# SCH.net
KiCad netlist of a schematic drawn in EasyEDA
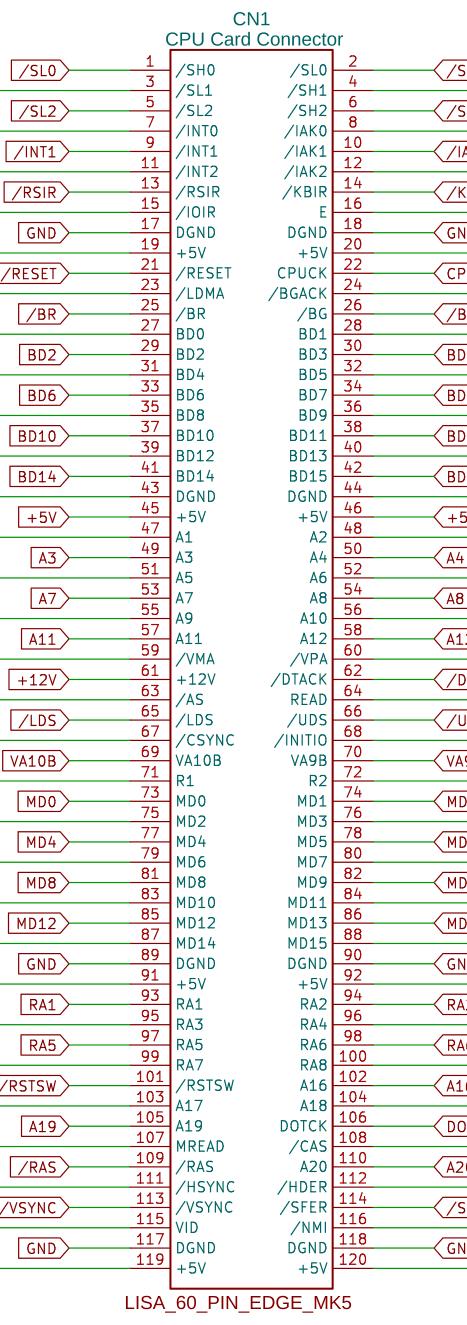
[diagram p0: CONNECTOR]
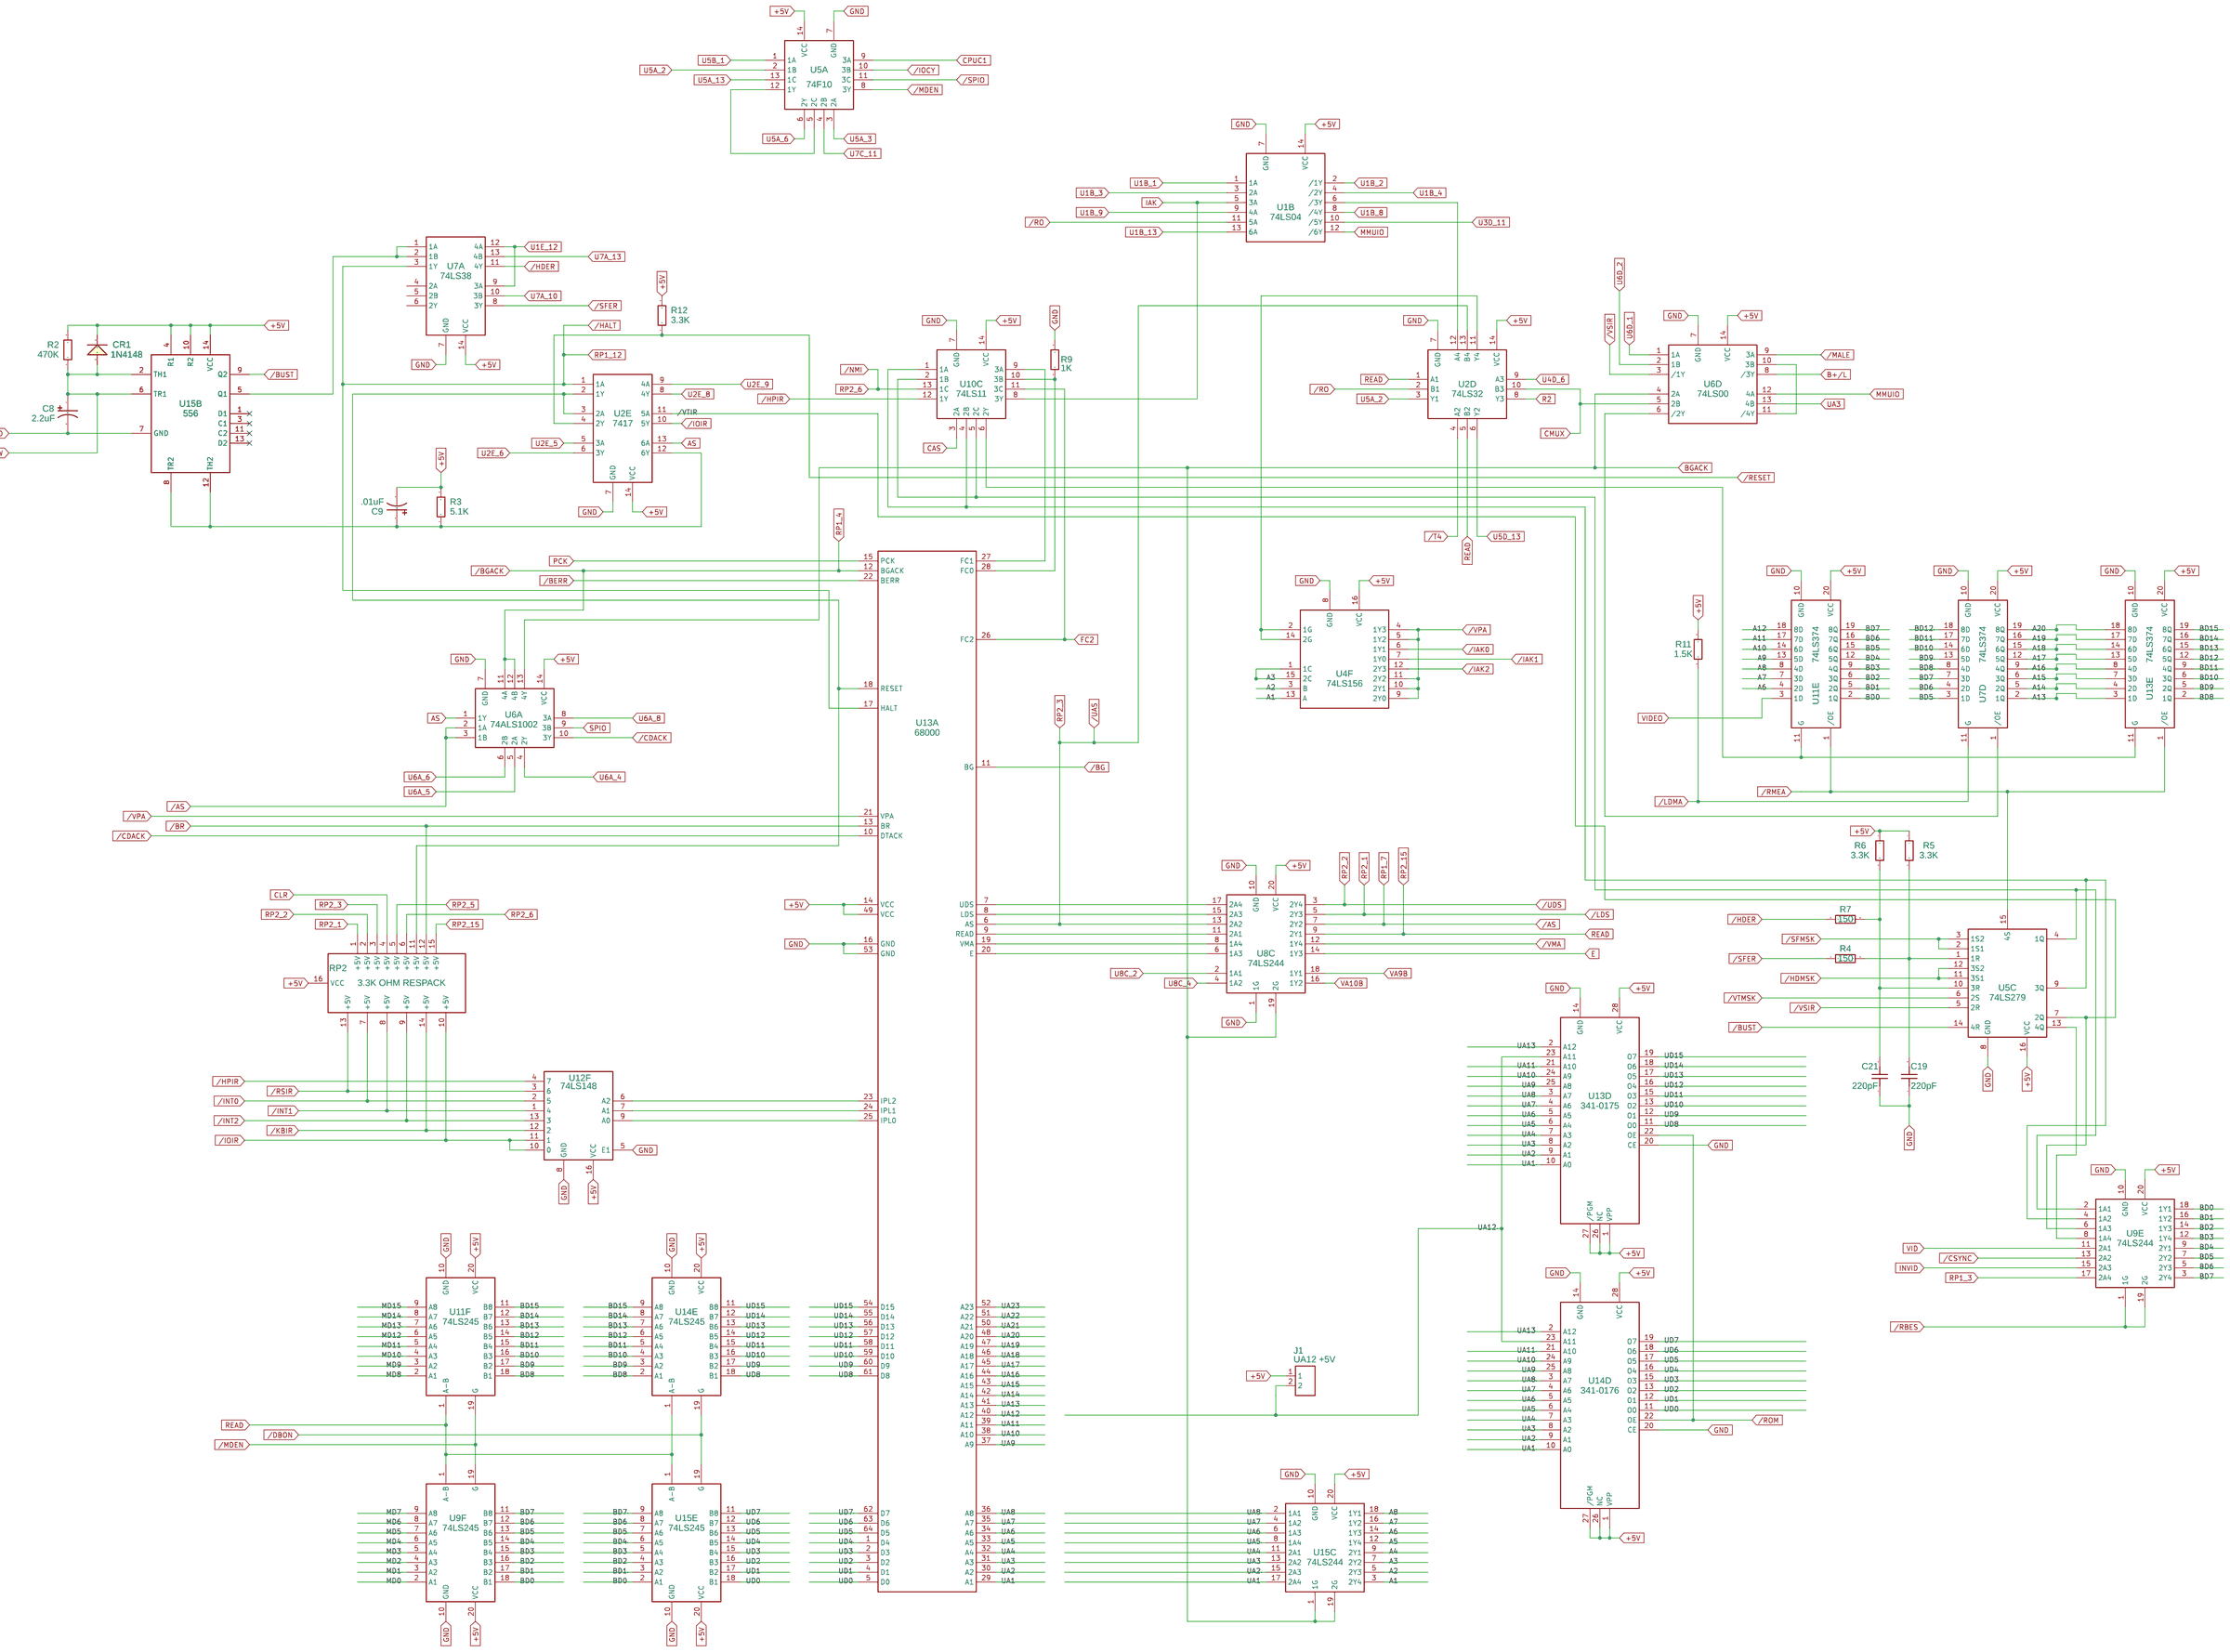
[diagram p1: CPU]
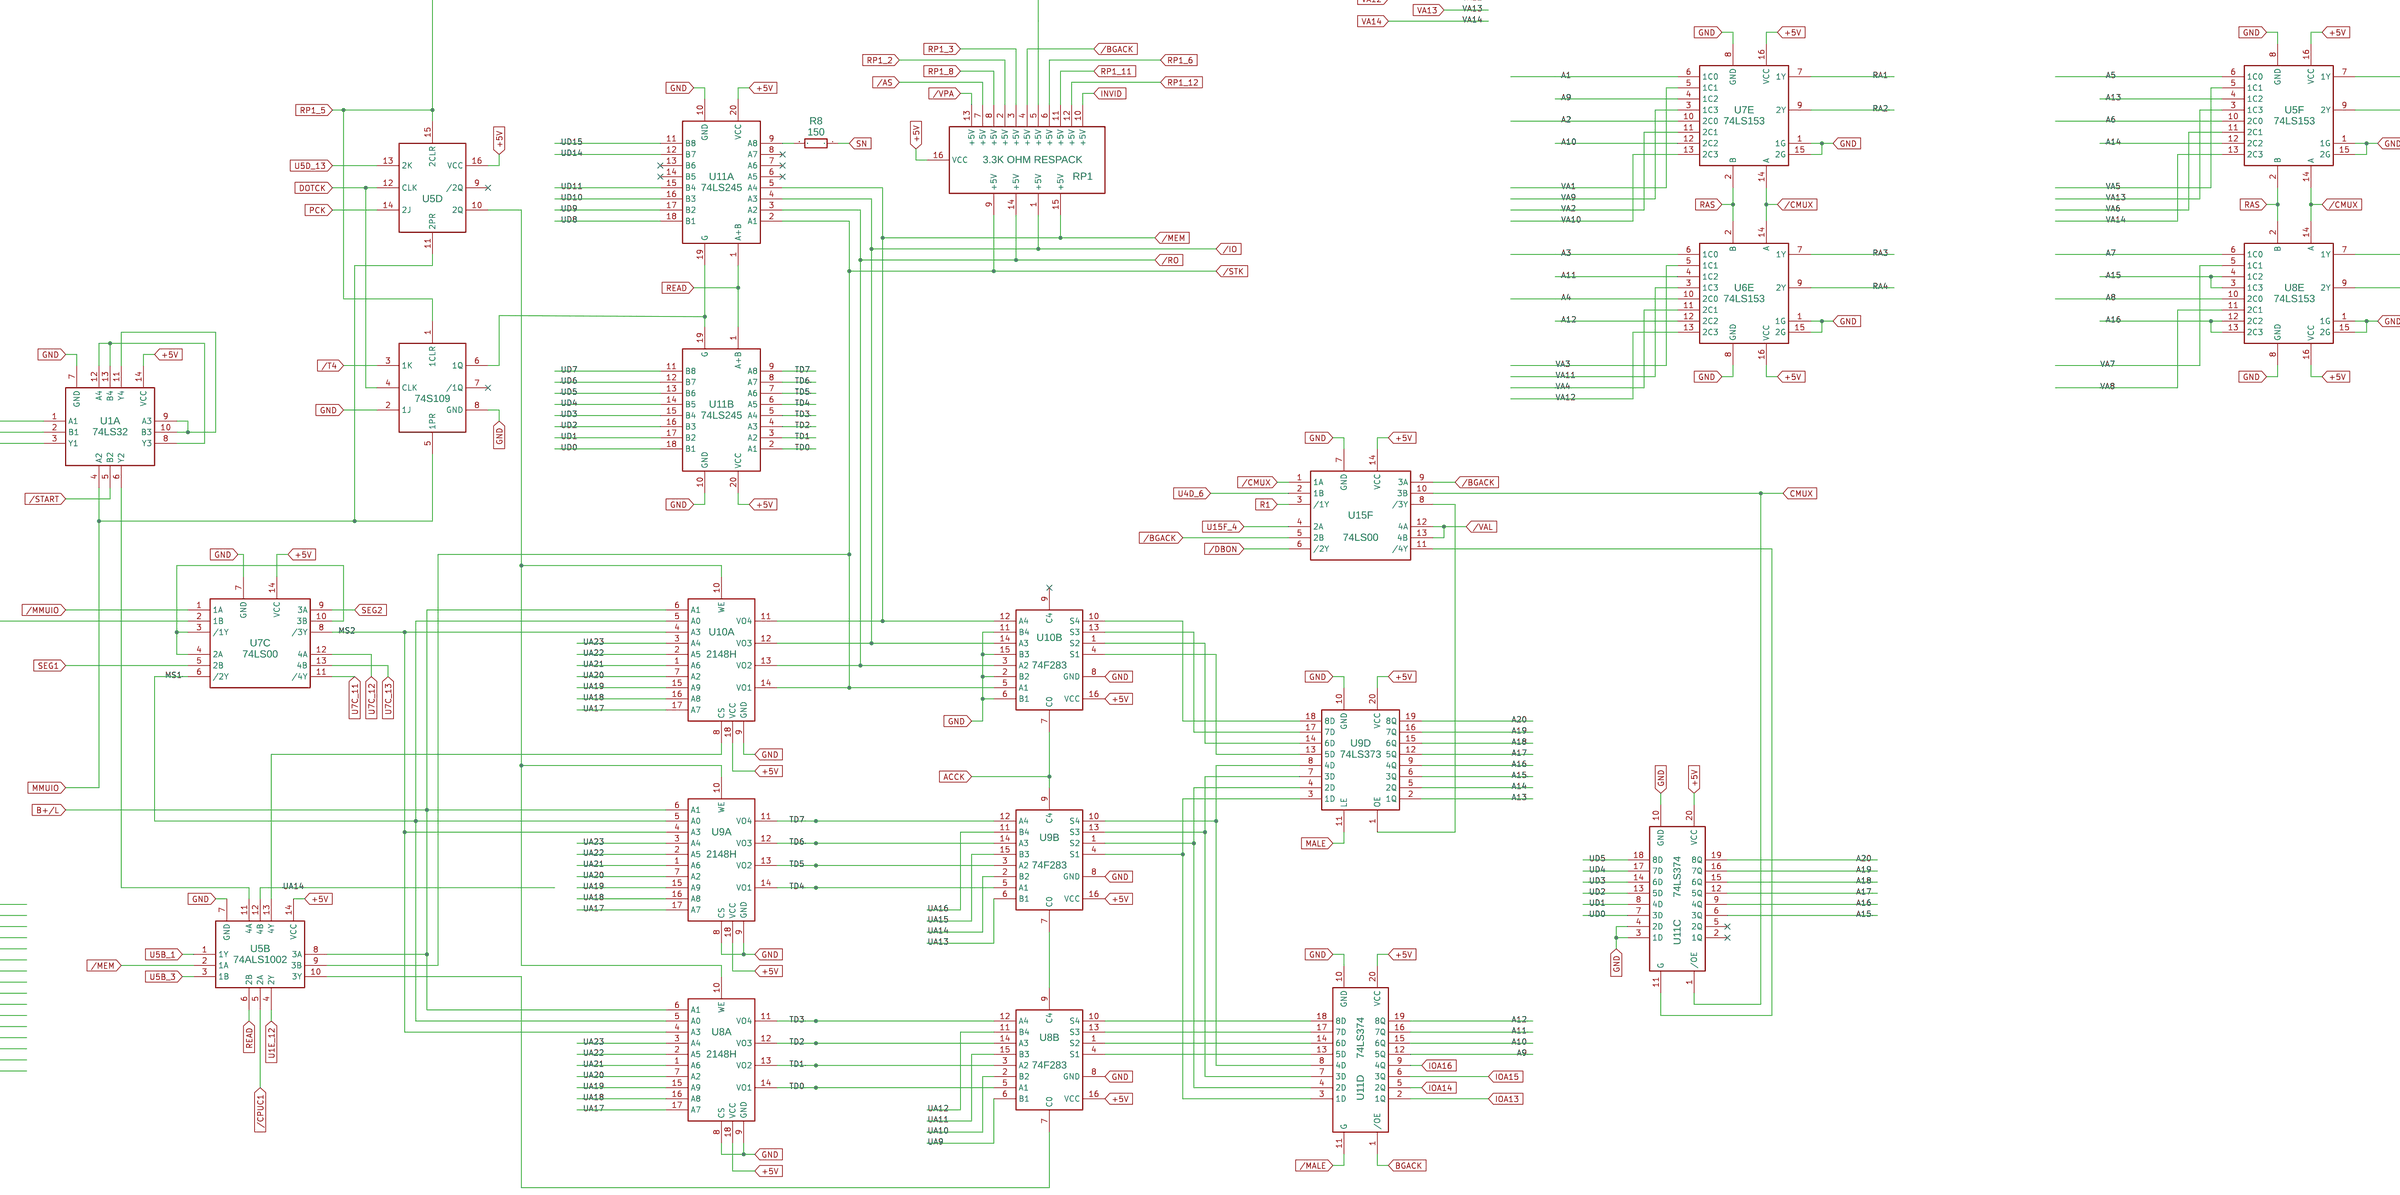
[diagram p2: MMU]
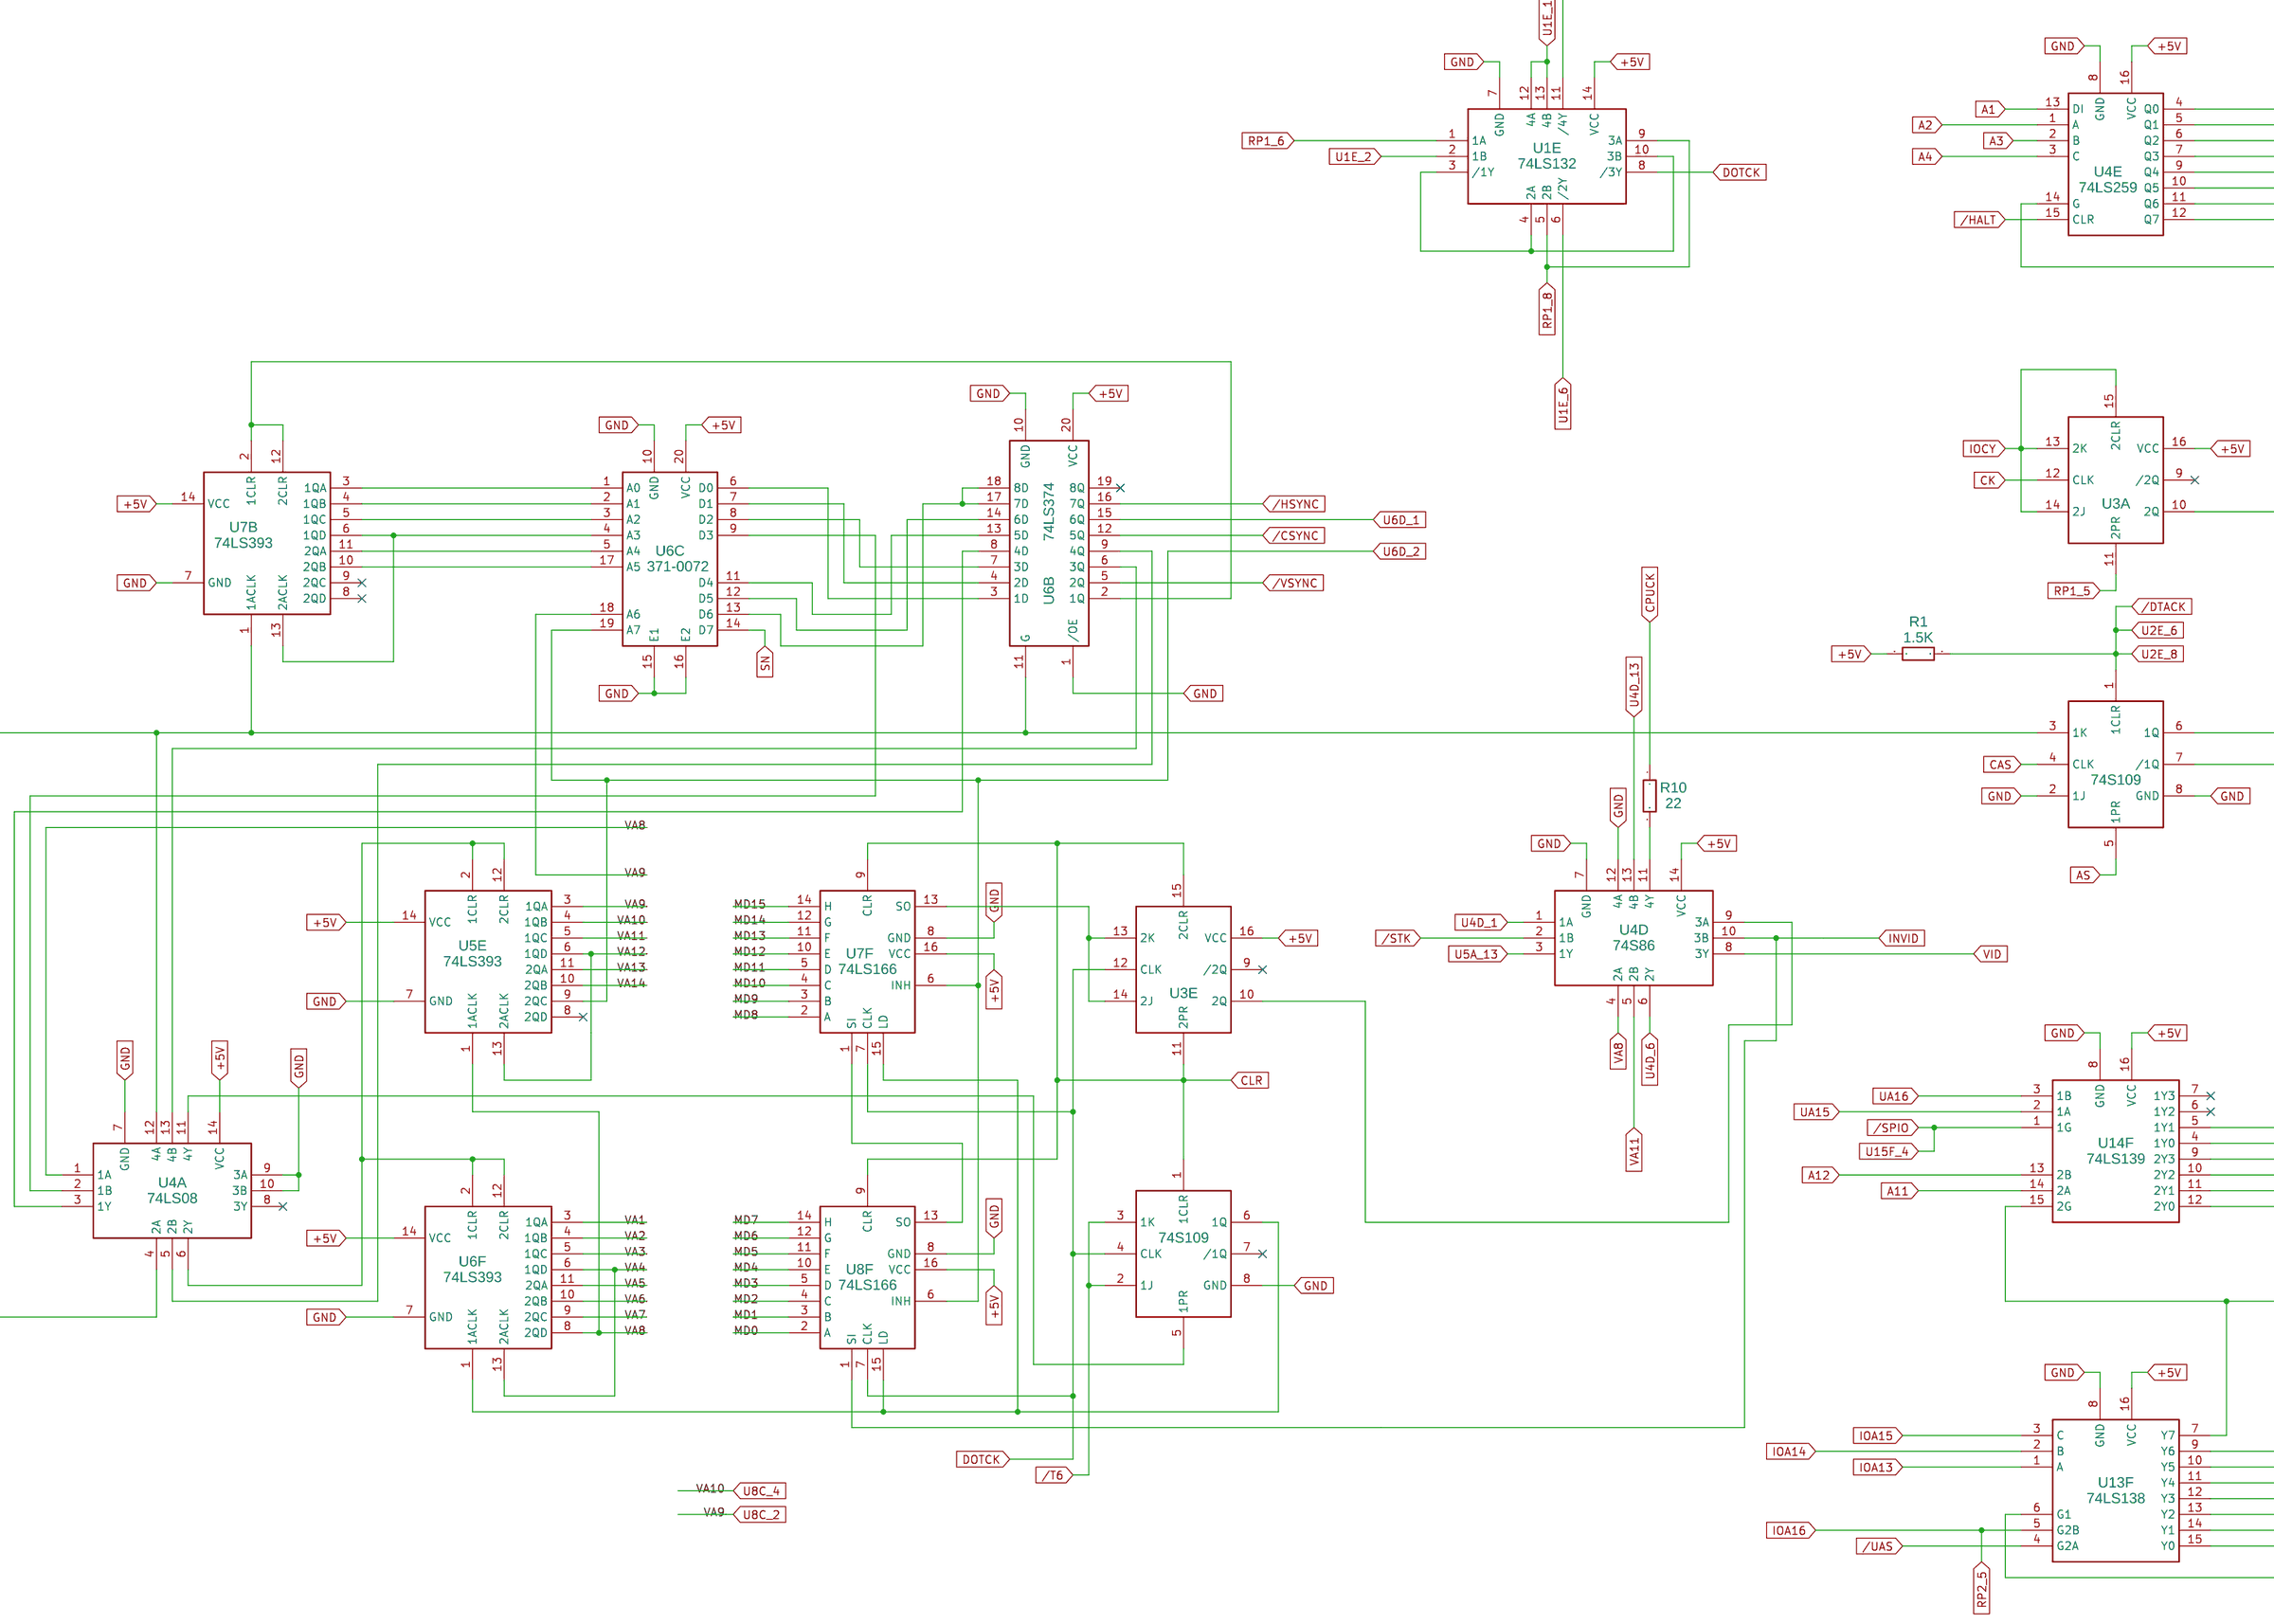
[diagram p3: VIDEO]
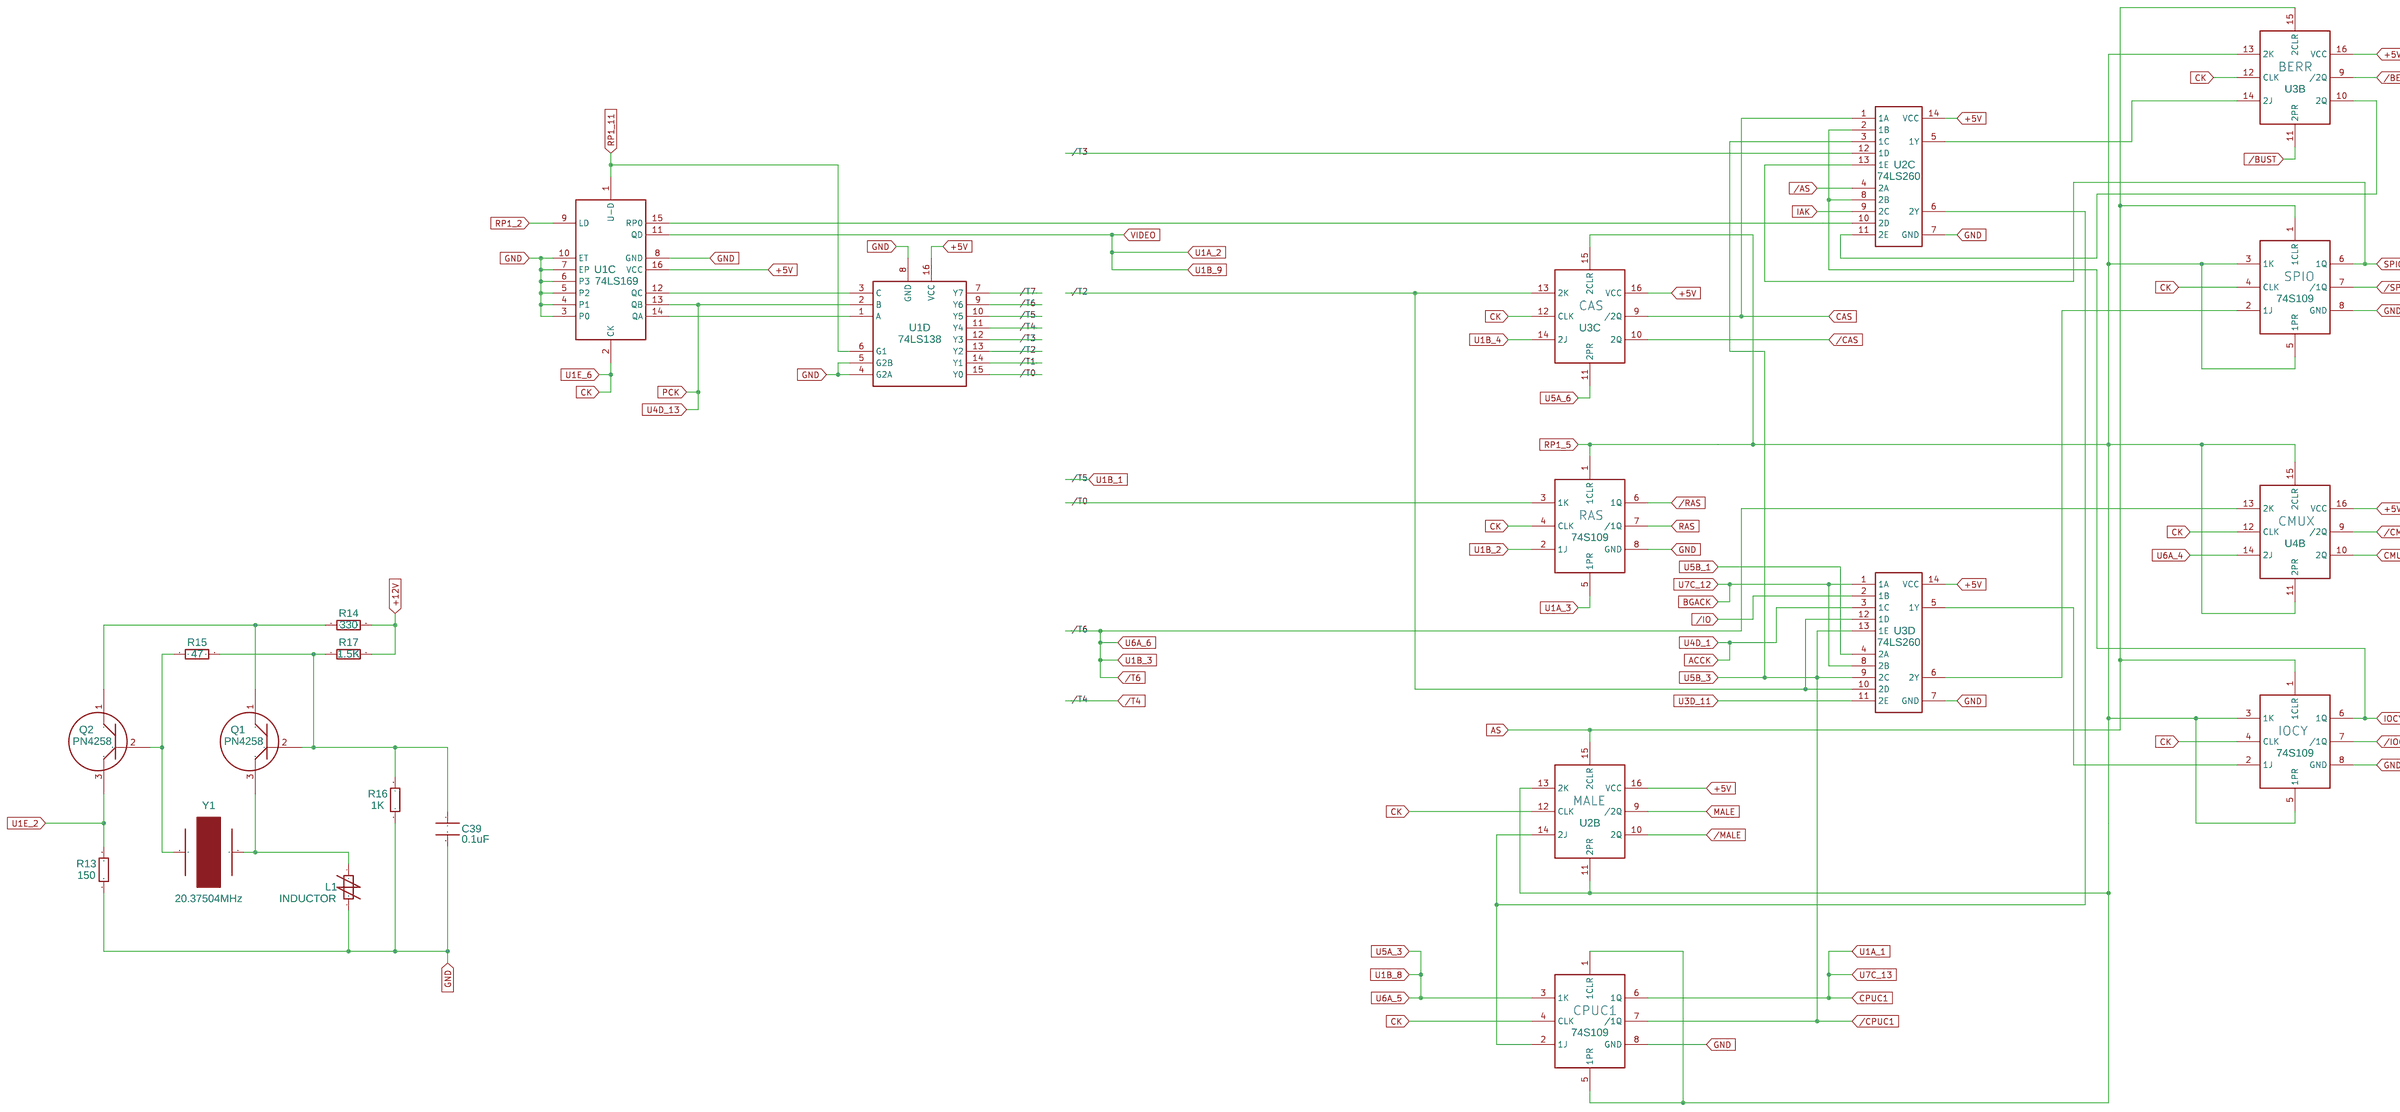
[diagram p4: CLOCK+IO]
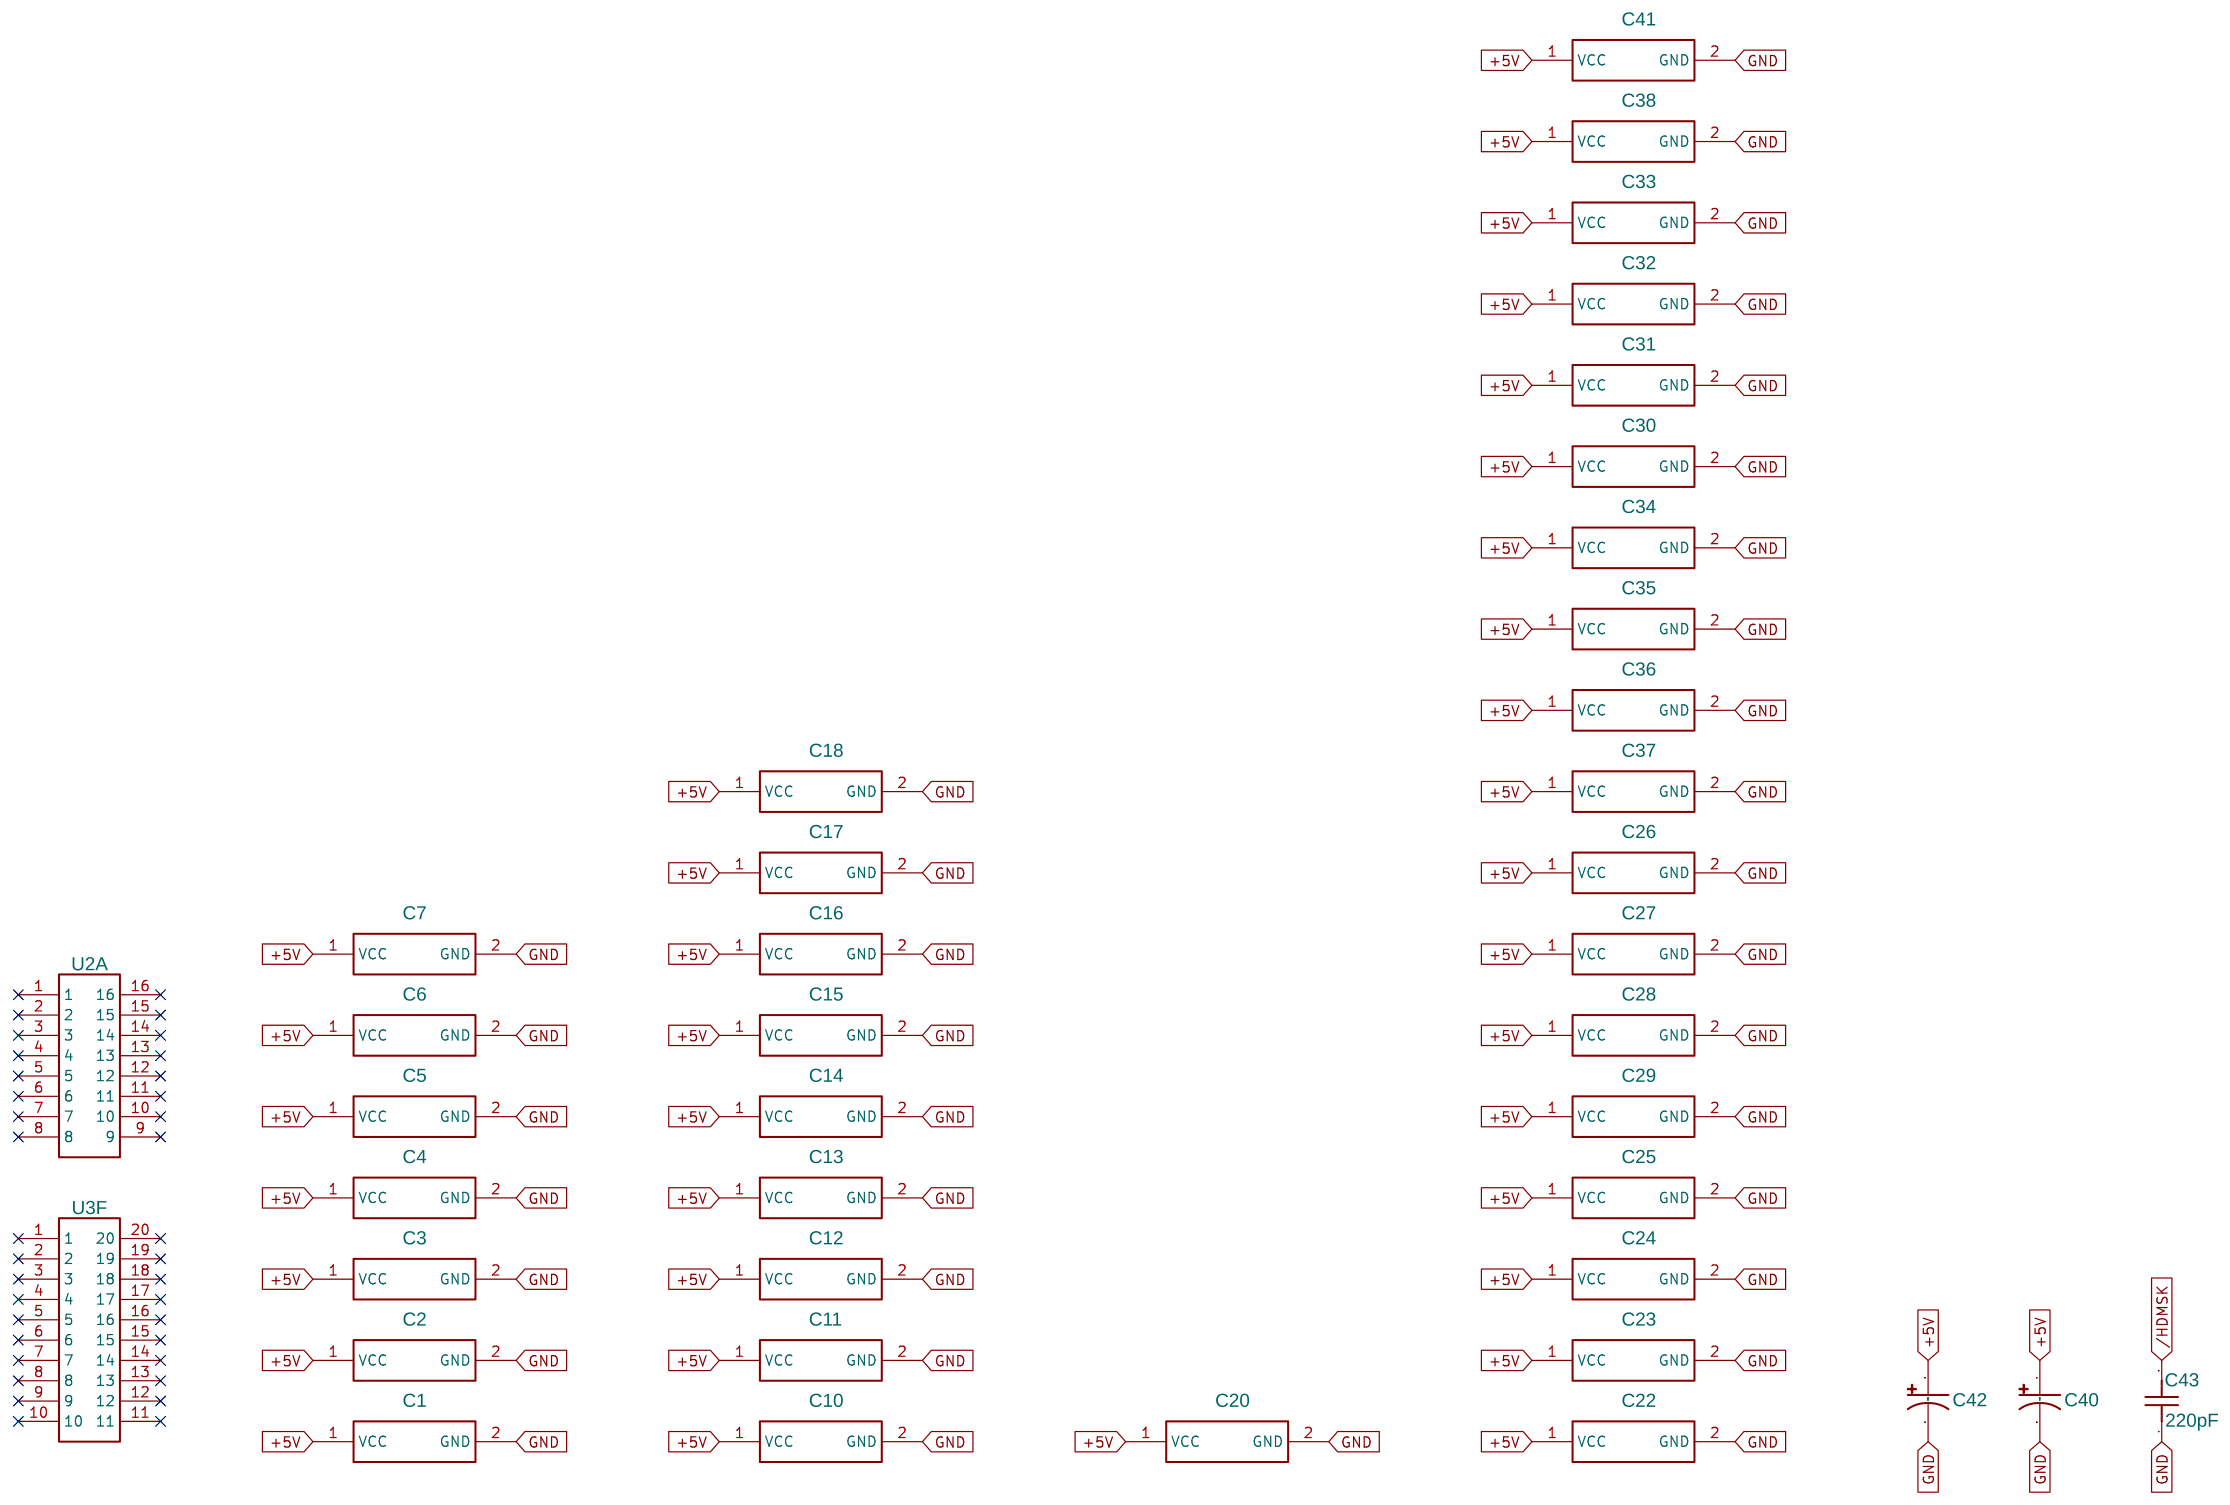
[diagram p5: MISC]

(export (version "E")
  (design (tool "Eeschema 10.0.6"))
  (components
    (comp (ref "CN1") (value "CPU Card Connector") (libsource (lib "") (part "Lisa CPU Connector")))
    (comp (ref "C8") (value "2.2uF") (libsource (lib "") (part "LISA_CPU_AXIAL_CAP")))
    (comp (ref "C9") (value ".01uF") (libsource (lib "") (part "LISA_CPU_AXIAL_CAP_1")))
    (comp (ref "C19") (value "220pF") (libsource (lib "") (part "LISA_CPU_CERAMIC_CAP")))
    (comp (ref "C21") (value "220pF") (libsource (lib "") (part "LISA_CPU_CERAMIC_CAP")))
    (comp (ref "CR1") (value "1N4148") (libsource (lib "") (part "LISA_CPU_DIODE")))
    (comp (ref "J1")
      (value "UA12 +5V")
      (fields (field (name "BOM_Manufacturer Part") "Jumper2") (field (name "BOM_Supplier Part") "C2940092"))
      (libsource (lib "") (part "JUMPER2"))
    )
    (comp (ref "R2") (value "470K") (libsource (lib "") (part "LISA_CPU_RESISTOR")))
    (comp (ref "R3") (value "5.1K") (libsource (lib "") (part "LISA_CPU_RESISTOR")))
    (comp (ref "R4") (value "150") (libsource (lib "") (part "LISA_CPU_RESISTOR_2")))
    (comp (ref "R5") (value "3.3K") (libsource (lib "") (part "LISA_CPU_RESISTOR_1")))
    (comp (ref "R6") (value "3.3K") (libsource (lib "") (part "LISA_CPU_RESISTOR_1")))
    (comp (ref "R7") (value "150") (libsource (lib "") (part "LISA_CPU_RESISTOR_2")))
    (comp (ref "R9") (value "1K") (libsource (lib "") (part "LISA_CPU_RESISTOR_1")))
    (comp (ref "R11") (value "1.5K") (libsource (lib "") (part "LISA_CPU_RESISTOR_1")))
    (comp (ref "R12") (value "3.3K") (libsource (lib "") (part "LISA_CPU_RESISTOR")))
    (comp (ref "RP2") (value "3.3K OHM RESPACK") (libsource (lib "") (part "LISA_CPU_RP2")))
    (comp (ref "U1B") (value "74LS04") (libsource (lib "") (part "LISA_CPU_74LS04")))
    (comp (ref "U2D") (value "74LS32") (libsource (lib "") (part "LISA_CPU_74LS32")))
    (comp (ref "U2E") (value "7417") (libsource (lib "") (part "LISA_CPU_7417")))
    (comp (ref "U4F") (value "74LS156") (libsource (lib "") (part "LISA_CPU_74LS156")))
    (comp (ref "U5A") (value "74F10") (libsource (lib "") (part "LISA_CPU_74F10")))
    (comp (ref "U5C") (value "74LS279") (libsource (lib "") (part "LISA_CPU_74LS279")))
    (comp (ref "U6A") (value "74ALS1002") (libsource (lib "") (part "LISA_CPU_74ALS1002")))
    (comp (ref "U6D") (value "74LS00") (libsource (lib "") (part "LISA_CPU_74LS00")))
    (comp (ref "U7A") (value "74LS38") (libsource (lib "") (part "LISA_CPU_74LS38")))
    (comp (ref "U7D") (value "74LS374") (libsource (lib "") (part "LISA_CPU_74LS374_1")))
    (comp (ref "U8C") (value "74LS244") (libsource (lib "") (part "LISA_CPU_74LS244_CTL")))
    (comp (ref "U9E") (value "74LS244") (libsource (lib "") (part "LISA_CPU_74LS244_1")))
    (comp (ref "U9F") (value "74LS245") (libsource (lib "") (part "LISA_CPU_74LS245_LOWER_1")))
    (comp (ref "U10C") (value "74LS11") (libsource (lib "") (part "LISA_CPU_74LS11")))
    (comp (ref "U11E") (value "74LS374") (libsource (lib "") (part "LISA_CPU_74LS374")))
    (comp (ref "U11F") (value "74LS245") (libsource (lib "") (part "LISA_CPU_74LS245_UPPER")))
    (comp (ref "U12F") (value "74LS148") (libsource (lib "") (part "LISA_CPU_74LS148")))
    (comp (ref "U13A") (value "68000") (libsource (lib "") (part "68000 (LISA)")))
    (comp (ref "U13D") (value "341-0175") (libsource (lib "") (part "LISA_CPU_EPROM")))
    (comp (ref "U13E") (value "74LS374") (libsource (lib "") (part "LISA_CPU_74LS374_2")))
    (comp (ref "U14D") (value "341-0176") (libsource (lib "") (part "LISA_CPU_EPROM_1")))
    (comp (ref "U14E") (value "74LS245") (libsource (lib "") (part "LISA_CPU_74LS245_UPPER_1")))
    (comp (ref "U15B") (value "556") (libsource (lib "") (part "LISA_CPU_556")))
    (comp (ref "U15C") (value "74LS244") (libsource (lib "") (part "LISA_CPU_74LS244")))
    (comp (ref "U15E") (value "74LS245") (libsource (lib "") (part "LISA_CPU_74LS245_LOWER")))
    (comp (ref "R8") (value "150") (libsource (lib "") (part "LISA_CPU_RESISTOR")))
    (comp (ref "RP1") (value "3.3K OHM RESPACK") (libsource (lib "") (part "LISA_CPU_RP1")))
    (comp (ref "U1A") (value "74LS32") (libsource (lib "") (part "LISA_CPU_74LS32")))
    (comp (ref "U5B") (value "74ALS1002") (libsource (lib "") (part "LISA_CPU_74ALS1002")))
    (comp (ref "U5D") (value "74S109") (libsource (lib "") (part "LISA_CPU_74S109")))
    (comp (ref "U5F") (value "74LS153") (libsource (lib "") (part "LISA_CPU_74LS153_UPPER_1")))
    (comp (ref "U6E") (value "74LS153") (libsource (lib "") (part "LISA_CPU_74LS153_LOWER_1")))
    (comp (ref "U7C") (value "74LS00") (libsource (lib "") (part "LISA_CPU_74LS00")))
    (comp (ref "U7E") (value "74LS153") (libsource (lib "") (part "LISA_CPU_74LS153_UPPER")))
    (comp (ref "U8A") (value "2148H") (libsource (lib "") (part "LISA_CPU_2148H")))
    (comp (ref "U8B") (value "74F283") (libsource (lib "") (part "LISA_CPU_74F283_1")))
    (comp (ref "U8E") (value "74LS153") (libsource (lib "") (part "LISA_CPU_74LS153_LOWER")))
    (comp (ref "U9A") (value "2148H") (libsource (lib "") (part "LISA_CPU_2148H_2")))
    (comp (ref "U9B") (value "74F283") (libsource (lib "") (part "LISA_CPU_74F283")))
    (comp (ref "U9D") (value "74LS373") (libsource (lib "") (part "LISA_CPU_74LS373")))
    (comp (ref "U10A") (value "2148H") (libsource (lib "") (part "LISA_CPU_2148H_1")))
    (comp (ref "U10B") (value "74F283") (libsource (lib "") (part "LISA_CPU_74F283_2")))
    (comp (ref "U11A") (value "74LS245") (libsource (lib "") (part "LISA_CPU_74LS245_U11A")))
    (comp (ref "U11B") (value "74LS245") (libsource (lib "") (part "LISA_CPU_74LS245_U11B")))
    (comp (ref "U11C") (value "74LS374") (libsource (lib "") (part "LISA_CPU_74LS374_1")))
    (comp (ref "U11D") (value "74LS374") (libsource (lib "") (part "LISA_CPU_74LS374")))
    (comp (ref "U15F") (value "74LS00") (libsource (lib "") (part "LISA_CPU_74LS00_1")))
    (comp (ref "R1") (value "1.5K") (libsource (lib "") (part "LISA_CPU_RESISTOR_1")))
    (comp (ref "R10") (value "22") (libsource (lib "") (part "LISA_CPU_RESISTOR")))
    (comp (ref "U1E") (value "74LS132") (libsource (lib "") (part "LISA_CPU_74LS132")))
    (comp (ref "U3A") (value "74S109") (libsource (lib "") (part "LISA_CPU_74S109")))
    (comp (ref "U3E") (value "74S109") (libsource (lib "") (part "LISA_CPU_74S109_1")))
    (comp (ref "U4A") (value "74LS08") (libsource (lib "") (part "LISA_CPU_74LS08")))
    (comp (ref "U4D") (value "74S86") (libsource (lib "") (part "LISA_CPU_74S86")))
    (comp (ref "U4E") (value "74LS259") (libsource (lib "") (part "LISA_CPU_74LS259")))
    (comp (ref "U5E") (value "74LS393") (libsource (lib "") (part "LISA_CPU_74LS393_2")))
    (comp (ref "U6B") (value "74LS374") (libsource (lib "") (part "LISA_CPU_74LS374")))
    (comp (ref "U6C") (value "371-0072") (libsource (lib "") (part "LISA_CPU_371-0072_VIDEO_ROM")))
    (comp (ref "U6F") (value "74LS393") (libsource (lib "") (part "LISA_CPU_74LS393")))
    (comp (ref "U7B") (value "74LS393") (libsource (lib "") (part "LISA_CPU_74LS393_1")))
    (comp (ref "U7F") (value "74LS166") (libsource (lib "") (part "LISA_CPU_74LS166")))
    (comp (ref "U8F") (value "74LS166") (libsource (lib "") (part "LISA_CPU_74LS166_1")))
    (comp (ref "U13F") (value "74LS138") (libsource (lib "") (part "LISA_CPU_74LS138")))
    (comp (ref "U14F") (value "74LS139") (libsource (lib "") (part "LISA_CPU_74LS139")))
    (comp (ref "C39") (value "0.1uF") (libsource (lib "") (part "LISA_CPU_GLASS_CAP")))
    (comp (ref "L1") (value "INDUCTOR") (libsource (lib "") (part "LISA_CPU_INDUCTOR")))
    (comp (ref "Q1") (value "PN4258") (libsource (lib "") (part "LISA_CPU_TRANSISTOR")))
    (comp (ref "Q2") (value "PN4258") (libsource (lib "") (part "LISA_CPU_TRANSISTOR")))
    (comp (ref "R13") (value "150") (libsource (lib "") (part "LISA_CPU_RESISTOR")))
    (comp (ref "R14") (value "330") (libsource (lib "") (part "LISA_CPU_RESISTOR_1")))
    (comp (ref "R15") (value "47") (libsource (lib "") (part "LISA_CPU_RESISTOR_1")))
    (comp (ref "R16") (value "1K") (libsource (lib "") (part "LISA_CPU_RESISTOR")))
    (comp (ref "R17") (value "1.5K") (libsource (lib "") (part "LISA_CPU_RESISTOR_1")))
    (comp (ref "U1C") (value "74LS169") (libsource (lib "") (part "LISA_CPU_74LS169")))
    (comp (ref "U1D") (value "74LS138") (libsource (lib "") (part "LISA_CPU_74LS138")))
    (comp (ref "U2B") (value "74S109") (libsource (lib "") (part "LISA_CPU_74S109")))
    (comp (ref "U2C") (value "74LS260") (libsource (lib "") (part "LISA_CPU_74LS260")))
    (comp (ref "U3B") (value "74S109") (libsource (lib "") (part "LISA_CPU_74S109_1")))
    (comp (ref "U3C") (value "74S109") (libsource (lib "") (part "LISA_CPU_74S109_2")))
    (comp (ref "U3D") (value "74LS260") (libsource (lib "") (part "LISA_CPU_74LS260_1")))
    (comp (ref "U4B") (value "74S109") (libsource (lib "") (part "LISA_CPU_74S109_3")))
    (comp (ref "Y1") (value "20.37504MHz") (libsource (lib "") (part "LISA_CPU_XTAL")))
    (comp (ref "C1")
      (value "LISA_CPU_DECOUPLER_CERAMIC_CAP")
      (libsource (lib "") (part "LISA_CPU_DECOUPLER_CERAMIC_CAP"))
    )
    (comp (ref "C2")
      (value "LISA_CPU_DECOUPLER_CERAMIC_CAP")
      (libsource (lib "") (part "LISA_CPU_DECOUPLER_CERAMIC_CAP"))
    )
    (comp (ref "C3")
      (value "LISA_CPU_DECOUPLER_CERAMIC_CAP")
      (libsource (lib "") (part "LISA_CPU_DECOUPLER_CERAMIC_CAP"))
    )
    (comp (ref "C4")
      (value "LISA_CPU_DECOUPLER_CERAMIC_CAP")
      (libsource (lib "") (part "LISA_CPU_DECOUPLER_CERAMIC_CAP"))
    )
    (comp (ref "C5")
      (value "LISA_CPU_DECOUPLER_CERAMIC_CAP")
      (libsource (lib "") (part "LISA_CPU_DECOUPLER_CERAMIC_CAP"))
    )
    (comp (ref "C6")
      (value "LISA_CPU_DECOUPLER_CERAMIC_CAP")
      (libsource (lib "") (part "LISA_CPU_DECOUPLER_CERAMIC_CAP"))
    )
    (comp (ref "C7")
      (value "LISA_CPU_DECOUPLER_CERAMIC_CAP")
      (libsource (lib "") (part "LISA_CPU_DECOUPLER_CERAMIC_CAP"))
    )
    (comp (ref "C10")
      (value "LISA_CPU_DECOUPLER_CERAMIC_CAP")
      (libsource (lib "") (part "LISA_CPU_DECOUPLER_CERAMIC_CAP"))
    )
    (comp (ref "C11")
      (value "LISA_CPU_DECOUPLER_CERAMIC_CAP")
      (libsource (lib "") (part "LISA_CPU_DECOUPLER_CERAMIC_CAP"))
    )
    (comp (ref "C12")
      (value "LISA_CPU_DECOUPLER_CERAMIC_CAP")
      (libsource (lib "") (part "LISA_CPU_DECOUPLER_CERAMIC_CAP"))
    )
    (comp (ref "C13")
      (value "LISA_CPU_DECOUPLER_CERAMIC_CAP")
      (libsource (lib "") (part "LISA_CPU_DECOUPLER_CERAMIC_CAP"))
    )
    (comp (ref "C14")
      (value "LISA_CPU_DECOUPLER_CERAMIC_CAP")
      (libsource (lib "") (part "LISA_CPU_DECOUPLER_CERAMIC_CAP"))
    )
    (comp (ref "C15")
      (value "LISA_CPU_DECOUPLER_CERAMIC_CAP")
      (libsource (lib "") (part "LISA_CPU_DECOUPLER_CERAMIC_CAP"))
    )
    (comp (ref "C16")
      (value "LISA_CPU_DECOUPLER_CERAMIC_CAP")
      (libsource (lib "") (part "LISA_CPU_DECOUPLER_CERAMIC_CAP"))
    )
    (comp (ref "C17")
      (value "LISA_CPU_DECOUPLER_CERAMIC_CAP")
      (libsource (lib "") (part "LISA_CPU_DECOUPLER_CERAMIC_CAP"))
    )
    (comp (ref "C18")
      (value "LISA_CPU_DECOUPLER_CERAMIC_CAP")
      (libsource (lib "") (part "LISA_CPU_DECOUPLER_CERAMIC_CAP"))
    )
    (comp (ref "C20")
      (value "LISA_CPU_DECOUPLER_CERAMIC_CAP")
      (libsource (lib "") (part "LISA_CPU_DECOUPLER_CERAMIC_CAP"))
    )
    (comp (ref "C22")
      (value "LISA_CPU_DECOUPLER_CERAMIC_CAP")
      (libsource (lib "") (part "LISA_CPU_DECOUPLER_CERAMIC_CAP"))
    )
    (comp (ref "C23")
      (value "LISA_CPU_DECOUPLER_CERAMIC_CAP")
      (libsource (lib "") (part "LISA_CPU_DECOUPLER_CERAMIC_CAP"))
    )
    (comp (ref "C24")
      (value "LISA_CPU_DECOUPLER_CERAMIC_CAP")
      (libsource (lib "") (part "LISA_CPU_DECOUPLER_CERAMIC_CAP"))
    )
    (comp (ref "C25")
      (value "LISA_CPU_DECOUPLER_CERAMIC_CAP")
      (libsource (lib "") (part "LISA_CPU_DECOUPLER_CERAMIC_CAP"))
    )
    (comp (ref "C26")
      (value "LISA_CPU_DECOUPLER_CERAMIC_CAP")
      (libsource (lib "") (part "LISA_CPU_DECOUPLER_CERAMIC_CAP"))
    )
    (comp (ref "C27")
      (value "LISA_CPU_DECOUPLER_CERAMIC_CAP")
      (libsource (lib "") (part "LISA_CPU_DECOUPLER_CERAMIC_CAP"))
    )
    (comp (ref "C28")
      (value "LISA_CPU_DECOUPLER_CERAMIC_CAP")
      (libsource (lib "") (part "LISA_CPU_DECOUPLER_CERAMIC_CAP"))
    )
    (comp (ref "C29")
      (value "LISA_CPU_DECOUPLER_CERAMIC_CAP")
      (libsource (lib "") (part "LISA_CPU_DECOUPLER_CERAMIC_CAP"))
    )
    (comp (ref "C30")
      (value "LISA_CPU_DECOUPLER_CERAMIC_CAP")
      (libsource (lib "") (part "LISA_CPU_DECOUPLER_CERAMIC_CAP"))
    )
    (comp (ref "C31")
      (value "LISA_CPU_DECOUPLER_CERAMIC_CAP")
      (libsource (lib "") (part "LISA_CPU_DECOUPLER_CERAMIC_CAP"))
    )
    (comp (ref "C32")
      (value "LISA_CPU_DECOUPLER_CERAMIC_CAP")
      (libsource (lib "") (part "LISA_CPU_DECOUPLER_CERAMIC_CAP"))
    )
    (comp (ref "C33")
      (value "LISA_CPU_DECOUPLER_CERAMIC_CAP")
      (libsource (lib "") (part "LISA_CPU_DECOUPLER_CERAMIC_CAP"))
    )
    (comp (ref "C34")
      (value "LISA_CPU_DECOUPLER_CERAMIC_CAP")
      (libsource (lib "") (part "LISA_CPU_DECOUPLER_CERAMIC_CAP"))
    )
    (comp (ref "C35")
      (value "LISA_CPU_DECOUPLER_CERAMIC_CAP")
      (libsource (lib "") (part "LISA_CPU_DECOUPLER_CERAMIC_CAP"))
    )
    (comp (ref "C36")
      (value "LISA_CPU_DECOUPLER_CERAMIC_CAP")
      (libsource (lib "") (part "LISA_CPU_DECOUPLER_CERAMIC_CAP"))
    )
    (comp (ref "C37")
      (value "LISA_CPU_DECOUPLER_CERAMIC_CAP")
      (libsource (lib "") (part "LISA_CPU_DECOUPLER_CERAMIC_CAP"))
    )
    (comp (ref "C38")
      (value "LISA_CPU_DECOUPLER_CERAMIC_CAP")
      (libsource (lib "") (part "LISA_CPU_DECOUPLER_CERAMIC_CAP"))
    )
    (comp (ref "C40") (value "LISA_CPU_AXIAL_CAP") (libsource (lib "") (part "LISA_CPU_AXIAL_CAP")))
    (comp (ref "C41")
      (value "LISA_CPU_DECOUPLER_CERAMIC_CAP")
      (libsource (lib "") (part "LISA_CPU_DECOUPLER_CERAMIC_CAP"))
    )
    (comp (ref "C42") (value "LISA_CPU_AXIAL_CAP") (libsource (lib "") (part "LISA_CPU_AXIAL_CAP")))
    (comp (ref "C43") (value "220pF") (libsource (lib "") (part "LISA_CPU_CERAMIC_CAP")))
    (comp (ref "U2A") (value "LISA_EMPTY_DIP_16") (libsource (lib "") (part "LISA_EMPTY_DIP_16")))
    (comp (ref "U3F") (value "LISA_EMPTY_DIP_20") (libsource (lib "") (part "LISA_EMPTY_DIP_20")))
  )
  (nets
    (net (code "1") (name "+5V") (class "Default")
      (node (ref "C1") (pin "1") (pinfunction "VCC_1") (pintype "unspecified"))
      (node (ref "C10") (pin "1") (pinfunction "VCC_1") (pintype "unspecified"))
      (node (ref "C11") (pin "1") (pinfunction "VCC_1") (pintype "unspecified"))
      (node (ref "C12") (pin "1") (pinfunction "VCC_1") (pintype "unspecified"))
      (node (ref "C13") (pin "1") (pinfunction "VCC_1") (pintype "unspecified"))
      (node (ref "C14") (pin "1") (pinfunction "VCC_1") (pintype "unspecified"))
      (node (ref "C15") (pin "1") (pinfunction "VCC_1") (pintype "unspecified"))
      (node (ref "C16") (pin "1") (pinfunction "VCC_1") (pintype "unspecified"))
      (node (ref "C17") (pin "1") (pinfunction "VCC_1") (pintype "unspecified"))
      (node (ref "C18") (pin "1") (pinfunction "VCC_1") (pintype "unspecified"))
      (node (ref "C2") (pin "1") (pinfunction "VCC_1") (pintype "unspecified"))
      (node (ref "C20") (pin "1") (pinfunction "VCC_1") (pintype "unspecified"))
      (node (ref "C22") (pin "1") (pinfunction "VCC_1") (pintype "unspecified"))
      (node (ref "C23") (pin "1") (pinfunction "VCC_1") (pintype "unspecified"))
      (node (ref "C24") (pin "1") (pinfunction "VCC_1") (pintype "unspecified"))
      (node (ref "C25") (pin "1") (pinfunction "VCC_1") (pintype "unspecified"))
      (node (ref "C26") (pin "1") (pinfunction "VCC_1") (pintype "unspecified"))
      (node (ref "C27") (pin "1") (pinfunction "VCC_1") (pintype "unspecified"))
      (node (ref "C28") (pin "1") (pinfunction "VCC_1") (pintype "unspecified"))
      (node (ref "C29") (pin "1") (pinfunction "VCC_1") (pintype "unspecified"))
      (node (ref "C3") (pin "1") (pinfunction "VCC_1") (pintype "unspecified"))
      (node (ref "C30") (pin "1") (pinfunction "VCC_1") (pintype "unspecified"))
      (node (ref "C31") (pin "1") (pinfunction "VCC_1") (pintype "unspecified"))
      (node (ref "C32") (pin "1") (pinfunction "VCC_1") (pintype "unspecified"))
      (node (ref "C33") (pin "1") (pinfunction "VCC_1") (pintype "unspecified"))
      (node (ref "C34") (pin "1") (pinfunction "VCC_1") (pintype "unspecified"))
      (node (ref "C35") (pin "1") (pinfunction "VCC_1") (pintype "unspecified"))
      (node (ref "C36") (pin "1") (pinfunction "VCC_1") (pintype "unspecified"))
      (node (ref "C37") (pin "1") (pinfunction "VCC_1") (pintype "unspecified"))
      (node (ref "C38") (pin "1") (pinfunction "VCC_1") (pintype "unspecified"))
      (node (ref "C4") (pin "1") (pinfunction "VCC_1") (pintype "unspecified"))
      (node (ref "C40") (pin "1") (pinfunction "1_1") (pintype "unspecified"))
      (node (ref "C41") (pin "1") (pinfunction "VCC_1") (pintype "unspecified"))
      (node (ref "C42") (pin "1") (pinfunction "1_1") (pintype "unspecified"))
      (node (ref "C5") (pin "1") (pinfunction "VCC_1") (pintype "unspecified"))
      (node (ref "C6") (pin "1") (pinfunction "VCC_1") (pintype "unspecified"))
      (node (ref "C7") (pin "1") (pinfunction "VCC_1") (pintype "unspecified"))
      (node (ref "C9") (pin "2") (pinfunction "2_2") (pintype "unspecified"))
      (node (ref "CN1") (pin "119") (pinfunction "+5V_119") (pintype "unspecified"))
      (node (ref "CN1") (pin "120") (pinfunction "+5V_120") (pintype "unspecified"))
      (node (ref "CN1") (pin "19") (pinfunction "+5V_19") (pintype "unspecified"))
      (node (ref "CN1") (pin "20") (pinfunction "+5V_20") (pintype "unspecified"))
      (node (ref "CN1") (pin "45") (pinfunction "+5V_45") (pintype "unspecified"))
      (node (ref "CN1") (pin "46") (pinfunction "+5V_46") (pintype "unspecified"))
      (node (ref "CN1") (pin "91") (pinfunction "+5V_91") (pintype "unspecified"))
      (node (ref "CN1") (pin "92") (pinfunction "+5V_92") (pintype "unspecified"))
      (node (ref "CR1") (pin "2") (pinfunction "2_2") (pintype "unspecified"))
      (node (ref "J1") (pin "1") (pinfunction "1_1") (pintype "unspecified"))
      (node (ref "R1") (pin "2") (pinfunction "2_2") (pintype "unspecified"))
      (node (ref "R11") (pin "1") (pinfunction "1_1") (pintype "unspecified"))
      (node (ref "R12") (pin "2") (pinfunction "2_2") (pintype "unspecified"))
      (node (ref "R2") (pin "2") (pinfunction "2_2") (pintype "unspecified"))
      (node (ref "R3") (pin "2") (pinfunction "2_2") (pintype "unspecified"))
      (node (ref "R5") (pin "1") (pinfunction "1_1") (pintype "unspecified"))
      (node (ref "R6") (pin "1") (pinfunction "1_1") (pintype "unspecified"))
      (node (ref "RP1") (pin "16") (pinfunction "VCC_16") (pintype "unspecified"))
      (node (ref "RP2") (pin "16") (pinfunction "VCC_16") (pintype "unspecified"))
      (node (ref "U10A") (pin "18") (pinfunction "VCC_18") (pintype "unspecified"))
      (node (ref "U10B") (pin "16") (pinfunction "VCC_16") (pintype "unspecified"))
      (node (ref "U10C") (pin "14") (pinfunction "VCC_14") (pintype "unspecified"))
      (node (ref "U11A") (pin "20") (pinfunction "VCC_20") (pintype "unspecified"))
      (node (ref "U11B") (pin "20") (pinfunction "VCC_20") (pintype "unspecified"))
      (node (ref "U11C") (pin "20") (pinfunction "VCC_20") (pintype "unspecified"))
      (node (ref "U11D") (pin "20") (pinfunction "VCC_20") (pintype "unspecified"))
      (node (ref "U11E") (pin "20") (pinfunction "VCC_20") (pintype "unspecified"))
      (node (ref "U11F") (pin "20") (pinfunction "VCC_20") (pintype "unspecified"))
      (node (ref "U12F") (pin "16") (pinfunction "VCC_16") (pintype "unspecified"))
      (node (ref "U13A") (pin "14") (pinfunction "VCC_14") (pintype "unspecified"))
      (node (ref "U13A") (pin "49") (pinfunction "VCC_49") (pintype "unspecified"))
      (node (ref "U13D") (pin "1") (pinfunction "VPP_1") (pintype "unspecified"))
      (node (ref "U13D") (pin "26") (pinfunction "NC_26") (pintype "unspecified"))
      (node (ref "U13D") (pin "27") (pinfunction "/PGM_27") (pintype "unspecified"))
      (node (ref "U13D") (pin "28") (pinfunction "VCC_28") (pintype "unspecified"))
      (node (ref "U13E") (pin "20") (pinfunction "VCC_20") (pintype "unspecified"))
      (node (ref "U13F") (pin "16") (pinfunction "VCC_16") (pintype "unspecified"))
      (node (ref "U14D") (pin "1") (pinfunction "VPP_1") (pintype "unspecified"))
      (node (ref "U14D") (pin "26") (pinfunction "NC_26") (pintype "unspecified"))
      (node (ref "U14D") (pin "27") (pinfunction "/PGM_27") (pintype "unspecified"))
      (node (ref "U14D") (pin "28") (pinfunction "VCC_28") (pintype "unspecified"))
      (node (ref "U14E") (pin "20") (pinfunction "VCC_20") (pintype "unspecified"))
      (node (ref "U14F") (pin "16") (pinfunction "VCC_16") (pintype "unspecified"))
      (node (ref "U15B") (pin "10") (pinfunction "R2_10") (pintype "unspecified"))
      (node (ref "U15B") (pin "14") (pinfunction "VCC_14") (pintype "unspecified"))
      (node (ref "U15B") (pin "4") (pinfunction "R1_4") (pintype "unspecified"))
      (node (ref "U15C") (pin "20") (pinfunction "VCC_20") (pintype "unspecified"))
      (node (ref "U15E") (pin "20") (pinfunction "VCC_20") (pintype "unspecified"))
      (node (ref "U15F") (pin "14") (pinfunction "VCC_14") (pintype "unspecified"))
      (node (ref "U1A") (pin "14") (pinfunction "VCC_14") (pintype "unspecified"))
      (node (ref "U1B") (pin "14") (pinfunction "VCC_14") (pintype "unspecified"))
      (node (ref "U1C") (pin "16") (pinfunction "VCC_16") (pintype "unspecified"))
      (node (ref "U1D") (pin "16") (pinfunction "VCC_16") (pintype "unspecified"))
      (node (ref "U1E") (pin "14") (pinfunction "VCC_14") (pintype "unspecified"))
      (node (ref "U2B") (pin "16") (pinfunction "VCC_16") (pintype "unspecified"))
      (node (ref "U2C") (pin "14") (pinfunction "VCC_14") (pintype "unspecified"))
      (node (ref "U2D") (pin "14") (pinfunction "VCC_14") (pintype "unspecified"))
      (node (ref "U2E") (pin "14") (pinfunction "VCC_14") (pintype "unspecified"))
      (node (ref "U3A") (pin "16") (pinfunction "VCC_16") (pintype "unspecified"))
      (node (ref "U3B") (pin "16") (pinfunction "VCC_16") (pintype "unspecified"))
      (node (ref "U3C") (pin "16") (pinfunction "VCC_16") (pintype "unspecified"))
      (node (ref "U3D") (pin "14") (pinfunction "VCC_14") (pintype "unspecified"))
      (node (ref "U3E") (pin "16") (pinfunction "VCC_16") (pintype "unspecified"))
      (node (ref "U4A") (pin "14") (pinfunction "VCC_14") (pintype "unspecified"))
      (node (ref "U4B") (pin "16") (pinfunction "VCC_16") (pintype "unspecified"))
      (node (ref "U4D") (pin "14") (pinfunction "VCC_14") (pintype "unspecified"))
      (node (ref "U4E") (pin "16") (pinfunction "VCC_16") (pintype "unspecified"))
      (node (ref "U4F") (pin "16") (pinfunction "VCC_16") (pintype "unspecified"))
      (node (ref "U5A") (pin "14") (pinfunction "VCC_14") (pintype "unspecified"))
      (node (ref "U5B") (pin "14") (pinfunction "VCC_14") (pintype "unspecified"))
      (node (ref "U5C") (pin "16") (pinfunction "VCC_16") (pintype "unspecified"))
      (node (ref "U5D") (pin "16") (pinfunction "VCC_16") (pintype "unspecified"))
      (node (ref "U5E") (pin "14") (pinfunction "VCC_14") (pintype "unspecified"))
      (node (ref "U5F") (pin "16") (pinfunction "VCC_16") (pintype "unspecified"))
      (node (ref "U6A") (pin "14") (pinfunction "VCC_14") (pintype "unspecified"))
      (node (ref "U6B") (pin "20") (pinfunction "VCC_20") (pintype "unspecified"))
      (node (ref "U6C") (pin "20") (pinfunction "VCC_20") (pintype "unspecified"))
      (node (ref "U6D") (pin "14") (pinfunction "VCC_14") (pintype "unspecified"))
      (node (ref "U6E") (pin "16") (pinfunction "VCC_16") (pintype "unspecified"))
      (node (ref "U6F") (pin "14") (pinfunction "VCC_14") (pintype "unspecified"))
      (node (ref "U7A") (pin "14") (pinfunction "VCC_14") (pintype "unspecified"))
      (node (ref "U7B") (pin "14") (pinfunction "VCC_14") (pintype "unspecified"))
      (node (ref "U7C") (pin "14") (pinfunction "VCC_14") (pintype "unspecified"))
      (node (ref "U7D") (pin "20") (pinfunction "VCC_20") (pintype "unspecified"))
      (node (ref "U7E") (pin "16") (pinfunction "VCC_16") (pintype "unspecified"))
      (node (ref "U7F") (pin "16") (pinfunction "VCC_16") (pintype "unspecified"))
      (node (ref "U8A") (pin "18") (pinfunction "VCC_18") (pintype "unspecified"))
      (node (ref "U8B") (pin "16") (pinfunction "VCC_16") (pintype "unspecified"))
      (node (ref "U8C") (pin "20") (pinfunction "VCC_20") (pintype "unspecified"))
      (node (ref "U8E") (pin "16") (pinfunction "VCC_16") (pintype "unspecified"))
      (node (ref "U8F") (pin "16") (pinfunction "VCC_16") (pintype "unspecified"))
      (node (ref "U9A") (pin "18") (pinfunction "VCC_18") (pintype "unspecified"))
      (node (ref "U9B") (pin "16") (pinfunction "VCC_16") (pintype "unspecified"))
      (node (ref "U9D") (pin "20") (pinfunction "VCC_20") (pintype "unspecified"))
      (node (ref "U9E") (pin "20") (pinfunction "VCC_20") (pintype "unspecified"))
      (node (ref "U9F") (pin "20") (pinfunction "VCC_20") (pintype "unspecified"))
    )
    (net (code "2") (name "+12V") (class "Default")
      (node (ref "CN1") (pin "61") (pinfunction "+12V_61") (pintype "unspecified"))
      (node (ref "R14") (pin "2") (pinfunction "2_2") (pintype "unspecified"))
      (node (ref "R17") (pin "2") (pinfunction "2_2") (pintype "unspecified"))
    )
    (net (code "3") (name "A1") (class "Default")
      (node (ref "CN1") (pin "47") (pinfunction "A1_47") (pintype "unspecified"))
      (node (ref "U15C") (pin "3") (pinfunction "2Y4_3") (pintype "unspecified"))
      (node (ref "U4E") (pin "13") (pinfunction "DI_13") (pintype "unspecified"))
      (node (ref "U4F") (pin "13") (pinfunction "A_13") (pintype "unspecified"))
      (node (ref "U7E") (pin "6") (pinfunction "1C0_6") (pintype "unspecified"))
    )
    (net (code "4") (name "A2") (class "Default")
      (node (ref "CN1") (pin "48") (pinfunction "A2_48") (pintype "unspecified"))
      (node (ref "U15C") (pin "5") (pinfunction "2Y3_5") (pintype "unspecified"))
      (node (ref "U4E") (pin "1") (pinfunction "A_1") (pintype "unspecified"))
      (node (ref "U4F") (pin "3") (pinfunction "B_3") (pintype "unspecified"))
      (node (ref "U7E") (pin "10") (pinfunction "2C0_10") (pintype "unspecified"))
    )
    (net (code "5") (name "A3") (class "Default")
      (node (ref "CN1") (pin "49") (pinfunction "A3_49") (pintype "unspecified"))
      (node (ref "U15C") (pin "7") (pinfunction "2Y2_7") (pintype "unspecified"))
      (node (ref "U4E") (pin "2") (pinfunction "B_2") (pintype "unspecified"))
      (node (ref "U4F") (pin "1") (pinfunction "1C_1") (pintype "unspecified"))
      (node (ref "U4F") (pin "15") (pinfunction "2C_15") (pintype "unspecified"))
      (node (ref "U6E") (pin "6") (pinfunction "1C0_6") (pintype "unspecified"))
    )
    (net (code "6") (name "A4") (class "Default")
      (node (ref "CN1") (pin "50") (pinfunction "A4_50") (pintype "unspecified"))
      (node (ref "U15C") (pin "9") (pinfunction "2Y1_9") (pintype "unspecified"))
      (node (ref "U4E") (pin "3") (pinfunction "C_3") (pintype "unspecified"))
      (node (ref "U6E") (pin "10") (pinfunction "2C0_10") (pintype "unspecified"))
    )
    (net (code "7") (name "A5") (class "Default")
      (node (ref "CN1") (pin "51") (pinfunction "A5_51") (pintype "unspecified"))
      (node (ref "U15C") (pin "12") (pinfunction "1Y4_12") (pintype "unspecified"))
      (node (ref "U5F") (pin "6") (pinfunction "1C0_6") (pintype "unspecified"))
    )
    (net (code "8") (name "A6") (class "Default")
      (node (ref "CN1") (pin "52") (pinfunction "A6_52") (pintype "unspecified"))
      (node (ref "U11E") (pin "4") (pinfunction "2D_4") (pintype "unspecified"))
      (node (ref "U15C") (pin "14") (pinfunction "1Y3_14") (pintype "unspecified"))
      (node (ref "U5F") (pin "10") (pinfunction "2C0_10") (pintype "unspecified"))
    )
    (net (code "9") (name "A7") (class "Default")
      (node (ref "CN1") (pin "53") (pinfunction "A7_53") (pintype "unspecified"))
      (node (ref "U11E") (pin "7") (pinfunction "3D_7") (pintype "unspecified"))
      (node (ref "U15C") (pin "16") (pinfunction "1Y2_16") (pintype "unspecified"))
      (node (ref "U8E") (pin "6") (pinfunction "1C0_6") (pintype "unspecified"))
    )
    (net (code "10") (name "A8") (class "Default")
      (node (ref "CN1") (pin "54") (pinfunction "A8_54") (pintype "unspecified"))
      (node (ref "U11E") (pin "8") (pinfunction "4D_8") (pintype "unspecified"))
      (node (ref "U15C") (pin "18") (pinfunction "1Y1_18") (pintype "unspecified"))
      (node (ref "U8E") (pin "10") (pinfunction "2C0_10") (pintype "unspecified"))
    )
    (net (code "11") (name "A9") (class "Default")
      (node (ref "CN1") (pin "55") (pinfunction "A9_55") (pintype "unspecified"))
      (node (ref "U11D") (pin "12") (pinfunction "5Q_12") (pintype "unspecified"))
      (node (ref "U11E") (pin "13") (pinfunction "5D_13") (pintype "unspecified"))
      (node (ref "U7E") (pin "4") (pinfunction "1C2_4") (pintype "unspecified"))
    )
    (net (code "12") (name "A10") (class "Default")
      (node (ref "CN1") (pin "56") (pinfunction "A10_56") (pintype "unspecified"))
      (node (ref "U11D") (pin "15") (pinfunction "6Q_15") (pintype "unspecified"))
      (node (ref "U11E") (pin "14") (pinfunction "6D_14") (pintype "unspecified"))
      (node (ref "U7E") (pin "12") (pinfunction "2C2_12") (pintype "unspecified"))
    )
    (net (code "13") (name "A11") (class "Default")
      (node (ref "CN1") (pin "57") (pinfunction "A11_57") (pintype "unspecified"))
      (node (ref "U11D") (pin "16") (pinfunction "7Q_16") (pintype "unspecified"))
      (node (ref "U11E") (pin "17") (pinfunction "7D_17") (pintype "unspecified"))
      (node (ref "U14F") (pin "14") (pinfunction "2A_14") (pintype "unspecified"))
      (node (ref "U6E") (pin "4") (pinfunction "1C2_4") (pintype "unspecified"))
    )
    (net (code "14") (name "A12") (class "Default")
      (node (ref "CN1") (pin "58") (pinfunction "A12_58") (pintype "unspecified"))
      (node (ref "U11D") (pin "19") (pinfunction "8Q_19") (pintype "unspecified"))
      (node (ref "U11E") (pin "18") (pinfunction "8D_18") (pintype "unspecified"))
      (node (ref "U14F") (pin "13") (pinfunction "2B_13") (pintype "unspecified"))
      (node (ref "U6E") (pin "12") (pinfunction "2C2_12") (pintype "unspecified"))
    )
    (net (code "15") (name "A13") (class "Default")
      (node (ref "U13E") (pin "3") (pinfunction "1D_3") (pintype "unspecified"))
      (node (ref "U5F") (pin "4") (pinfunction "1C2_4") (pintype "unspecified"))
      (node (ref "U7D") (pin "2") (pinfunction "1Q_2") (pintype "unspecified"))
      (node (ref "U9D") (pin "2") (pinfunction "1Q_2") (pintype "unspecified"))
    )
    (net (code "16") (name "A14") (class "Default")
      (node (ref "U13E") (pin "4") (pinfunction "2D_4") (pintype "unspecified"))
      (node (ref "U5F") (pin "12") (pinfunction "2C2_12") (pintype "unspecified"))
      (node (ref "U7D") (pin "5") (pinfunction "2Q_5") (pintype "unspecified"))
      (node (ref "U9D") (pin "5") (pinfunction "2Q_5") (pintype "unspecified"))
    )
    (net (code "17") (name "A15") (class "Default")
      (node (ref "U11C") (pin "6") (pinfunction "3Q_6") (pintype "unspecified"))
      (node (ref "U13E") (pin "7") (pinfunction "3D_7") (pintype "unspecified"))
      (node (ref "U7D") (pin "6") (pinfunction "3Q_6") (pintype "unspecified"))
      (node (ref "U8E") (pin "3") (pinfunction "1C3_3") (pintype "unspecified"))
      (node (ref "U8E") (pin "4") (pinfunction "1C2_4") (pintype "unspecified"))
      (node (ref "U9D") (pin "6") (pinfunction "3Q_6") (pintype "unspecified"))
    )
    (net (code "18") (name "A16") (class "Default")
      (node (ref "CN1") (pin "102") (pinfunction "A16_102") (pintype "unspecified"))
      (node (ref "U11C") (pin "9") (pinfunction "4Q_9") (pintype "unspecified"))
      (node (ref "U13E") (pin "8") (pinfunction "4D_8") (pintype "unspecified"))
      (node (ref "U7D") (pin "9") (pinfunction "4Q_9") (pintype "unspecified"))
      (node (ref "U8E") (pin "12") (pinfunction "2C2_12") (pintype "unspecified"))
      (node (ref "U8E") (pin "13") (pinfunction "2C3_13") (pintype "unspecified"))
      (node (ref "U9D") (pin "9") (pinfunction "4Q_9") (pintype "unspecified"))
    )
    (net (code "19") (name "A17") (class "Default")
      (node (ref "CN1") (pin "103") (pinfunction "A17_103") (pintype "unspecified"))
      (node (ref "U11C") (pin "12") (pinfunction "5Q_12") (pintype "unspecified"))
      (node (ref "U13E") (pin "13") (pinfunction "5D_13") (pintype "unspecified"))
      (node (ref "U7D") (pin "12") (pinfunction "5Q_12") (pintype "unspecified"))
      (node (ref "U9D") (pin "12") (pinfunction "5Q_12") (pintype "unspecified"))
    )
    (net (code "20") (name "A18") (class "Default")
      (node (ref "CN1") (pin "104") (pinfunction "A18_104") (pintype "unspecified"))
      (node (ref "U11C") (pin "15") (pinfunction "6Q_15") (pintype "unspecified"))
      (node (ref "U13E") (pin "14") (pinfunction "6D_14") (pintype "unspecified"))
      (node (ref "U7D") (pin "15") (pinfunction "6Q_15") (pintype "unspecified"))
      (node (ref "U9D") (pin "15") (pinfunction "6Q_15") (pintype "unspecified"))
    )
    (net (code "21") (name "A19") (class "Default")
      (node (ref "CN1") (pin "105") (pinfunction "A19_105") (pintype "unspecified"))
      (node (ref "U11C") (pin "16") (pinfunction "7Q_16") (pintype "unspecified"))
      (node (ref "U13E") (pin "17") (pinfunction "7D_17") (pintype "unspecified"))
      (node (ref "U7D") (pin "16") (pinfunction "7Q_16") (pintype "unspecified"))
      (node (ref "U9D") (pin "16") (pinfunction "7Q_16") (pintype "unspecified"))
    )
    (net (code "22") (name "A20") (class "Default")
      (node (ref "CN1") (pin "110") (pinfunction "A20_110") (pintype "unspecified"))
      (node (ref "U11C") (pin "19") (pinfunction "8Q_19") (pintype "unspecified"))
      (node (ref "U13E") (pin "18") (pinfunction "8D_18") (pintype "unspecified"))
      (node (ref "U7D") (pin "19") (pinfunction "8Q_19") (pintype "unspecified"))
      (node (ref "U9D") (pin "19") (pinfunction "8Q_19") (pintype "unspecified"))
    )
    (net (code "23") (name "ACCK") (class "Default")
      (node (ref "U10B") (pin "7") (pinfunction "C0_7") (pintype "unspecified"))
      (node (ref "U3D") (pin "3") (pinfunction "1C_3") (pintype "unspecified"))
      (node (ref "U4D") (pin "1") (pinfunction "1A_1") (pintype "unspecified"))
      (node (ref "U9B") (pin "9") (pinfunction "C4_9") (pintype "unspecified"))
    )
    (net (code "24") (name "AS") (class "Default")
      (node (ref "U2B") (pin "15") (pinfunction "2CLR_15") (pintype "unspecified"))
      (node (ref "U2E") (pin "13") (pinfunction "6A_13") (pintype "unspecified"))
      (node (ref "U3A") (pin "5") (pinfunction "1PR_5") (pintype "unspecified"))
      (node (ref "U3B") (pin "1") (pinfunction "1CLR_1") (pintype "unspecified"))
      (node (ref "U3B") (pin "15") (pinfunction "2CLR_15") (pintype "unspecified"))
      (node (ref "U4B") (pin "1") (pinfunction "1CLR_1") (pintype "unspecified"))
      (node (ref "U6A") (pin "1") (pinfunction "1Y_1") (pintype "unspecified"))
    )
    (net (code "25") (name "B+{slash}L") (class "Default")
      (node (ref "U10A") (pin "6") (pinfunction "A1_6") (pintype "unspecified"))
      (node (ref "U5B") (pin "8") (pinfunction "3A_8") (pintype "unspecified"))
      (node (ref "U6D") (pin "8") (pinfunction "/3Y_8") (pintype "unspecified"))
      (node (ref "U8A") (pin "6") (pinfunction "A1_6") (pintype "unspecified"))
      (node (ref "U9A") (pin "6") (pinfunction "A1_6") (pintype "unspecified"))
    )
    (net (code "26") (name "BD0") (class "Default")
      (node (ref "CN1") (pin "27") (pinfunction "BD0_27") (pintype "unspecified"))
      (node (ref "U11E") (pin "2") (pinfunction "1Q_2") (pintype "unspecified"))
      (node (ref "U15E") (pin "2") (pinfunction "A1_2") (pintype "unspecified"))
      (node (ref "U9E") (pin "18") (pinfunction "1Y1_18") (pintype "unspecified"))
      (node (ref "U9F") (pin "18") (pinfunction "B1_18") (pintype "unspecified"))
    )
    (net (code "27") (name "BD1") (class "Default")
      (node (ref "CN1") (pin "28") (pinfunction "BD1_28") (pintype "unspecified"))
      (node (ref "U11E") (pin "5") (pinfunction "2Q_5") (pintype "unspecified"))
      (node (ref "U15E") (pin "3") (pinfunction "A2_3") (pintype "unspecified"))
      (node (ref "U9E") (pin "16") (pinfunction "1Y2_16") (pintype "unspecified"))
      (node (ref "U9F") (pin "17") (pinfunction "B2_17") (pintype "unspecified"))
    )
    (net (code "28") (name "BD2") (class "Default")
      (node (ref "CN1") (pin "29") (pinfunction "BD2_29") (pintype "unspecified"))
      (node (ref "U11E") (pin "6") (pinfunction "3Q_6") (pintype "unspecified"))
      (node (ref "U15E") (pin "4") (pinfunction "A3_4") (pintype "unspecified"))
      (node (ref "U9E") (pin "14") (pinfunction "1Y3_14") (pintype "unspecified"))
      (node (ref "U9F") (pin "16") (pinfunction "B3_16") (pintype "unspecified"))
    )
    (net (code "29") (name "BD3") (class "Default")
      (node (ref "CN1") (pin "30") (pinfunction "BD3_30") (pintype "unspecified"))
      (node (ref "U11E") (pin "9") (pinfunction "4Q_9") (pintype "unspecified"))
      (node (ref "U15E") (pin "5") (pinfunction "A4_5") (pintype "unspecified"))
      (node (ref "U9E") (pin "12") (pinfunction "1Y4_12") (pintype "unspecified"))
      (node (ref "U9F") (pin "15") (pinfunction "B4_15") (pintype "unspecified"))
    )
    (net (code "30") (name "BD4") (class "Default")
      (node (ref "CN1") (pin "31") (pinfunction "BD4_31") (pintype "unspecified"))
      (node (ref "U11E") (pin "12") (pinfunction "5Q_12") (pintype "unspecified"))
      (node (ref "U15E") (pin "6") (pinfunction "A5_6") (pintype "unspecified"))
      (node (ref "U9E") (pin "9") (pinfunction "2Y1_9") (pintype "unspecified"))
      (node (ref "U9F") (pin "14") (pinfunction "B5_14") (pintype "unspecified"))
    )
    (net (code "31") (name "BD5") (class "Default")
      (node (ref "CN1") (pin "32") (pinfunction "BD5_32") (pintype "unspecified"))
      (node (ref "U11E") (pin "15") (pinfunction "6Q_15") (pintype "unspecified"))
      (node (ref "U15E") (pin "7") (pinfunction "A6_7") (pintype "unspecified"))
      (node (ref "U7D") (pin "3") (pinfunction "1D_3") (pintype "unspecified"))
      (node (ref "U9E") (pin "7") (pinfunction "2Y2_7") (pintype "unspecified"))
      (node (ref "U9F") (pin "13") (pinfunction "B6_13") (pintype "unspecified"))
    )
    (net (code "32") (name "BD6") (class "Default")
      (node (ref "CN1") (pin "33") (pinfunction "BD6_33") (pintype "unspecified"))
      (node (ref "U11E") (pin "16") (pinfunction "7Q_16") (pintype "unspecified"))
      (node (ref "U15E") (pin "8") (pinfunction "A7_8") (pintype "unspecified"))
      (node (ref "U7D") (pin "4") (pinfunction "2D_4") (pintype "unspecified"))
      (node (ref "U9E") (pin "5") (pinfunction "2Y3_5") (pintype "unspecified"))
      (node (ref "U9F") (pin "12") (pinfunction "B7_12") (pintype "unspecified"))
    )
    (net (code "33") (name "BD7") (class "Default")
      (node (ref "CN1") (pin "34") (pinfunction "BD7_34") (pintype "unspecified"))
      (node (ref "U11E") (pin "19") (pinfunction "8Q_19") (pintype "unspecified"))
      (node (ref "U15E") (pin "9") (pinfunction "A8_9") (pintype "unspecified"))
      (node (ref "U7D") (pin "7") (pinfunction "3D_7") (pintype "unspecified"))
      (node (ref "U9E") (pin "3") (pinfunction "2Y4_3") (pintype "unspecified"))
      (node (ref "U9F") (pin "11") (pinfunction "B8_11") (pintype "unspecified"))
    )
    (net (code "34") (name "BD8") (class "Default")
      (node (ref "CN1") (pin "35") (pinfunction "BD8_35") (pintype "unspecified"))
      (node (ref "U11F") (pin "18") (pinfunction "B1_18") (pintype "unspecified"))
      (node (ref "U13E") (pin "2") (pinfunction "1Q_2") (pintype "unspecified"))
      (node (ref "U14E") (pin "2") (pinfunction "A1_2") (pintype "unspecified"))
      (node (ref "U7D") (pin "8") (pinfunction "4D_8") (pintype "unspecified"))
    )
    (net (code "35") (name "BD9") (class "Default")
      (node (ref "CN1") (pin "36") (pinfunction "BD9_36") (pintype "unspecified"))
      (node (ref "U11F") (pin "17") (pinfunction "B2_17") (pintype "unspecified"))
      (node (ref "U13E") (pin "5") (pinfunction "2Q_5") (pintype "unspecified"))
      (node (ref "U14E") (pin "3") (pinfunction "A2_3") (pintype "unspecified"))
      (node (ref "U7D") (pin "13") (pinfunction "5D_13") (pintype "unspecified"))
    )
    (net (code "36") (name "BD10") (class "Default")
      (node (ref "CN1") (pin "37") (pinfunction "BD10_37") (pintype "unspecified"))
      (node (ref "U11F") (pin "16") (pinfunction "B3_16") (pintype "unspecified"))
      (node (ref "U13E") (pin "6") (pinfunction "3Q_6") (pintype "unspecified"))
      (node (ref "U14E") (pin "4") (pinfunction "A3_4") (pintype "unspecified"))
      (node (ref "U7D") (pin "14") (pinfunction "6D_14") (pintype "unspecified"))
    )
    (net (code "37") (name "BD11") (class "Default")
      (node (ref "CN1") (pin "38") (pinfunction "BD11_38") (pintype "unspecified"))
      (node (ref "U11F") (pin "15") (pinfunction "B4_15") (pintype "unspecified"))
      (node (ref "U13E") (pin "9") (pinfunction "4Q_9") (pintype "unspecified"))
      (node (ref "U14E") (pin "5") (pinfunction "A4_5") (pintype "unspecified"))
      (node (ref "U7D") (pin "17") (pinfunction "7D_17") (pintype "unspecified"))
    )
    (net (code "38") (name "BD12") (class "Default")
      (node (ref "CN1") (pin "39") (pinfunction "BD12_39") (pintype "unspecified"))
      (node (ref "U11F") (pin "14") (pinfunction "B5_14") (pintype "unspecified"))
      (node (ref "U13E") (pin "12") (pinfunction "5Q_12") (pintype "unspecified"))
      (node (ref "U14E") (pin "6") (pinfunction "A5_6") (pintype "unspecified"))
      (node (ref "U7D") (pin "18") (pinfunction "8D_18") (pintype "unspecified"))
    )
    (net (code "39") (name "BD13") (class "Default")
      (node (ref "CN1") (pin "40") (pinfunction "BD13_40") (pintype "unspecified"))
      (node (ref "U11F") (pin "13") (pinfunction "B6_13") (pintype "unspecified"))
      (node (ref "U13E") (pin "15") (pinfunction "6Q_15") (pintype "unspecified"))
      (node (ref "U14E") (pin "7") (pinfunction "A6_7") (pintype "unspecified"))
    )
    (net (code "40") (name "BD14") (class "Default")
      (node (ref "CN1") (pin "41") (pinfunction "BD14_41") (pintype "unspecified"))
      (node (ref "U11F") (pin "12") (pinfunction "B7_12") (pintype "unspecified"))
      (node (ref "U13E") (pin "16") (pinfunction "7Q_16") (pintype "unspecified"))
      (node (ref "U14E") (pin "8") (pinfunction "A7_8") (pintype "unspecified"))
    )
    (net (code "41") (name "BD15") (class "Default")
      (node (ref "CN1") (pin "42") (pinfunction "BD15_42") (pintype "unspecified"))
      (node (ref "U11F") (pin "11") (pinfunction "B8_11") (pintype "unspecified"))
      (node (ref "U13E") (pin "19") (pinfunction "8Q_19") (pintype "unspecified"))
      (node (ref "U14E") (pin "9") (pinfunction "A8_9") (pintype "unspecified"))
    )
    (net (code "42") (name "BGACK") (class "Default")
      (node (ref "U11D") (pin "1") (pinfunction "/OE_1") (pintype "unspecified"))
      (node (ref "U15C") (pin "1") (pinfunction "1G_1") (pintype "unspecified"))
      (node (ref "U15C") (pin "19") (pinfunction "2G_19") (pintype "unspecified"))
      (node (ref "U3D") (pin "1") (pinfunction "1A_1") (pintype "unspecified"))
      (node (ref "U3D") (pin "8") (pinfunction "2B_8") (pintype "unspecified"))
      (node (ref "U6A") (pin "13") (pinfunction "4Y_13") (pintype "unspecified"))
      (node (ref "U6D") (pin "4") (pinfunction "2A_4") (pintype "unspecified"))
      (node (ref "U7C") (pin "12") (pinfunction "4A_12") (pintype "unspecified"))
      (node (ref "U8C") (pin "19") (pinfunction "2G_19") (pintype "unspecified"))
    )
    (net (code "43") (name "CAS") (class "Default")
      (node (ref "U10C") (pin "3") (pinfunction "2A_3") (pintype "unspecified"))
      (node (ref "U2C") (pin "1") (pinfunction "1A_1") (pintype "unspecified"))
      (node (ref "U3A") (pin "4") (pinfunction "CLK_4") (pintype "unspecified"))
      (node (ref "U3C") (pin "9") (pinfunction "/2Q_9") (pintype "unspecified"))
    )
    (net (code "44") (name "CK") (class "Default")
      (node (ref "U1C") (pin "2") (pinfunction "CK_2") (pintype "unspecified"))
      (node (ref "U1E") (pin "6") (pinfunction "/2Y_6") (pintype "unspecified"))
      (node (ref "U2B") (pin "12") (pinfunction "CLK_12") (pintype "unspecified"))
      (node (ref "U2B") (pin "4") (pinfunction "CLK_4") (pintype "unspecified"))
      (node (ref "U3A") (pin "12") (pinfunction "CLK_12") (pintype "unspecified"))
      (node (ref "U3B") (pin "12") (pinfunction "CLK_12") (pintype "unspecified"))
      (node (ref "U3B") (pin "4") (pinfunction "CLK_4") (pintype "unspecified"))
      (node (ref "U3C") (pin "12") (pinfunction "CLK_12") (pintype "unspecified"))
      (node (ref "U3C") (pin "4") (pinfunction "CLK_4") (pintype "unspecified"))
      (node (ref "U4B") (pin "12") (pinfunction "CLK_12") (pintype "unspecified"))
      (node (ref "U4B") (pin "4") (pinfunction "CLK_4") (pintype "unspecified"))
    )
    (net (code "45") (name "CLR") (class "Default")
      (node (ref "RP2") (pin "4") (pinfunction "+5V_4") (pintype "unspecified"))
      (node (ref "U3E") (pin "1") (pinfunction "1CLR_1") (pintype "unspecified"))
      (node (ref "U3E") (pin "11") (pinfunction "2PR_11") (pintype "unspecified"))
      (node (ref "U3E") (pin "15") (pinfunction "2CLR_15") (pintype "unspecified"))
      (node (ref "U7F") (pin "9") (pinfunction "CLR_9") (pintype "unspecified"))
      (node (ref "U8F") (pin "9") (pinfunction "CLR_9") (pintype "unspecified"))
    )
    (net (code "46") (name "CMUX") (class "Default")
      (node (ref "U11C") (pin "1") (pinfunction "/OE_1") (pintype "unspecified"))
      (node (ref "U15F") (pin "10") (pinfunction "3B_10") (pintype "unspecified"))
      (node (ref "U2D") (pin "10") (pinfunction "B3_10") (pintype "unspecified"))
      (node (ref "U4A") (pin "4") (pinfunction "2A_4") (pintype "unspecified"))
      (node (ref "U4B") (pin "10") (pinfunction "2Q_10") (pintype "unspecified"))
      (node (ref "U6D") (pin "5") (pinfunction "2B_5") (pintype "unspecified"))
    )
    (net (code "47") (name "CPUC1") (class "Default")
      (node (ref "U1A") (pin "1") (pinfunction "A1_1") (pintype "unspecified"))
      (node (ref "U2B") (pin "6") (pinfunction "1Q_6") (pintype "unspecified"))
      (node (ref "U5A") (pin "9") (pinfunction "3A_9") (pintype "unspecified"))
      (node (ref "U7C") (pin "13") (pinfunction "4B_13") (pintype "unspecified"))
    )
    (net (code "48") (name "CPUCK") (class "Default")
      (node (ref "CN1") (pin "22") (pinfunction "CPUCK_22") (pintype "unspecified"))
      (node (ref "R10") (pin "1") (pinfunction "1_1") (pintype "unspecified"))
    )
    (net (code "49") (name "DOTCK") (class "Default")
      (node (ref "CN1") (pin "106") (pinfunction "DOTCK_106") (pintype "unspecified"))
      (node (ref "U1E") (pin "8") (pinfunction "/3Y_8") (pintype "unspecified"))
      (node (ref "U3E") (pin "12") (pinfunction "CLK_12") (pintype "unspecified"))
      (node (ref "U3E") (pin "4") (pinfunction "CLK_4") (pintype "unspecified"))
      (node (ref "U5D") (pin "12") (pinfunction "CLK_12") (pintype "unspecified"))
      (node (ref "U5D") (pin "4") (pinfunction "CLK_4") (pintype "unspecified"))
      (node (ref "U7F") (pin "7") (pinfunction "CLK_7") (pintype "unspecified"))
      (node (ref "U8F") (pin "7") (pinfunction "CLK_7") (pintype "unspecified"))
    )
    (net (code "50") (name "E") (class "Default")
      (node (ref "CN1") (pin "16") (pinfunction "E_16") (pintype "unspecified"))
      (node (ref "U8C") (pin "14") (pinfunction "1Y3_14") (pintype "unspecified"))
    )
    (net (code "51") (name "FC2") (class "Default")
      (node (ref "U10C") (pin "11") (pinfunction "3C_11") (pintype "unspecified"))
      (node (ref "U13A") (pin "26") (pinfunction "FC2_26") (pintype "unspecified"))
      (node (ref "U7C") (pin "2") (pinfunction "1B_2") (pintype "unspecified"))
    )
    (net (code "52") (name "GND") (class "Default")
      (node (ref "C1") (pin "2") (pinfunction "GND_2") (pintype "unspecified"))
      (node (ref "C10") (pin "2") (pinfunction "GND_2") (pintype "unspecified"))
      (node (ref "C11") (pin "2") (pinfunction "GND_2") (pintype "unspecified"))
      (node (ref "C12") (pin "2") (pinfunction "GND_2") (pintype "unspecified"))
      (node (ref "C13") (pin "2") (pinfunction "GND_2") (pintype "unspecified"))
      (node (ref "C14") (pin "2") (pinfunction "GND_2") (pintype "unspecified"))
      (node (ref "C15") (pin "2") (pinfunction "GND_2") (pintype "unspecified"))
      (node (ref "C16") (pin "2") (pinfunction "GND_2") (pintype "unspecified"))
      (node (ref "C17") (pin "2") (pinfunction "GND_2") (pintype "unspecified"))
      (node (ref "C18") (pin "2") (pinfunction "GND_2") (pintype "unspecified"))
      (node (ref "C19") (pin "1") (pinfunction "1_1") (pintype "unspecified"))
      (node (ref "C2") (pin "2") (pinfunction "GND_2") (pintype "unspecified"))
      (node (ref "C20") (pin "2") (pinfunction "GND_2") (pintype "unspecified"))
      (node (ref "C21") (pin "1") (pinfunction "1_1") (pintype "unspecified"))
      (node (ref "C22") (pin "2") (pinfunction "GND_2") (pintype "unspecified"))
      (node (ref "C23") (pin "2") (pinfunction "GND_2") (pintype "unspecified"))
      (node (ref "C24") (pin "2") (pinfunction "GND_2") (pintype "unspecified"))
      (node (ref "C25") (pin "2") (pinfunction "GND_2") (pintype "unspecified"))
      (node (ref "C26") (pin "2") (pinfunction "GND_2") (pintype "unspecified"))
      (node (ref "C27") (pin "2") (pinfunction "GND_2") (pintype "unspecified"))
      (node (ref "C28") (pin "2") (pinfunction "GND_2") (pintype "unspecified"))
      (node (ref "C29") (pin "2") (pinfunction "GND_2") (pintype "unspecified"))
      (node (ref "C3") (pin "2") (pinfunction "GND_2") (pintype "unspecified"))
      (node (ref "C30") (pin "2") (pinfunction "GND_2") (pintype "unspecified"))
      (node (ref "C31") (pin "2") (pinfunction "GND_2") (pintype "unspecified"))
      (node (ref "C32") (pin "2") (pinfunction "GND_2") (pintype "unspecified"))
      (node (ref "C33") (pin "2") (pinfunction "GND_2") (pintype "unspecified"))
      (node (ref "C34") (pin "2") (pinfunction "GND_2") (pintype "unspecified"))
      (node (ref "C35") (pin "2") (pinfunction "GND_2") (pintype "unspecified"))
      (node (ref "C36") (pin "2") (pinfunction "GND_2") (pintype "unspecified"))
      (node (ref "C37") (pin "2") (pinfunction "GND_2") (pintype "unspecified"))
      (node (ref "C38") (pin "2") (pinfunction "GND_2") (pintype "unspecified"))
      (node (ref "C39") (pin "2") (pinfunction "2_2") (pintype "unspecified"))
      (node (ref "C4") (pin "2") (pinfunction "GND_2") (pintype "unspecified"))
      (node (ref "C40") (pin "2") (pinfunction "2_2") (pintype "unspecified"))
      (node (ref "C41") (pin "2") (pinfunction "GND_2") (pintype "unspecified"))
      (node (ref "C42") (pin "2") (pinfunction "2_2") (pintype "unspecified"))
      (node (ref "C43") (pin "1") (pinfunction "1_1") (pintype "unspecified"))
      (node (ref "C5") (pin "2") (pinfunction "GND_2") (pintype "unspecified"))
      (node (ref "C6") (pin "2") (pinfunction "GND_2") (pintype "unspecified"))
      (node (ref "C7") (pin "2") (pinfunction "GND_2") (pintype "unspecified"))
      (node (ref "C8") (pin "2") (pinfunction "2_2") (pintype "unspecified"))
      (node (ref "CN1") (pin "117") (pinfunction "DGND_117") (pintype "unspecified"))
      (node (ref "CN1") (pin "118") (pinfunction "DGND_118") (pintype "unspecified"))
      (node (ref "CN1") (pin "17") (pinfunction "DGND_17") (pintype "unspecified"))
      (node (ref "CN1") (pin "18") (pinfunction "DGND_18") (pintype "unspecified"))
      (node (ref "CN1") (pin "43") (pinfunction "DGND_43") (pintype "unspecified"))
      (node (ref "CN1") (pin "44") (pinfunction "DGND_44") (pintype "unspecified"))
      (node (ref "CN1") (pin "89") (pinfunction "DGND_89") (pintype "unspecified"))
      (node (ref "CN1") (pin "90") (pinfunction "DGND_90") (pintype "unspecified"))
      (node (ref "L1") (pin "2") (pinfunction "2_2") (pintype "unspecified"))
      (node (ref "R13") (pin "1") (pinfunction "1_1") (pintype "unspecified"))
      (node (ref "R16") (pin "1") (pinfunction "1_1") (pintype "unspecified"))
      (node (ref "R9") (pin "1") (pinfunction "1_1") (pintype "unspecified"))
      (node (ref "U10A") (pin "9") (pinfunction "GND_9") (pintype "unspecified"))
      (node (ref "U10B") (pin "11") (pinfunction "B4_11") (pintype "unspecified"))
      (node (ref "U10B") (pin "15") (pinfunction "B3_15") (pintype "unspecified"))
      (node (ref "U10B") (pin "2") (pinfunction "B2_2") (pintype "unspecified"))
      (node (ref "U10B") (pin "6") (pinfunction "B1_6") (pintype "unspecified"))
      (node (ref "U10B") (pin "8") (pinfunction "GND_8") (pintype "unspecified"))
      (node (ref "U10C") (pin "7") (pinfunction "GND_7") (pintype "unspecified"))
      (node (ref "U11A") (pin "10") (pinfunction "GND_10") (pintype "unspecified"))
      (node (ref "U11B") (pin "10") (pinfunction "GND_10") (pintype "unspecified"))
      (node (ref "U11C") (pin "10") (pinfunction "GND_10") (pintype "unspecified"))
      (node (ref "U11C") (pin "3") (pinfunction "1D_3") (pintype "unspecified"))
      (node (ref "U11C") (pin "4") (pinfunction "2D_4") (pintype "unspecified"))
      (node (ref "U11D") (pin "10") (pinfunction "GND_10") (pintype "unspecified"))
      (node (ref "U11E") (pin "10") (pinfunction "GND_10") (pintype "unspecified"))
      (node (ref "U11F") (pin "10") (pinfunction "GND_10") (pintype "unspecified"))
      (node (ref "U12F") (pin "5") (pinfunction "E1_5") (pintype "unspecified"))
      (node (ref "U12F") (pin "8") (pinfunction "GND_8") (pintype "unspecified"))
      (node (ref "U13A") (pin "16") (pinfunction "GND_16") (pintype "unspecified"))
      (node (ref "U13A") (pin "53") (pinfunction "GND_53") (pintype "unspecified"))
      (node (ref "U13D") (pin "14") (pinfunction "GND_14") (pintype "unspecified"))
      (node (ref "U13D") (pin "20") (pinfunction "CE_20") (pintype "unspecified"))
      (node (ref "U13E") (pin "10") (pinfunction "GND_10") (pintype "unspecified"))
      (node (ref "U13F") (pin "8") (pinfunction "GND_8") (pintype "unspecified"))
      (node (ref "U14D") (pin "14") (pinfunction "GND_14") (pintype "unspecified"))
      (node (ref "U14D") (pin "20") (pinfunction "CE_20") (pintype "unspecified"))
      (node (ref "U14E") (pin "10") (pinfunction "GND_10") (pintype "unspecified"))
      (node (ref "U14F") (pin "8") (pinfunction "GND_8") (pintype "unspecified"))
      (node (ref "U15B") (pin "7") (pinfunction "GND_7") (pintype "unspecified"))
      (node (ref "U15C") (pin "10") (pinfunction "GND_10") (pintype "unspecified"))
      (node (ref "U15E") (pin "10") (pinfunction "GND_10") (pintype "unspecified"))
      (node (ref "U15F") (pin "7") (pinfunction "GND_7") (pintype "unspecified"))
      (node (ref "U1A") (pin "7") (pinfunction "GND_7") (pintype "unspecified"))
      (node (ref "U1B") (pin "7") (pinfunction "GND_7") (pintype "unspecified"))
      (node (ref "U1C") (pin "10") (pinfunction "ET_10") (pintype "unspecified"))
      (node (ref "U1C") (pin "3") (pinfunction "P0_3") (pintype "unspecified"))
      (node (ref "U1C") (pin "4") (pinfunction "P1_4") (pintype "unspecified"))
      (node (ref "U1C") (pin "5") (pinfunction "P2_5") (pintype "unspecified"))
      (node (ref "U1C") (pin "6") (pinfunction "P3_6") (pintype "unspecified"))
      (node (ref "U1C") (pin "7") (pinfunction "EP_7") (pintype "unspecified"))
      (node (ref "U1C") (pin "8") (pinfunction "GND_8") (pintype "unspecified"))
      (node (ref "U1D") (pin "4") (pinfunction "G2A_4") (pintype "unspecified"))
      (node (ref "U1D") (pin "5") (pinfunction "G2B_5") (pintype "unspecified"))
      (node (ref "U1D") (pin "8") (pinfunction "GND_8") (pintype "unspecified"))
      (node (ref "U1E") (pin "7") (pinfunction "GND_7") (pintype "unspecified"))
      (node (ref "U2B") (pin "8") (pinfunction "GND_8") (pintype "unspecified"))
      (node (ref "U2C") (pin "7") (pinfunction "GND_7") (pintype "unspecified"))
      (node (ref "U2D") (pin "7") (pinfunction "GND_7") (pintype "unspecified"))
      (node (ref "U2E") (pin "7") (pinfunction "GND_7") (pintype "unspecified"))
      (node (ref "U3A") (pin "2") (pinfunction "1J_2") (pintype "unspecified"))
      (node (ref "U3A") (pin "8") (pinfunction "GND_8") (pintype "unspecified"))
      (node (ref "U3B") (pin "8") (pinfunction "GND_8") (pintype "unspecified"))
      (node (ref "U3C") (pin "8") (pinfunction "GND_8") (pintype "unspecified"))
      (node (ref "U3D") (pin "7") (pinfunction "GND_7") (pintype "unspecified"))
      (node (ref "U3E") (pin "8") (pinfunction "GND_8") (pintype "unspecified"))
      (node (ref "U4A") (pin "10") (pinfunction "3B_10") (pintype "unspecified"))
      (node (ref "U4A") (pin "7") (pinfunction "GND_7") (pintype "unspecified"))
      (node (ref "U4A") (pin "9") (pinfunction "3A_9") (pintype "unspecified"))
      (node (ref "U4B") (pin "8") (pinfunction "GND_8") (pintype "unspecified"))
      (node (ref "U4D") (pin "12") (pinfunction "4A_12") (pintype "unspecified"))
      (node (ref "U4D") (pin "7") (pinfunction "GND_7") (pintype "unspecified"))
      (node (ref "U4E") (pin "8") (pinfunction "GND_8") (pintype "unspecified"))
      (node (ref "U4F") (pin "8") (pinfunction "GND_8") (pintype "unspecified"))
      (node (ref "U5A") (pin "7") (pinfunction "GND_7") (pintype "unspecified"))
      (node (ref "U5B") (pin "7") (pinfunction "GND_7") (pintype "unspecified"))
      (node (ref "U5C") (pin "8") (pinfunction "GND_8") (pintype "unspecified"))
      (node (ref "U5D") (pin "2") (pinfunction "1J_2") (pintype "unspecified"))
      (node (ref "U5D") (pin "8") (pinfunction "GND_8") (pintype "unspecified"))
      (node (ref "U5E") (pin "7") (pinfunction "GND_7") (pintype "unspecified"))
      (node (ref "U5F") (pin "1") (pinfunction "1G_1") (pintype "unspecified"))
      (node (ref "U5F") (pin "15") (pinfunction "2G_15") (pintype "unspecified"))
      (node (ref "U5F") (pin "8") (pinfunction "GND_8") (pintype "unspecified"))
      (node (ref "U6A") (pin "7") (pinfunction "GND_7") (pintype "unspecified"))
      (node (ref "U6B") (pin "1") (pinfunction "/OE_1") (pintype "unspecified"))
      (node (ref "U6B") (pin "10") (pinfunction "GND_10") (pintype "unspecified"))
      (node (ref "U6C") (pin "10") (pinfunction "GND_10") (pintype "unspecified"))
      (node (ref "U6C") (pin "15") (pinfunction "E1_15") (pintype "unspecified"))
      (node (ref "U6C") (pin "16") (pinfunction "E2_16") (pintype "unspecified"))
      (node (ref "U6D") (pin "7") (pinfunction "GND_7") (pintype "unspecified"))
      (node (ref "U6E") (pin "1") (pinfunction "1G_1") (pintype "unspecified"))
      (node (ref "U6E") (pin "15") (pinfunction "2G_15") (pintype "unspecified"))
      (node (ref "U6E") (pin "8") (pinfunction "GND_8") (pintype "unspecified"))
      (node (ref "U6F") (pin "7") (pinfunction "GND_7") (pintype "unspecified"))
      (node (ref "U7A") (pin "7") (pinfunction "GND_7") (pintype "unspecified"))
      (node (ref "U7B") (pin "7") (pinfunction "GND_7") (pintype "unspecified"))
      (node (ref "U7C") (pin "7") (pinfunction "GND_7") (pintype "unspecified"))
      (node (ref "U7D") (pin "10") (pinfunction "GND_10") (pintype "unspecified"))
      (node (ref "U7E") (pin "1") (pinfunction "1G_1") (pintype "unspecified"))
      (node (ref "U7E") (pin "15") (pinfunction "2G_15") (pintype "unspecified"))
      (node (ref "U7E") (pin "8") (pinfunction "GND_8") (pintype "unspecified"))
      (node (ref "U7F") (pin "8") (pinfunction "GND_8") (pintype "unspecified"))
      (node (ref "U8A") (pin "8") (pinfunction "CS_8") (pintype "unspecified"))
      (node (ref "U8A") (pin "9") (pinfunction "GND_9") (pintype "unspecified"))
      (node (ref "U8B") (pin "8") (pinfunction "GND_8") (pintype "unspecified"))
      (node (ref "U8C") (pin "1") (pinfunction "1G_1") (pintype "unspecified"))
      (node (ref "U8C") (pin "10") (pinfunction "GND_10") (pintype "unspecified"))
      (node (ref "U8E") (pin "1") (pinfunction "1G_1") (pintype "unspecified"))
      (node (ref "U8E") (pin "15") (pinfunction "2G_15") (pintype "unspecified"))
      (node (ref "U8E") (pin "8") (pinfunction "GND_8") (pintype "unspecified"))
      (node (ref "U8F") (pin "8") (pinfunction "GND_8") (pintype "unspecified"))
      (node (ref "U9A") (pin "8") (pinfunction "CS_8") (pintype "unspecified"))
      (node (ref "U9A") (pin "9") (pinfunction "GND_9") (pintype "unspecified"))
      (node (ref "U9B") (pin "8") (pinfunction "GND_8") (pintype "unspecified"))
      (node (ref "U9D") (pin "10") (pinfunction "GND_10") (pintype "unspecified"))
      (node (ref "U9E") (pin "10") (pinfunction "GND_10") (pintype "unspecified"))
      (node (ref "U9F") (pin "10") (pinfunction "GND_10") (pintype "unspecified"))
    )
    (net (code "53") (name "IAK") (class "Default")
      (node (ref "U10C") (pin "8") (pinfunction "3Y_8") (pintype "unspecified"))
      (node (ref "U1B") (pin "5") (pinfunction "3A_5") (pintype "unspecified"))
      (node (ref "U2C") (pin "9") (pinfunction "2C_9") (pintype "unspecified"))
    )
    (net (code "54") (name "INVID") (class "Default")
      (node (ref "RP1") (pin "10") (pinfunction "+5V_10") (pintype "unspecified"))
      (node (ref "U4D") (pin "10") (pinfunction "3B_10") (pintype "unspecified"))
      (node (ref "U8F") (pin "1") (pinfunction "SI_1") (pintype "unspecified"))
      (node (ref "U9E") (pin "15") (pinfunction "2A3_15") (pintype "unspecified"))
    )
    (net (code "55") (name "IOA13") (class "Default")
      (node (ref "U11D") (pin "2") (pinfunction "1Q_2") (pintype "unspecified"))
      (node (ref "U13F") (pin "1") (pinfunction "A_1") (pintype "unspecified"))
    )
    (net (code "56") (name "IOA14") (class "Default")
      (node (ref "U11D") (pin "5") (pinfunction "2Q_5") (pintype "unspecified"))
      (node (ref "U13F") (pin "2") (pinfunction "B_2") (pintype "unspecified"))
    )
    (net (code "57") (name "IOA15") (class "Default")
      (node (ref "U11D") (pin "6") (pinfunction "3Q_6") (pintype "unspecified"))
      (node (ref "U13F") (pin "3") (pinfunction "C_3") (pintype "unspecified"))
    )
    (net (code "58") (name "IOA16") (class "Default")
      (node (ref "RP2") (pin "5") (pinfunction "+5V_5") (pintype "unspecified"))
      (node (ref "U11D") (pin "9") (pinfunction "4Q_9") (pintype "unspecified"))
      (node (ref "U13F") (pin "5") (pinfunction "G2B_5") (pintype "unspecified"))
    )
    (net (code "59") (name "IOCY") (class "Default")
      (node (ref "U2C") (pin "2") (pinfunction "1B_2") (pintype "unspecified"))
      (node (ref "U2C") (pin "8") (pinfunction "2B_8") (pintype "unspecified"))
      (node (ref "U3A") (pin "13") (pinfunction "2K_13") (pintype "unspecified"))
      (node (ref "U3A") (pin "14") (pinfunction "2J_14") (pintype "unspecified"))
      (node (ref "U3A") (pin "15") (pinfunction "2CLR_15") (pintype "unspecified"))
      (node (ref "U4B") (pin "6") (pinfunction "1Q_6") (pintype "unspecified"))
    )
    (net (code "60") (name "MALE") (class "Default")
      (node (ref "U2B") (pin "9") (pinfunction "/2Q_9") (pintype "unspecified"))
      (node (ref "U9D") (pin "11") (pinfunction "LE_11") (pintype "unspecified"))
    )
    (net (code "61") (name "MD0") (class "Default")
      (node (ref "CN1") (pin "73") (pinfunction "MD0_73") (pintype "unspecified"))
      (node (ref "U8F") (pin "2") (pinfunction "A_2") (pintype "unspecified"))
      (node (ref "U9F") (pin "2") (pinfunction "A1_2") (pintype "unspecified"))
    )
    (net (code "62") (name "MD1") (class "Default")
      (node (ref "CN1") (pin "74") (pinfunction "MD1_74") (pintype "unspecified"))
      (node (ref "U8F") (pin "3") (pinfunction "B_3") (pintype "unspecified"))
      (node (ref "U9F") (pin "3") (pinfunction "A2_3") (pintype "unspecified"))
    )
    (net (code "63") (name "MD2") (class "Default")
      (node (ref "CN1") (pin "75") (pinfunction "MD2_75") (pintype "unspecified"))
      (node (ref "U8F") (pin "4") (pinfunction "C_4") (pintype "unspecified"))
      (node (ref "U9F") (pin "4") (pinfunction "A3_4") (pintype "unspecified"))
    )
    (net (code "64") (name "MD3") (class "Default")
      (node (ref "CN1") (pin "76") (pinfunction "MD3_76") (pintype "unspecified"))
      (node (ref "U8F") (pin "5") (pinfunction "D_5") (pintype "unspecified"))
      (node (ref "U9F") (pin "5") (pinfunction "A4_5") (pintype "unspecified"))
    )
    (net (code "65") (name "MD4") (class "Default")
      (node (ref "CN1") (pin "77") (pinfunction "MD4_77") (pintype "unspecified"))
      (node (ref "U8F") (pin "10") (pinfunction "E_10") (pintype "unspecified"))
      (node (ref "U9F") (pin "6") (pinfunction "A5_6") (pintype "unspecified"))
    )
    (net (code "66") (name "MD5") (class "Default")
      (node (ref "CN1") (pin "78") (pinfunction "MD5_78") (pintype "unspecified"))
      (node (ref "U8F") (pin "11") (pinfunction "F_11") (pintype "unspecified"))
      (node (ref "U9F") (pin "7") (pinfunction "A6_7") (pintype "unspecified"))
    )
    (net (code "67") (name "MD6") (class "Default")
      (node (ref "CN1") (pin "79") (pinfunction "MD6_79") (pintype "unspecified"))
      (node (ref "U8F") (pin "12") (pinfunction "G_12") (pintype "unspecified"))
      (node (ref "U9F") (pin "8") (pinfunction "A7_8") (pintype "unspecified"))
    )
    (net (code "68") (name "MD7") (class "Default")
      (node (ref "CN1") (pin "80") (pinfunction "MD7_80") (pintype "unspecified"))
      (node (ref "U8F") (pin "14") (pinfunction "H_14") (pintype "unspecified"))
      (node (ref "U9F") (pin "9") (pinfunction "A8_9") (pintype "unspecified"))
    )
    (net (code "69") (name "MD8") (class "Default")
      (node (ref "CN1") (pin "81") (pinfunction "MD8_81") (pintype "unspecified"))
      (node (ref "U11F") (pin "2") (pinfunction "A1_2") (pintype "unspecified"))
      (node (ref "U7F") (pin "2") (pinfunction "A_2") (pintype "unspecified"))
    )
    (net (code "70") (name "MD9") (class "Default")
      (node (ref "CN1") (pin "82") (pinfunction "MD9_82") (pintype "unspecified"))
      (node (ref "U11F") (pin "3") (pinfunction "A2_3") (pintype "unspecified"))
      (node (ref "U7F") (pin "3") (pinfunction "B_3") (pintype "unspecified"))
    )
    (net (code "71") (name "MD10") (class "Default")
      (node (ref "CN1") (pin "83") (pinfunction "MD10_83") (pintype "unspecified"))
      (node (ref "U11F") (pin "4") (pinfunction "A3_4") (pintype "unspecified"))
      (node (ref "U7F") (pin "4") (pinfunction "C_4") (pintype "unspecified"))
    )
    (net (code "72") (name "MD11") (class "Default")
      (node (ref "CN1") (pin "84") (pinfunction "MD11_84") (pintype "unspecified"))
      (node (ref "U11F") (pin "5") (pinfunction "A4_5") (pintype "unspecified"))
      (node (ref "U7F") (pin "5") (pinfunction "D_5") (pintype "unspecified"))
    )
    (net (code "73") (name "MD12") (class "Default")
      (node (ref "CN1") (pin "85") (pinfunction "MD12_85") (pintype "unspecified"))
      (node (ref "U11F") (pin "6") (pinfunction "A5_6") (pintype "unspecified"))
      (node (ref "U7F") (pin "10") (pinfunction "E_10") (pintype "unspecified"))
    )
    (net (code "74") (name "MD13") (class "Default")
      (node (ref "CN1") (pin "86") (pinfunction "MD13_86") (pintype "unspecified"))
      (node (ref "U11F") (pin "7") (pinfunction "A6_7") (pintype "unspecified"))
      (node (ref "U7F") (pin "11") (pinfunction "F_11") (pintype "unspecified"))
    )
    (net (code "75") (name "MD14") (class "Default")
      (node (ref "CN1") (pin "87") (pinfunction "MD14_87") (pintype "unspecified"))
      (node (ref "U11F") (pin "8") (pinfunction "A7_8") (pintype "unspecified"))
      (node (ref "U7F") (pin "12") (pinfunction "G_12") (pintype "unspecified"))
    )
    (net (code "76") (name "MD15") (class "Default")
      (node (ref "CN1") (pin "88") (pinfunction "MD15_88") (pintype "unspecified"))
      (node (ref "U11F") (pin "9") (pinfunction "A8_9") (pintype "unspecified"))
      (node (ref "U7F") (pin "14") (pinfunction "H_14") (pintype "unspecified"))
    )
    (net (code "77") (name "MMUIO") (class "Default")
      (node (ref "U1A") (pin "4") (pinfunction "A2_4") (pintype "unspecified"))
      (node (ref "U1B") (pin "12") (pinfunction "/6Y_12") (pintype "unspecified"))
      (node (ref "U5D") (pin "11") (pinfunction "2PR_11") (pintype "unspecified"))
      (node (ref "U5D") (pin "5") (pinfunction "1PR_5") (pintype "unspecified"))
      (node (ref "U6D") (pin "12") (pinfunction "4A_12") (pintype "unspecified"))
    )
    (net (code "78") (name "MREAD") (class "Default")
      (node (ref "CN1") (pin "107") (pinfunction "MREAD_107") (pintype "unspecified"))
      (node (ref "U1E") (pin "11") (pinfunction "/4Y_11") (pintype "unspecified"))
    )
    (net (code "79") (name "MS1") (class "Default")
      (node (ref "U10A") (pin "5") (pinfunction "A0_5") (pintype "unspecified"))
      (node (ref "U7C") (pin "6") (pinfunction "/2Y_6") (pintype "unspecified"))
      (node (ref "U8A") (pin "5") (pinfunction "A0_5") (pintype "unspecified"))
      (node (ref "U9A") (pin "5") (pinfunction "A0_5") (pintype "unspecified"))
    )
    (net (code "80") (name "MS2") (class "Default")
      (node (ref "U10A") (pin "4") (pinfunction "A3_4") (pintype "unspecified"))
      (node (ref "U7C") (pin "8") (pinfunction "/3Y_8") (pintype "unspecified"))
      (node (ref "U8A") (pin "4") (pinfunction "A3_4") (pintype "unspecified"))
      (node (ref "U9A") (pin "4") (pinfunction "A3_4") (pintype "unspecified"))
    )
    (net (code "81") (name "Net-(C39-Pad1)") (class "Default")
      (node (ref "C39") (pin "1") (pinfunction "1_1") (pintype "unspecified"))
      (node (ref "Q1") (pin "2") (pinfunction "2_2") (pintype "unspecified"))
      (node (ref "R15") (pin "2") (pinfunction "2_2") (pintype "unspecified"))
      (node (ref "R16") (pin "2") (pinfunction "2_2") (pintype "unspecified"))
      (node (ref "R17") (pin "1") (pinfunction "1_1") (pintype "unspecified"))
    )
    (net (code "82") (name "Net-(L1-Pad1)") (class "Default")
      (node (ref "L1") (pin "1") (pinfunction "1_1") (pintype "unspecified"))
      (node (ref "Q1") (pin "3") (pinfunction "3_3") (pintype "unspecified"))
      (node (ref "Y1") (pin "2") (pinfunction "2_2") (pintype "unspecified"))
    )
    (net (code "83") (name "Net-(Q1-Pad1)") (class "Default")
      (node (ref "Q1") (pin "1") (pinfunction "1_1") (pintype "unspecified"))
      (node (ref "Q2") (pin "1") (pinfunction "1_1") (pintype "unspecified"))
      (node (ref "R14") (pin "1") (pinfunction "1_1") (pintype "unspecified"))
    )
    (net (code "84") (name "Net-(Q2-Pad2)") (class "Default")
      (node (ref "Q2") (pin "2") (pinfunction "2_2") (pintype "unspecified"))
      (node (ref "R15") (pin "1") (pinfunction "1_1") (pintype "unspecified"))
      (node (ref "Y1") (pin "1") (pinfunction "1_1") (pintype "unspecified"))
    )
    (net (code "85") (name "Net-(U1A-A3)") (class "Default")
      (node (ref "U1A") (pin "10") (pinfunction "B3_10") (pintype "unspecified"))
      (node (ref "U1A") (pin "11") (pinfunction "Y4_11") (pintype "unspecified"))
      (node (ref "U1A") (pin "9") (pinfunction "A3_9") (pintype "unspecified"))
    )
    (net (code "86") (name "Net-(U1A-A4)") (class "Default")
      (node (ref "U1A") (pin "12") (pinfunction "A4_12") (pintype "unspecified"))
      (node (ref "U1A") (pin "13") (pinfunction "B4_13") (pintype "unspecified"))
      (node (ref "U1A") (pin "8") (pinfunction "Y3_8") (pintype "unspecified"))
    )
    (net (code "87") (name "Net-(U1A-Y2)") (class "Default")
      (node (ref "U1A") (pin "6") (pinfunction "Y2_6") (pintype "unspecified"))
      (node (ref "U5B") (pin "11") (pinfunction "4A_11") (pintype "unspecified"))
    )
    (net (code "88") (name "Net-(U1B-{slash}3Y)") (class "Default")
      (node (ref "U1B") (pin "6") (pinfunction "/3Y_6") (pintype "unspecified"))
      (node (ref "U2D") (pin "12") (pinfunction "A4_12") (pintype "unspecified"))
    )
    (net (code "89") (name "Net-(U1C-QA)") (class "Default")
      (node (ref "U1C") (pin "14") (pinfunction "QA_14") (pintype "unspecified"))
      (node (ref "U1D") (pin "1") (pinfunction "A_1") (pintype "unspecified"))
    )
    (net (code "90") (name "Net-(U1C-QC)") (class "Default")
      (node (ref "U1C") (pin "12") (pinfunction "QC_12") (pintype "unspecified"))
      (node (ref "U1D") (pin "3") (pinfunction "C_3") (pintype "unspecified"))
    )
    (net (code "91") (name "Net-(U1C-RP0)") (class "Default")
      (node (ref "U1C") (pin "15") (pinfunction "RP0_15") (pintype "unspecified"))
      (node (ref "U2C") (pin "10") (pinfunction "2D_10") (pintype "unspecified"))
    )
    (net (code "92") (name "Net-(U1E-2A)") (class "Default")
      (node (ref "U1E") (pin "10") (pinfunction "3B_10") (pintype "unspecified"))
      (node (ref "U1E") (pin "3") (pinfunction "/1Y_3") (pintype "unspecified"))
      (node (ref "U1E") (pin "4") (pinfunction "2A_4") (pintype "unspecified"))
    )
    (net (code "93") (name "Net-(U2B-1J)") (class "Default")
      (node (ref "U2B") (pin "14") (pinfunction "2J_14") (pintype "unspecified"))
      (node (ref "U2B") (pin "2") (pinfunction "1J_2") (pintype "unspecified"))
      (node (ref "U2C") (pin "6") (pinfunction "2Y_6") (pintype "unspecified"))
    )
    (net (code "94") (name "Net-(U2C-1Y)") (class "Default")
      (node (ref "U2C") (pin "5") (pinfunction "1Y_5") (pintype "unspecified"))
      (node (ref "U3B") (pin "14") (pinfunction "2J_14") (pintype "unspecified"))
    )
    (net (code "95") (name "Net-(U2C-2E)") (class "Default")
      (node (ref "U2C") (pin "11") (pinfunction "2E_11") (pintype "unspecified"))
      (node (ref "U3B") (pin "10") (pinfunction "2Q_10") (pintype "unspecified"))
    )
    (net (code "96") (name "Net-(U2D-Y4)") (class "Default")
      (node (ref "U2D") (pin "11") (pinfunction "Y4_11") (pintype "unspecified"))
      (node (ref "U4F") (pin "14") (pinfunction "2G_14") (pintype "unspecified"))
      (node (ref "U4F") (pin "2") (pinfunction "1G_2") (pintype "unspecified"))
    )
    (net (code "97") (name "Net-(U3B-1J)") (class "Default")
      (node (ref "U3B") (pin "2") (pinfunction "1J_2") (pintype "unspecified"))
      (node (ref "U3D") (pin "6") (pinfunction "2Y_6") (pintype "unspecified"))
    )
    (net (code "98") (name "Net-(U3D-1Y)") (class "Default")
      (node (ref "U3D") (pin "5") (pinfunction "1Y_5") (pintype "unspecified"))
      (node (ref "U4B") (pin "2") (pinfunction "1J_2") (pintype "unspecified"))
    )
    (net (code "99") (name "Net-(U3E-1PR)") (class "Default")
      (node (ref "U3E") (pin "5") (pinfunction "1PR_5") (pintype "unspecified"))
      (node (ref "U4A") (pin "11") (pinfunction "4Y_11") (pintype "unspecified"))
    )
    (net (code "100") (name "Net-(U3E-1Q)") (class "Default")
      (node (ref "U3E") (pin "6") (pinfunction "1Q_6") (pintype "unspecified"))
      (node (ref "U6F") (pin "1") (pinfunction "1ACLK_1") (pintype "unspecified"))
      (node (ref "U7F") (pin "15") (pinfunction "LD_15") (pintype "unspecified"))
      (node (ref "U8F") (pin "15") (pinfunction "LD_15") (pintype "unspecified"))
    )
    (net (code "101") (name "Net-(U3E-2J)") (class "Default")
      (node (ref "U3E") (pin "13") (pinfunction "2K_13") (pintype "unspecified"))
      (node (ref "U3E") (pin "14") (pinfunction "2J_14") (pintype "unspecified"))
      (node (ref "U7F") (pin "13") (pinfunction "SO_13") (pintype "unspecified"))
    )
    (net (code "102") (name "Net-(U3E-2Q)") (class "Default")
      (node (ref "U3E") (pin "10") (pinfunction "2Q_10") (pintype "unspecified"))
      (node (ref "U4D") (pin "9") (pinfunction "3A_9") (pintype "unspecified"))
    )
    (net (code "103") (name "Net-(U4A-1B)") (class "Default")
      (node (ref "U4A") (pin "2") (pinfunction "1B_2") (pintype "unspecified"))
      (node (ref "U6C") (pin "9") (pinfunction "D3_9") (pintype "unspecified"))
    )
    (net (code "104") (name "Net-(U4A-1Y)") (class "Default")
      (node (ref "U4A") (pin "3") (pinfunction "1Y_3") (pintype "unspecified"))
      (node (ref "U6B") (pin "8") (pinfunction "4D_8") (pintype "unspecified"))
    )
    (net (code "105") (name "Net-(U4A-2B)") (class "Default")
      (node (ref "U4A") (pin "5") (pinfunction "2B_5") (pintype "unspecified"))
      (node (ref "U6B") (pin "9") (pinfunction "4Q_9") (pintype "unspecified"))
    )
    (net (code "106") (name "Net-(U4A-2Y)") (class "Default")
      (node (ref "U4A") (pin "6") (pinfunction "2Y_6") (pintype "unspecified"))
      (node (ref "U5E") (pin "12") (pinfunction "2CLR_12") (pintype "unspecified"))
      (node (ref "U5E") (pin "2") (pinfunction "1CLR_2") (pintype "unspecified"))
      (node (ref "U6F") (pin "12") (pinfunction "2CLR_12") (pintype "unspecified"))
      (node (ref "U6F") (pin "2") (pinfunction "1CLR_2") (pintype "unspecified"))
    )
    (net (code "107") (name "Net-(U4A-4B)") (class "Default")
      (node (ref "U4A") (pin "13") (pinfunction "4B_13") (pintype "unspecified"))
      (node (ref "U6B") (pin "6") (pinfunction "3Q_6") (pintype "unspecified"))
    )
    (net (code "108") (name "Net-(U4D-4Y)") (class "Default")
      (node (ref "R10") (pin "2") (pinfunction "2_2") (pintype "unspecified"))
      (node (ref "U4D") (pin "11") (pinfunction "4Y_11") (pintype "unspecified"))
    )
    (net (code "109") (name "Net-(U5A-1Y)") (class "Default")
      (node (ref "U5A") (pin "12") (pinfunction "1Y_12") (pintype "unspecified"))
      (node (ref "U5A") (pin "5") (pinfunction "2C_5") (pintype "unspecified"))
    )
    (net (code "110") (name "Net-(U5B-3Y)") (class "Default")
      (node (ref "U5B") (pin "10") (pinfunction "3Y_10") (pintype "unspecified"))
      (node (ref "U8B") (pin "7") (pinfunction "C0_7") (pintype "unspecified"))
    )
    (net (code "111") (name "Net-(U5C-1R)") (class "Default")
      (node (ref "C19") (pin "2") (pinfunction "2_2") (pintype "unspecified"))
      (node (ref "R4") (pin "2") (pinfunction "2_2") (pintype "unspecified"))
      (node (ref "R5") (pin "2") (pinfunction "2_2") (pintype "unspecified"))
      (node (ref "U5C") (pin "1") (pinfunction "1R_1") (pintype "unspecified"))
    )
    (net (code "112") (name "Net-(U5C-3R)") (class "Default")
      (node (ref "C21") (pin "2") (pinfunction "2_2") (pintype "unspecified"))
      (node (ref "R6") (pin "2") (pinfunction "2_2") (pintype "unspecified"))
      (node (ref "R7") (pin "2") (pinfunction "2_2") (pintype "unspecified"))
      (node (ref "U5C") (pin "10") (pinfunction "3R_10") (pintype "unspecified"))
    )
    (net (code "113") (name "Net-(U5C-4Q)") (class "Default")
      (node (ref "U5C") (pin "13") (pinfunction "4Q_13") (pintype "unspecified"))
      (node (ref "U9E") (pin "8") (pinfunction "1A4_8") (pintype "unspecified"))
    )
    (net (code "114") (name "Net-(U6B-1D)") (class "Default")
      (node (ref "U6B") (pin "3") (pinfunction "1D_3") (pintype "unspecified"))
      (node (ref "U6C") (pin "6") (pinfunction "D0_6") (pintype "unspecified"))
    )
    (net (code "115") (name "Net-(U6B-1Q)") (class "Default")
      (node (ref "U6B") (pin "2") (pinfunction "1Q_2") (pintype "unspecified"))
      (node (ref "U7B") (pin "12") (pinfunction "2CLR_12") (pintype "unspecified"))
      (node (ref "U7B") (pin "2") (pinfunction "1CLR_2") (pintype "unspecified"))
    )
    (net (code "116") (name "Net-(U6B-2D)") (class "Default")
      (node (ref "U6B") (pin "4") (pinfunction "2D_4") (pintype "unspecified"))
      (node (ref "U6C") (pin "7") (pinfunction "D1_7") (pintype "unspecified"))
    )
    (net (code "117") (name "Net-(U6B-3D)") (class "Default")
      (node (ref "U6B") (pin "7") (pinfunction "3D_7") (pintype "unspecified"))
      (node (ref "U6C") (pin "8") (pinfunction "D2_8") (pintype "unspecified"))
    )
    (net (code "118") (name "Net-(U6B-5D)") (class "Default")
      (node (ref "U6B") (pin "13") (pinfunction "5D_13") (pintype "unspecified"))
      (node (ref "U6C") (pin "11") (pinfunction "D4_11") (pintype "unspecified"))
    )
    (net (code "119") (name "Net-(U6B-6D)") (class "Default")
      (node (ref "U6B") (pin "14") (pinfunction "6D_14") (pintype "unspecified"))
      (node (ref "U6C") (pin "12") (pinfunction "D5_12") (pintype "unspecified"))
    )
    (net (code "120") (name "Net-(U6B-7D)") (class "Default")
      (node (ref "U6B") (pin "17") (pinfunction "7D_17") (pintype "unspecified"))
      (node (ref "U6B") (pin "18") (pinfunction "8D_18") (pintype "unspecified"))
      (node (ref "U6C") (pin "13") (pinfunction "D6_13") (pintype "unspecified"))
    )
    (net (code "121") (name "Net-(U6C-A0)") (class "Default")
      (node (ref "U6C") (pin "1") (pinfunction "A0_1") (pintype "unspecified"))
      (node (ref "U7B") (pin "3") (pinfunction "1QA_3") (pintype "unspecified"))
    )
    (net (code "122") (name "Net-(U6C-A1)") (class "Default")
      (node (ref "U6C") (pin "2") (pinfunction "A1_2") (pintype "unspecified"))
      (node (ref "U7B") (pin "4") (pinfunction "1QB_4") (pintype "unspecified"))
    )
    (net (code "123") (name "Net-(U6C-A2)") (class "Default")
      (node (ref "U6C") (pin "3") (pinfunction "A2_3") (pintype "unspecified"))
      (node (ref "U7B") (pin "5") (pinfunction "1QC_5") (pintype "unspecified"))
    )
    (net (code "124") (name "Net-(U6C-A3)") (class "Default")
      (node (ref "U6C") (pin "4") (pinfunction "A3_4") (pintype "unspecified"))
      (node (ref "U7B") (pin "13") (pinfunction "2ACLK_13") (pintype "unspecified"))
      (node (ref "U7B") (pin "6") (pinfunction "1QD_6") (pintype "unspecified"))
    )
    (net (code "125") (name "Net-(U6C-A4)") (class "Default")
      (node (ref "U6C") (pin "5") (pinfunction "A4_5") (pintype "unspecified"))
      (node (ref "U7B") (pin "11") (pinfunction "2QA_11") (pintype "unspecified"))
    )
    (net (code "126") (name "Net-(U6C-A5)") (class "Default")
      (node (ref "U6C") (pin "17") (pinfunction "A5_17") (pintype "unspecified"))
      (node (ref "U7B") (pin "10") (pinfunction "2QB_10") (pintype "unspecified"))
    )
    (net (code "127") (name "Net-(U6D-3B)") (class "Default")
      (node (ref "U6D") (pin "10") (pinfunction "3B_10") (pintype "unspecified"))
      (node (ref "U6D") (pin "11") (pinfunction "/4Y_11") (pintype "unspecified"))
    )
    (net (code "128") (name "Net-(U6D-{slash}2Y)") (class "Default")
      (node (ref "U6D") (pin "6") (pinfunction "/2Y_6") (pintype "unspecified"))
      (node (ref "U7D") (pin "1") (pinfunction "/OE_1") (pintype "unspecified"))
    )
    (net (code "129") (name "Net-(U7C-2A)") (class "Default")
      (node (ref "U7C") (pin "10") (pinfunction "3B_10") (pintype "unspecified"))
      (node (ref "U7C") (pin "3") (pinfunction "/1Y_3") (pintype "unspecified"))
      (node (ref "U7C") (pin "4") (pinfunction "2A_4") (pintype "unspecified"))
    )
    (net (code "130") (name "Net-(U7F-SI)") (class "Default")
      (node (ref "U7F") (pin "1") (pinfunction "SI_1") (pintype "unspecified"))
      (node (ref "U8F") (pin "13") (pinfunction "SO_13") (pintype "unspecified"))
    )
    (net (code "131") (name "Net-(U8B-C4)") (class "Default")
      (node (ref "U8B") (pin "9") (pinfunction "C4_9") (pintype "unspecified"))
      (node (ref "U9B") (pin "7") (pinfunction "C0_7") (pintype "unspecified"))
    )
    (net (code "132") (name "Net-(U10A-CS)") (class "Default")
      (node (ref "U10A") (pin "8") (pinfunction "CS_8") (pintype "unspecified"))
      (node (ref "U5B") (pin "13") (pinfunction "4Y_13") (pintype "unspecified"))
    )
    (net (code "133") (name "Net-(U10A-WE)") (class "Default")
      (node (ref "U10A") (pin "10") (pinfunction "WE_10") (pintype "unspecified"))
      (node (ref "U5D") (pin "10") (pinfunction "2Q_10") (pintype "unspecified"))
      (node (ref "U8A") (pin "10") (pinfunction "WE_10") (pintype "unspecified"))
      (node (ref "U9A") (pin "10") (pinfunction "WE_10") (pintype "unspecified"))
    )
    (net (code "134") (name "Net-(U10B-S1)") (class "Default")
      (node (ref "U10B") (pin "4") (pinfunction "S1_4") (pintype "unspecified"))
      (node (ref "U9D") (pin "13") (pinfunction "5D_13") (pintype "unspecified"))
    )
    (net (code "135") (name "Net-(U10B-S2)") (class "Default")
      (node (ref "U10B") (pin "1") (pinfunction "S2_1") (pintype "unspecified"))
      (node (ref "U9D") (pin "14") (pinfunction "6D_14") (pintype "unspecified"))
    )
    (net (code "136") (name "Net-(U10B-S3)") (class "Default")
      (node (ref "U10B") (pin "13") (pinfunction "S3_13") (pintype "unspecified"))
      (node (ref "U9D") (pin "17") (pinfunction "7D_17") (pintype "unspecified"))
    )
    (net (code "137") (name "Net-(U10B-S4)") (class "Default")
      (node (ref "U10B") (pin "10") (pinfunction "S4_10") (pintype "unspecified"))
      (node (ref "U9D") (pin "18") (pinfunction "8D_18") (pintype "unspecified"))
    )
    (net (code "138") (name "Net-(U10C-1A)") (class "Default")
      (node (ref "U10C") (pin "1") (pinfunction "1A_1") (pintype "unspecified"))
      (node (ref "U10C") (pin "4") (pinfunction "2B_4") (pintype "unspecified"))
      (node (ref "U5C") (pin "9") (pinfunction "3Q_9") (pintype "unspecified"))
      (node (ref "U9E") (pin "4") (pinfunction "1A2_4") (pintype "unspecified"))
    )
    (net (code "139") (name "Net-(U10C-1B)") (class "Default")
      (node (ref "U10C") (pin "2") (pinfunction "1B_2") (pintype "unspecified"))
      (node (ref "U10C") (pin "5") (pinfunction "2C_5") (pintype "unspecified"))
      (node (ref "U5C") (pin "4") (pinfunction "1Q_4") (pintype "unspecified"))
      (node (ref "U9E") (pin "2") (pinfunction "1A1_2") (pintype "unspecified"))
    )
    (net (code "140") (name "Net-(U10C-2Y)") (class "Default")
      (node (ref "U10C") (pin "6") (pinfunction "2Y_6") (pintype "unspecified"))
      (node (ref "U11E") (pin "11") (pinfunction "G_11") (pintype "unspecified"))
      (node (ref "U13E") (pin "11") (pinfunction "G_11") (pintype "unspecified"))
    )
    (net (code "141") (name "Net-(U10C-3A)") (class "Default")
      (node (ref "U10C") (pin "9") (pinfunction "3A_9") (pintype "unspecified"))
      (node (ref "U13A") (pin "27") (pinfunction "FC1_27") (pintype "unspecified"))
    )
    (net (code "142") (name "Net-(U10C-3B)") (class "Default")
      (node (ref "R9") (pin "2") (pinfunction "2_2") (pintype "unspecified"))
      (node (ref "U10C") (pin "10") (pinfunction "3B_10") (pintype "unspecified"))
      (node (ref "U13A") (pin "28") (pinfunction "FC0_28") (pintype "unspecified"))
    )
    (net (code "143") (name "Net-(U11A-A8)") (class "Default")
      (node (ref "R8") (pin "2") (pinfunction "2_2") (pintype "unspecified"))
      (node (ref "U11A") (pin "9") (pinfunction "A8_9") (pintype "unspecified"))
    )
    (net (code "144") (name "Net-(U11A-G)") (class "Default")
      (node (ref "U11A") (pin "19") (pinfunction "G_19") (pintype "unspecified"))
      (node (ref "U11B") (pin "19") (pinfunction "G_19") (pintype "unspecified"))
      (node (ref "U5D") (pin "6") (pinfunction "1Q_6") (pintype "unspecified"))
    )
    (net (code "145") (name "Net-(U11C-G)") (class "Default")
      (node (ref "U11C") (pin "11") (pinfunction "G_11") (pintype "unspecified"))
      (node (ref "U15F") (pin "11") (pinfunction "/4Y_11") (pintype "unspecified"))
    )
    (net (code "146") (name "Net-(U11D-1D)") (class "Default")
      (node (ref "U11D") (pin "3") (pinfunction "1D_3") (pintype "unspecified"))
      (node (ref "U9B") (pin "4") (pinfunction "S1_4") (pintype "unspecified"))
      (node (ref "U9D") (pin "3") (pinfunction "1D_3") (pintype "unspecified"))
    )
    (net (code "147") (name "Net-(U11D-2D)") (class "Default")
      (node (ref "U11D") (pin "4") (pinfunction "2D_4") (pintype "unspecified"))
      (node (ref "U9B") (pin "1") (pinfunction "S2_1") (pintype "unspecified"))
      (node (ref "U9D") (pin "4") (pinfunction "2D_4") (pintype "unspecified"))
    )
    (net (code "148") (name "Net-(U11D-3D)") (class "Default")
      (node (ref "U11D") (pin "7") (pinfunction "3D_7") (pintype "unspecified"))
      (node (ref "U9B") (pin "13") (pinfunction "S3_13") (pintype "unspecified"))
      (node (ref "U9D") (pin "7") (pinfunction "3D_7") (pintype "unspecified"))
    )
    (net (code "149") (name "Net-(U11D-4D)") (class "Default")
      (node (ref "U11D") (pin "8") (pinfunction "4D_8") (pintype "unspecified"))
      (node (ref "U9B") (pin "10") (pinfunction "S4_10") (pintype "unspecified"))
      (node (ref "U9D") (pin "8") (pinfunction "4D_8") (pintype "unspecified"))
    )
    (net (code "150") (name "Net-(U11D-5D)") (class "Default")
      (node (ref "U11D") (pin "13") (pinfunction "5D_13") (pintype "unspecified"))
      (node (ref "U8B") (pin "4") (pinfunction "S1_4") (pintype "unspecified"))
    )
    (net (code "151") (name "Net-(U11D-6D)") (class "Default")
      (node (ref "U11D") (pin "14") (pinfunction "6D_14") (pintype "unspecified"))
      (node (ref "U8B") (pin "1") (pinfunction "S2_1") (pintype "unspecified"))
    )
    (net (code "152") (name "Net-(U11D-7D)") (class "Default")
      (node (ref "U11D") (pin "17") (pinfunction "7D_17") (pintype "unspecified"))
      (node (ref "U8B") (pin "13") (pinfunction "S3_13") (pintype "unspecified"))
    )
    (net (code "153") (name "Net-(U11D-8D)") (class "Default")
      (node (ref "U11D") (pin "18") (pinfunction "8D_18") (pintype "unspecified"))
      (node (ref "U8B") (pin "10") (pinfunction "S4_10") (pintype "unspecified"))
    )
    (net (code "154") (name "Net-(U12F-A0)") (class "Default")
      (node (ref "U12F") (pin "9") (pinfunction "A0_9") (pintype "unspecified"))
      (node (ref "U13A") (pin "25") (pinfunction "IPL0_25") (pintype "unspecified"))
    )
    (net (code "155") (name "Net-(U12F-A1)") (class "Default")
      (node (ref "U12F") (pin "7") (pinfunction "A1_7") (pintype "unspecified"))
      (node (ref "U13A") (pin "24") (pinfunction "IPL1_24") (pintype "unspecified"))
    )
    (net (code "156") (name "Net-(U12F-A2)") (class "Default")
      (node (ref "U12F") (pin "6") (pinfunction "A2_6") (pintype "unspecified"))
      (node (ref "U13A") (pin "23") (pinfunction "IPL2_23") (pintype "unspecified"))
    )
    (net (code "157") (name "Net-(U13A-E)") (class "Default")
      (node (ref "U13A") (pin "20") (pinfunction "E_20") (pintype "unspecified"))
      (node (ref "U8C") (pin "6") (pinfunction "1A3_6") (pintype "unspecified"))
    )
    (net (code "158") (name "Net-(U13A-LDS)") (class "Default")
      (node (ref "U13A") (pin "8") (pinfunction "LDS_8") (pintype "unspecified"))
      (node (ref "U8C") (pin "15") (pinfunction "2A3_15") (pintype "unspecified"))
    )
    (net (code "159") (name "Net-(U13A-READ)") (class "Default")
      (node (ref "U13A") (pin "9") (pinfunction "READ_9") (pintype "unspecified"))
      (node (ref "U8C") (pin "11") (pinfunction "2A1_11") (pintype "unspecified"))
    )
    (net (code "160") (name "Net-(U13A-RESET)") (class "Default")
      (node (ref "RP2") (pin "11") (pinfunction "+5V_11") (pintype "unspecified"))
      (node (ref "U13A") (pin "18") (pinfunction "RESET_18") (pintype "unspecified"))
      (node (ref "U2E") (pin "2") (pinfunction "1Y_2") (pintype "unspecified"))
      (node (ref "U2E") (pin "3") (pinfunction "2A_3") (pintype "unspecified"))
    )
    (net (code "161") (name "Net-(U13A-UDS)") (class "Default")
      (node (ref "U13A") (pin "7") (pinfunction "UDS_7") (pintype "unspecified"))
      (node (ref "U8C") (pin "17") (pinfunction "2A4_17") (pintype "unspecified"))
    )
    (net (code "162") (name "Net-(U13A-VMA)") (class "Default")
      (node (ref "U13A") (pin "19") (pinfunction "VMA_19") (pintype "unspecified"))
      (node (ref "U8C") (pin "8") (pinfunction "1A4_8") (pintype "unspecified"))
    )
    (net (code "163") (name "Net-(U13F-G1)") (class "Default")
      (node (ref "U13F") (pin "6") (pinfunction "G1_6") (pintype "unspecified"))
      (node (ref "U3A") (pin "10") (pinfunction "2Q_10") (pintype "unspecified"))
    )
    (net (code "164") (name "Net-(U14F-2Y0)") (class "Default")
      (node (ref "U14F") (pin "12") (pinfunction "2Y0_12") (pintype "unspecified"))
      (node (ref "U4E") (pin "14") (pinfunction "G_14") (pintype "unspecified"))
    )
    (net (code "165") (name "Net-(U15B-Q1)") (class "Default")
      (node (ref "U15B") (pin "5") (pinfunction "Q1_5") (pintype "unspecified"))
      (node (ref "U7A") (pin "1") (pinfunction "1A_1") (pintype "unspecified"))
      (node (ref "U7A") (pin "2") (pinfunction "1B_2") (pintype "unspecified"))
    )
    (net (code "166") (name "Net-(U15B-TH2)") (class "Default")
      (node (ref "C9") (pin "1") (pinfunction "1_1") (pintype "unspecified"))
      (node (ref "R3") (pin "1") (pinfunction "1_1") (pintype "unspecified"))
      (node (ref "U15B") (pin "12") (pinfunction "TH2_12") (pintype "unspecified"))
      (node (ref "U15B") (pin "8") (pinfunction "TR2_8") (pintype "unspecified"))
      (node (ref "U2E") (pin "12") (pinfunction "6Y_12") (pintype "unspecified"))
    )
    (net (code "167") (name "Net-(U15F-{slash}3Y)") (class "Default")
      (node (ref "U15F") (pin "8") (pinfunction "/3Y_8") (pintype "unspecified"))
      (node (ref "U9D") (pin "1") (pinfunction "OE_1") (pintype "unspecified"))
    )
    (net (code "168") (name "PCK") (class "Default")
      (node (ref "U13A") (pin "15") (pinfunction "PCK_15") (pintype "unspecified"))
      (node (ref "U1C") (pin "13") (pinfunction "QB_13") (pintype "unspecified"))
      (node (ref "U1D") (pin "2") (pinfunction "B_2") (pintype "unspecified"))
      (node (ref "U4D") (pin "13") (pinfunction "4B_13") (pintype "unspecified"))
      (node (ref "U5D") (pin "14") (pinfunction "2J_14") (pintype "unspecified"))
    )
    (net (code "169") (name "R1") (class "Default")
      (node (ref "CN1") (pin "71") (pinfunction "R1_71") (pintype "unspecified"))
      (node (ref "U15F") (pin "3") (pinfunction "/1Y_3") (pintype "unspecified"))
    )
    (net (code "170") (name "R2") (class "Default")
      (node (ref "CN1") (pin "72") (pinfunction "R2_72") (pintype "unspecified"))
      (node (ref "U2D") (pin "8") (pinfunction "Y3_8") (pintype "unspecified"))
    )
    (net (code "171") (name "RA1") (class "Default")
      (node (ref "CN1") (pin "93") (pinfunction "RA1_93") (pintype "unspecified"))
      (node (ref "U7E") (pin "7") (pinfunction "1Y_7") (pintype "unspecified"))
    )
    (net (code "172") (name "RA2") (class "Default")
      (node (ref "CN1") (pin "94") (pinfunction "RA2_94") (pintype "unspecified"))
      (node (ref "U7E") (pin "9") (pinfunction "2Y_9") (pintype "unspecified"))
    )
    (net (code "173") (name "RA3") (class "Default")
      (node (ref "CN1") (pin "95") (pinfunction "RA3_95") (pintype "unspecified"))
      (node (ref "U6E") (pin "7") (pinfunction "1Y_7") (pintype "unspecified"))
    )
    (net (code "174") (name "RA4") (class "Default")
      (node (ref "CN1") (pin "96") (pinfunction "RA4_96") (pintype "unspecified"))
      (node (ref "U6E") (pin "9") (pinfunction "2Y_9") (pintype "unspecified"))
    )
    (net (code "175") (name "RA5") (class "Default")
      (node (ref "CN1") (pin "97") (pinfunction "RA5_97") (pintype "unspecified"))
      (node (ref "U5F") (pin "7") (pinfunction "1Y_7") (pintype "unspecified"))
    )
    (net (code "176") (name "RA6") (class "Default")
      (node (ref "CN1") (pin "98") (pinfunction "RA6_98") (pintype "unspecified"))
      (node (ref "U5F") (pin "9") (pinfunction "2Y_9") (pintype "unspecified"))
    )
    (net (code "177") (name "RA7") (class "Default")
      (node (ref "CN1") (pin "99") (pinfunction "RA7_99") (pintype "unspecified"))
      (node (ref "U8E") (pin "7") (pinfunction "1Y_7") (pintype "unspecified"))
    )
    (net (code "178") (name "RA8") (class "Default")
      (node (ref "CN1") (pin "100") (pinfunction "RA8_100") (pintype "unspecified"))
      (node (ref "U8E") (pin "9") (pinfunction "2Y_9") (pintype "unspecified"))
    )
    (net (code "179") (name "RAS") (class "Default")
      (node (ref "U3C") (pin "7") (pinfunction "/1Q_7") (pintype "unspecified"))
      (node (ref "U5F") (pin "2") (pinfunction "B_2") (pintype "unspecified"))
      (node (ref "U6E") (pin "2") (pinfunction "B_2") (pintype "unspecified"))
      (node (ref "U7E") (pin "2") (pinfunction "B_2") (pintype "unspecified"))
      (node (ref "U8E") (pin "2") (pinfunction "B_2") (pintype "unspecified"))
    )
    (net (code "180") (name "READ") (class "Default")
      (node (ref "CN1") (pin "64") (pinfunction "READ_64") (pintype "unspecified"))
      (node (ref "RP2") (pin "15") (pinfunction "+5V_15") (pintype "unspecified"))
      (node (ref "U11A") (pin "1") (pinfunction "A+B_1") (pintype "unspecified"))
      (node (ref "U11B") (pin "1") (pinfunction "A+B_1") (pintype "unspecified"))
      (node (ref "U11F") (pin "1") (pinfunction "A-B_1") (pintype "unspecified"))
      (node (ref "U14E") (pin "1") (pinfunction "A-B_1") (pintype "unspecified"))
      (node (ref "U15E") (pin "1") (pinfunction "A-B_1") (pintype "unspecified"))
      (node (ref "U2D") (pin "1") (pinfunction "A1_1") (pintype "unspecified"))
      (node (ref "U2D") (pin "5") (pinfunction "B2_5") (pintype "unspecified"))
      (node (ref "U5B") (pin "6") (pinfunction "2B_6") (pintype "unspecified"))
      (node (ref "U8C") (pin "9") (pinfunction "2Y1_9") (pintype "unspecified"))
      (node (ref "U9F") (pin "1") (pinfunction "A-B_1") (pintype "unspecified"))
    )
    (net (code "181") (name "RP1_2") (class "Default")
      (node (ref "RP1") (pin "2") (pinfunction "+5V_2") (pintype "unspecified"))
      (node (ref "U1C") (pin "9") (pinfunction "LD_9") (pintype "unspecified"))
    )
    (net (code "182") (name "RP1_3") (class "Default")
      (node (ref "RP1") (pin "3") (pinfunction "+5V_3") (pintype "unspecified"))
      (node (ref "U9E") (pin "17") (pinfunction "2A4_17") (pintype "unspecified"))
    )
    (net (code "183") (name "RP1_4") (class "Default")
      (node (ref "CN1") (pin "24") (pinfunction "/BGACK_24") (pintype "unspecified"))
      (node (ref "RP1") (pin "4") (pinfunction "+5V_4") (pintype "unspecified"))
      (node (ref "U13A") (pin "12") (pinfunction "BGACK_12") (pintype "unspecified"))
      (node (ref "U15F") (pin "5") (pinfunction "2B_5") (pintype "unspecified"))
      (node (ref "U15F") (pin "9") (pinfunction "3A_9") (pintype "unspecified"))
      (node (ref "U6A") (pin "11") (pinfunction "4A_11") (pintype "unspecified"))
      (node (ref "U6A") (pin "12") (pinfunction "4B_12") (pintype "unspecified"))
    )
    (net (code "184") (name "RP1_5") (class "Default")
      (node (ref "RP1") (pin "5") (pinfunction "+5V_5") (pintype "unspecified"))
      (node (ref "U2B") (pin "1") (pinfunction "1CLR_1") (pintype "unspecified"))
      (node (ref "U2B") (pin "11") (pinfunction "2PR_11") (pintype "unspecified"))
      (node (ref "U2B") (pin "13") (pinfunction "2K_13") (pintype "unspecified"))
      (node (ref "U2B") (pin "5") (pinfunction "1PR_5") (pintype "unspecified"))
      (node (ref "U3A") (pin "11") (pinfunction "2PR_11") (pintype "unspecified"))
      (node (ref "U3B") (pin "13") (pinfunction "2K_13") (pintype "unspecified"))
      (node (ref "U3B") (pin "3") (pinfunction "1K_3") (pintype "unspecified"))
      (node (ref "U3B") (pin "5") (pinfunction "1PR_5") (pintype "unspecified"))
      (node (ref "U3C") (pin "1") (pinfunction "1CLR_1") (pintype "unspecified"))
      (node (ref "U3C") (pin "15") (pinfunction "2CLR_15") (pintype "unspecified"))
      (node (ref "U4B") (pin "11") (pinfunction "2PR_11") (pintype "unspecified"))
      (node (ref "U4B") (pin "15") (pinfunction "2CLR_15") (pintype "unspecified"))
      (node (ref "U4B") (pin "3") (pinfunction "1K_3") (pintype "unspecified"))
      (node (ref "U4B") (pin "5") (pinfunction "1PR_5") (pintype "unspecified"))
      (node (ref "U5D") (pin "1") (pinfunction "1CLR_1") (pintype "unspecified"))
      (node (ref "U5D") (pin "15") (pinfunction "2CLR_15") (pintype "unspecified"))
    )
    (net (code "185") (name "RP1_6") (class "Default")
      (node (ref "RP1") (pin "6") (pinfunction "+5V_6") (pintype "unspecified"))
      (node (ref "U1E") (pin "1") (pinfunction "1A_1") (pintype "unspecified"))
    )
    (net (code "186") (name "RP1_7") (class "Default")
      (node (ref "CN1") (pin "63") (pinfunction "/AS_63") (pintype "unspecified"))
      (node (ref "RP1") (pin "7") (pinfunction "+5V_7") (pintype "unspecified"))
      (node (ref "U2C") (pin "4") (pinfunction "2A_4") (pintype "unspecified"))
      (node (ref "U6A") (pin "2") (pinfunction "1A_2") (pintype "unspecified"))
      (node (ref "U6A") (pin "3") (pinfunction "1B_3") (pintype "unspecified"))
      (node (ref "U8C") (pin "7") (pinfunction "2Y2_7") (pintype "unspecified"))
    )
    (net (code "187") (name "RP1_8") (class "Default")
      (node (ref "RP1") (pin "8") (pinfunction "+5V_8") (pintype "unspecified"))
      (node (ref "U1E") (pin "5") (pinfunction "2B_5") (pintype "unspecified"))
      (node (ref "U1E") (pin "9") (pinfunction "3A_9") (pintype "unspecified"))
    )
    (net (code "188") (name "RP1_11") (class "Default")
      (node (ref "RP1") (pin "11") (pinfunction "+5V_11") (pintype "unspecified"))
      (node (ref "U1C") (pin "1") (pinfunction "U-D_1") (pintype "unspecified"))
      (node (ref "U1D") (pin "6") (pinfunction "G1_6") (pintype "unspecified"))
    )
    (net (code "189") (name "RP1_12") (class "Default")
      (node (ref "RP1") (pin "12") (pinfunction "+5V_12") (pintype "unspecified"))
      (node (ref "U13A") (pin "17") (pinfunction "HALT_17") (pintype "unspecified"))
      (node (ref "U2E") (pin "1") (pinfunction "1A_1") (pintype "unspecified"))
      (node (ref "U4E") (pin "15") (pinfunction "CLR_15") (pintype "unspecified"))
      (node (ref "U7A") (pin "3") (pinfunction "1Y_3") (pintype "unspecified"))
    )
    (net (code "190") (name "RP2_1") (class "Default")
      (node (ref "CN1") (pin "65") (pinfunction "/LDS_65") (pintype "unspecified"))
      (node (ref "RP2") (pin "1") (pinfunction "+5V_1") (pintype "unspecified"))
      (node (ref "U8C") (pin "5") (pinfunction "2Y3_5") (pintype "unspecified"))
    )
    (net (code "191") (name "RP2_2") (class "Default")
      (node (ref "CN1") (pin "66") (pinfunction "/UDS_66") (pintype "unspecified"))
      (node (ref "RP2") (pin "2") (pinfunction "+5V_2") (pintype "unspecified"))
      (node (ref "U8C") (pin "3") (pinfunction "2Y4_3") (pintype "unspecified"))
    )
    (net (code "192") (name "RP2_3") (class "Default")
      (node (ref "RP2") (pin "3") (pinfunction "+5V_3") (pintype "unspecified"))
      (node (ref "U13A") (pin "6") (pinfunction "AS_6") (pintype "unspecified"))
      (node (ref "U13F") (pin "4") (pinfunction "G2A_4") (pintype "unspecified"))
      (node (ref "U2D") (pin "13") (pinfunction "B4_13") (pintype "unspecified"))
      (node (ref "U8C") (pin "13") (pinfunction "2A2_13") (pintype "unspecified"))
    )
    (net (code "193") (name "RP2_6") (class "Default")
      (node (ref "CN1") (pin "116") (pinfunction "/NMI_116") (pintype "unspecified"))
      (node (ref "RP2") (pin "6") (pinfunction "+5V_6") (pintype "unspecified"))
      (node (ref "U10C") (pin "13") (pinfunction "1C_13") (pintype "unspecified"))
    )
    (net (code "194") (name "SEG1") (class "Default")
      (node (ref "U4E") (pin "6") (pinfunction "Q2_6") (pintype "unspecified"))
      (node (ref "U7C") (pin "5") (pinfunction "2B_5") (pintype "unspecified"))
    )
    (net (code "195") (name "SEG2") (class "Default")
      (node (ref "U4E") (pin "7") (pinfunction "Q3_7") (pintype "unspecified"))
      (node (ref "U7C") (pin "9") (pinfunction "3A_9") (pintype "unspecified"))
    )
    (net (code "196") (name "SN") (class "Default")
      (node (ref "R8") (pin "1") (pinfunction "1_1") (pintype "unspecified"))
      (node (ref "U6C") (pin "14") (pinfunction "D7_14") (pintype "unspecified"))
    )
    (net (code "197") (name "SPIO") (class "Default")
      (node (ref "U2C") (pin "13") (pinfunction "1E_13") (pintype "unspecified"))
      (node (ref "U3B") (pin "6") (pinfunction "1Q_6") (pintype "unspecified"))
      (node (ref "U6A") (pin "9") (pinfunction "3B_9") (pintype "unspecified"))
    )
    (net (code "198") (name "TD0") (class "Default")
      (node (ref "U11B") (pin "2") (pinfunction "A1_2") (pintype "unspecified"))
      (node (ref "U8A") (pin "14") (pinfunction "VO1_14") (pintype "unspecified"))
      (node (ref "U8B") (pin "5") (pinfunction "A1_5") (pintype "unspecified"))
    )
    (net (code "199") (name "TD1") (class "Default")
      (node (ref "U11B") (pin "3") (pinfunction "A2_3") (pintype "unspecified"))
      (node (ref "U8A") (pin "13") (pinfunction "VO2_13") (pintype "unspecified"))
      (node (ref "U8B") (pin "3") (pinfunction "A2_3") (pintype "unspecified"))
    )
    (net (code "200") (name "TD2") (class "Default")
      (node (ref "U11B") (pin "4") (pinfunction "A3_4") (pintype "unspecified"))
      (node (ref "U8A") (pin "12") (pinfunction "VO3_12") (pintype "unspecified"))
      (node (ref "U8B") (pin "14") (pinfunction "A3_14") (pintype "unspecified"))
    )
    (net (code "201") (name "TD3") (class "Default")
      (node (ref "U11B") (pin "5") (pinfunction "A4_5") (pintype "unspecified"))
      (node (ref "U8A") (pin "11") (pinfunction "VO4_11") (pintype "unspecified"))
      (node (ref "U8B") (pin "12") (pinfunction "A4_12") (pintype "unspecified"))
    )
    (net (code "202") (name "TD4") (class "Default")
      (node (ref "U11B") (pin "6") (pinfunction "A5_6") (pintype "unspecified"))
      (node (ref "U9A") (pin "14") (pinfunction "VO1_14") (pintype "unspecified"))
      (node (ref "U9B") (pin "5") (pinfunction "A1_5") (pintype "unspecified"))
    )
    (net (code "203") (name "TD5") (class "Default")
      (node (ref "U11B") (pin "7") (pinfunction "A6_7") (pintype "unspecified"))
      (node (ref "U9A") (pin "13") (pinfunction "VO2_13") (pintype "unspecified"))
      (node (ref "U9B") (pin "3") (pinfunction "A2_3") (pintype "unspecified"))
    )
    (net (code "204") (name "TD6") (class "Default")
      (node (ref "U11B") (pin "8") (pinfunction "A7_8") (pintype "unspecified"))
      (node (ref "U9A") (pin "12") (pinfunction "VO3_12") (pintype "unspecified"))
      (node (ref "U9B") (pin "14") (pinfunction "A3_14") (pintype "unspecified"))
    )
    (net (code "205") (name "TD7") (class "Default")
      (node (ref "U11B") (pin "9") (pinfunction "A8_9") (pintype "unspecified"))
      (node (ref "U9A") (pin "11") (pinfunction "VO4_11") (pintype "unspecified"))
      (node (ref "U9B") (pin "12") (pinfunction "A4_12") (pintype "unspecified"))
    )
    (net (code "206") (name "U1A_2") (class "Default")
      (node (ref "U11E") (pin "3") (pinfunction "1D_3") (pintype "unspecified"))
      (node (ref "U1A") (pin "2") (pinfunction "B1_2") (pintype "unspecified"))
      (node (ref "U1B") (pin "9") (pinfunction "4A_9") (pintype "unspecified"))
      (node (ref "U1C") (pin "11") (pinfunction "QD_11") (pintype "unspecified"))
      (node (ref "U3A") (pin "3") (pinfunction "1K_3") (pintype "unspecified"))
      (node (ref "U4A") (pin "12") (pinfunction "4A_12") (pintype "unspecified"))
      (node (ref "U6B") (pin "11") (pinfunction "G_11") (pintype "unspecified"))
      (node (ref "U7B") (pin "1") (pinfunction "1ACLK_1") (pintype "unspecified"))
    )
    (net (code "207") (name "U1A_3") (class "Default")
      (node (ref "U1A") (pin "3") (pinfunction "Y1_3") (pintype "unspecified"))
      (node (ref "U3C") (pin "5") (pinfunction "1PR_5") (pintype "unspecified"))
    )
    (net (code "208") (name "U1B_1") (class "Default")
      (node (ref "U1B") (pin "1") (pinfunction "1A_1") (pintype "unspecified"))
      (node (ref "U1D") (pin "10") (pinfunction "Y5_10") (pintype "unspecified"))
    )
    (net (code "209") (name "U1B_2") (class "Default")
      (node (ref "U1B") (pin "2") (pinfunction "/1Y_2") (pintype "unspecified"))
      (node (ref "U3C") (pin "2") (pinfunction "1J_2") (pintype "unspecified"))
    )
    (net (code "210") (name "U1B_3") (class "Default")
      (node (ref "U1B") (pin "3") (pinfunction "2A_3") (pintype "unspecified"))
      (node (ref "U1D") (pin "9") (pinfunction "Y6_9") (pintype "unspecified"))
      (node (ref "U3E") (pin "2") (pinfunction "1J_2") (pintype "unspecified"))
      (node (ref "U3E") (pin "3") (pinfunction "1K_3") (pintype "unspecified"))
      (node (ref "U4B") (pin "13") (pinfunction "2K_13") (pintype "unspecified"))
      (node (ref "U6A") (pin "6") (pinfunction "2B_6") (pintype "unspecified"))
    )
    (net (code "211") (name "U1B_4") (class "Default")
      (node (ref "U1B") (pin "4") (pinfunction "/2Y_4") (pintype "unspecified"))
      (node (ref "U3C") (pin "14") (pinfunction "2J_14") (pintype "unspecified"))
    )
    (net (code "212") (name "U1B_8") (class "Default")
      (node (ref "U1B") (pin "8") (pinfunction "/4Y_8") (pintype "unspecified"))
      (node (ref "U2B") (pin "3") (pinfunction "1K_3") (pintype "unspecified"))
      (node (ref "U5A") (pin "3") (pinfunction "2A_3") (pintype "unspecified"))
      (node (ref "U6A") (pin "5") (pinfunction "2A_5") (pintype "unspecified"))
    )
    (net (code "213") (name "U1B_13") (class "Default")
      (node (ref "U14F") (pin "5") (pinfunction "1Y1_5") (pintype "unspecified"))
      (node (ref "U1B") (pin "13") (pinfunction "6A_13") (pintype "unspecified"))
      (node (ref "U7C") (pin "1") (pinfunction "1A_1") (pintype "unspecified"))
    )
    (net (code "214") (name "U1E_2") (class "Default")
      (node (ref "Q2") (pin "3") (pinfunction "3_3") (pintype "unspecified"))
      (node (ref "R13") (pin "2") (pinfunction "2_2") (pintype "unspecified"))
      (node (ref "U1E") (pin "2") (pinfunction "1B_2") (pintype "unspecified"))
    )
    (net (code "215") (name "U1E_12") (class "Default")
      (node (ref "U1E") (pin "12") (pinfunction "4A_12") (pintype "unspecified"))
      (node (ref "U1E") (pin "13") (pinfunction "4B_13") (pintype "unspecified"))
      (node (ref "U5B") (pin "4") (pinfunction "2Y_4") (pintype "unspecified"))
      (node (ref "U7A") (pin "12") (pinfunction "4A_12") (pintype "unspecified"))
      (node (ref "U7A") (pin "9") (pinfunction "3A_9") (pintype "unspecified"))
    )
    (net (code "216") (name "U2E_5") (class "Default")
      (node (ref "U2E") (pin "5") (pinfunction "3A_5") (pintype "unspecified"))
      (node (ref "U3A") (pin "6") (pinfunction "1Q_6") (pintype "unspecified"))
    )
    (net (code "217") (name "U2E_6") (class "Default")
      (node (ref "CN1") (pin "62") (pinfunction "/DTACK_62") (pintype "unspecified"))
      (node (ref "R1") (pin "1") (pinfunction "1_1") (pintype "unspecified"))
      (node (ref "U2E") (pin "6") (pinfunction "3Y_6") (pintype "unspecified"))
      (node (ref "U2E") (pin "8") (pinfunction "4Y_8") (pintype "unspecified"))
      (node (ref "U3A") (pin "1") (pinfunction "1CLR_1") (pintype "unspecified"))
    )
    (net (code "218") (name "U2E_9") (class "Default")
      (node (ref "U13F") (pin "7") (pinfunction "Y7_7") (pintype "unspecified"))
      (node (ref "U14F") (pin "15") (pinfunction "2G_15") (pintype "unspecified"))
      (node (ref "U2E") (pin "9") (pinfunction "4A_9") (pintype "unspecified"))
    )
    (net (code "219") (name "U3D_11") (class "Default")
      (node (ref "U1B") (pin "10") (pinfunction "/5Y_10") (pintype "unspecified"))
      (node (ref "U3D") (pin "11") (pinfunction "2E_11") (pintype "unspecified"))
    )
    (net (code "220") (name "U4D_6") (class "Default")
      (node (ref "U15F") (pin "2") (pinfunction "1B_2") (pintype "unspecified"))
      (node (ref "U2D") (pin "9") (pinfunction "A3_9") (pintype "unspecified"))
      (node (ref "U4D") (pin "6") (pinfunction "2Y_6") (pintype "unspecified"))
    )
    (net (code "221") (name "U5A_2") (class "Default")
      (node (ref "U2D") (pin "3") (pinfunction "Y1_3") (pintype "unspecified"))
      (node (ref "U5A") (pin "2") (pinfunction "1B_2") (pintype "unspecified"))
    )
    (net (code "222") (name "U5A_6") (class "Default")
      (node (ref "U3C") (pin "11") (pinfunction "2PR_11") (pintype "unspecified"))
      (node (ref "U5A") (pin "6") (pinfunction "2Y_6") (pintype "unspecified"))
    )
    (net (code "223") (name "U5A_13") (class "Default")
      (node (ref "U4D") (pin "3") (pinfunction "1Y_3") (pintype "unspecified"))
      (node (ref "U5A") (pin "13") (pinfunction "1C_13") (pintype "unspecified"))
    )
    (net (code "224") (name "U5B_1") (class "Default")
      (node (ref "U3D") (pin "4") (pinfunction "2A_4") (pintype "unspecified"))
      (node (ref "U5A") (pin "1") (pinfunction "1A_1") (pintype "unspecified"))
      (node (ref "U5B") (pin "1") (pinfunction "1Y_1") (pintype "unspecified"))
    )
    (net (code "225") (name "U5B_3") (class "Default")
      (node (ref "U2B") (pin "7") (pinfunction "/1Q_7") (pintype "unspecified"))
      (node (ref "U2C") (pin "3") (pinfunction "1C_3") (pintype "unspecified"))
      (node (ref "U3D") (pin "13") (pinfunction "1E_13") (pintype "unspecified"))
      (node (ref "U3D") (pin "9") (pinfunction "2C_9") (pintype "unspecified"))
      (node (ref "U5B") (pin "3") (pinfunction "1B_3") (pintype "unspecified"))
      (node (ref "U5B") (pin "5") (pinfunction "2A_5") (pintype "unspecified"))
    )
    (net (code "226") (name "U5D_13") (class "Default")
      (node (ref "U2D") (pin "6") (pinfunction "Y2_6") (pintype "unspecified"))
      (node (ref "U5D") (pin "13") (pinfunction "2K_13") (pintype "unspecified"))
    )
    (net (code "227") (name "U6A_4") (class "Default")
      (node (ref "U4B") (pin "14") (pinfunction "2J_14") (pintype "unspecified"))
      (node (ref "U6A") (pin "4") (pinfunction "2Y_4") (pintype "unspecified"))
    )
    (net (code "228") (name "U6A_8") (class "Default")
      (node (ref "U3A") (pin "7") (pinfunction "/1Q_7") (pintype "unspecified"))
      (node (ref "U6A") (pin "8") (pinfunction "3A_8") (pintype "unspecified"))
    )
    (net (code "229") (name "U6D_1") (class "Default")
      (node (ref "U6B") (pin "15") (pinfunction "6Q_15") (pintype "unspecified"))
      (node (ref "U6D") (pin "1") (pinfunction "1A_1") (pintype "unspecified"))
    )
    (net (code "230") (name "U6D_2") (class "Default")
      (node (ref "U5E") (pin "9") (pinfunction "2QC_9") (pintype "unspecified"))
      (node (ref "U6C") (pin "19") (pinfunction "A7_19") (pintype "unspecified"))
      (node (ref "U6D") (pin "2") (pinfunction "1B_2") (pintype "unspecified"))
      (node (ref "U7F") (pin "6") (pinfunction "INH_6") (pintype "unspecified"))
      (node (ref "U8F") (pin "6") (pinfunction "INH_6") (pintype "unspecified"))
    )
    (net (code "231") (name "U7A_10") (class "Default")
      (node (ref "U4E") (pin "4") (pinfunction "Q0_4") (pintype "unspecified"))
      (node (ref "U7A") (pin "10") (pinfunction "3B_10") (pintype "unspecified"))
    )
    (net (code "232") (name "U7A_13") (class "Default")
      (node (ref "U4E") (pin "5") (pinfunction "Q1_5") (pintype "unspecified"))
      (node (ref "U7A") (pin "13") (pinfunction "4B_13") (pintype "unspecified"))
    )
    (net (code "233") (name "U7C_11") (class "Default")
      (node (ref "U5A") (pin "4") (pinfunction "2B_4") (pintype "unspecified"))
      (node (ref "U7C") (pin "11") (pinfunction "/4Y_11") (pintype "unspecified"))
    )
    (net (code "234") (name "U8C_2") (class "Default")
      (node (ref "U5E") (pin "3") (pinfunction "1QA_3") (pintype "unspecified"))
      (node (ref "U6C") (pin "18") (pinfunction "A6_18") (pintype "unspecified"))
      (node (ref "U7E") (pin "3") (pinfunction "1C3_3") (pintype "unspecified"))
      (node (ref "U8C") (pin "2") (pinfunction "1A1_2") (pintype "unspecified"))
    )
    (net (code "235") (name "U8C_4") (class "Default")
      (node (ref "U5E") (pin "4") (pinfunction "1QB_4") (pintype "unspecified"))
      (node (ref "U7E") (pin "13") (pinfunction "2C3_13") (pintype "unspecified"))
      (node (ref "U8C") (pin "4") (pinfunction "1A2_4") (pintype "unspecified"))
    )
    (net (code "236") (name "U15F_4") (class "Default")
      (node (ref "U14F") (pin "1") (pinfunction "1G_1") (pintype "unspecified"))
      (node (ref "U15F") (pin "4") (pinfunction "2A_4") (pintype "unspecified"))
      (node (ref "U3B") (pin "7") (pinfunction "/1Q_7") (pintype "unspecified"))
      (node (ref "U5A") (pin "11") (pinfunction "3C_11") (pintype "unspecified"))
    )
    (net (code "237") (name "UA1") (class "Default")
      (node (ref "U13A") (pin "29") (pinfunction "A1_29") (pintype "unspecified"))
      (node (ref "U13D") (pin "10") (pinfunction "A0_10") (pintype "unspecified"))
      (node (ref "U14D") (pin "10") (pinfunction "A0_10") (pintype "unspecified"))
      (node (ref "U15C") (pin "17") (pinfunction "2A4_17") (pintype "unspecified"))
    )
    (net (code "238") (name "UA2") (class "Default")
      (node (ref "U13A") (pin "30") (pinfunction "A2_30") (pintype "unspecified"))
      (node (ref "U13D") (pin "9") (pinfunction "A1_9") (pintype "unspecified"))
      (node (ref "U14D") (pin "9") (pinfunction "A1_9") (pintype "unspecified"))
      (node (ref "U15C") (pin "15") (pinfunction "2A3_15") (pintype "unspecified"))
    )
    (net (code "239") (name "UA3") (class "Default")
      (node (ref "U13A") (pin "31") (pinfunction "A3_31") (pintype "unspecified"))
      (node (ref "U13D") (pin "8") (pinfunction "A2_8") (pintype "unspecified"))
      (node (ref "U14D") (pin "8") (pinfunction "A2_8") (pintype "unspecified"))
      (node (ref "U15C") (pin "13") (pinfunction "2A2_13") (pintype "unspecified"))
      (node (ref "U6D") (pin "13") (pinfunction "4B_13") (pintype "unspecified"))
    )
    (net (code "240") (name "UA4") (class "Default")
      (node (ref "U13A") (pin "32") (pinfunction "A4_32") (pintype "unspecified"))
      (node (ref "U13D") (pin "7") (pinfunction "A3_7") (pintype "unspecified"))
      (node (ref "U14D") (pin "7") (pinfunction "A3_7") (pintype "unspecified"))
      (node (ref "U15C") (pin "11") (pinfunction "2A1_11") (pintype "unspecified"))
    )
    (net (code "241") (name "UA5") (class "Default")
      (node (ref "U13A") (pin "33") (pinfunction "A5_33") (pintype "unspecified"))
      (node (ref "U13D") (pin "6") (pinfunction "A4_6") (pintype "unspecified"))
      (node (ref "U14D") (pin "6") (pinfunction "A4_6") (pintype "unspecified"))
      (node (ref "U15C") (pin "8") (pinfunction "1A4_8") (pintype "unspecified"))
    )
    (net (code "242") (name "UA6") (class "Default")
      (node (ref "U13A") (pin "34") (pinfunction "A6_34") (pintype "unspecified"))
      (node (ref "U13D") (pin "5") (pinfunction "A5_5") (pintype "unspecified"))
      (node (ref "U14D") (pin "5") (pinfunction "A5_5") (pintype "unspecified"))
      (node (ref "U15C") (pin "6") (pinfunction "1A3_6") (pintype "unspecified"))
    )
    (net (code "243") (name "UA7") (class "Default")
      (node (ref "U13A") (pin "35") (pinfunction "A7_35") (pintype "unspecified"))
      (node (ref "U13D") (pin "4") (pinfunction "A6_4") (pintype "unspecified"))
      (node (ref "U14D") (pin "4") (pinfunction "A6_4") (pintype "unspecified"))
      (node (ref "U15C") (pin "4") (pinfunction "1A2_4") (pintype "unspecified"))
    )
    (net (code "244") (name "UA8") (class "Default")
      (node (ref "U13A") (pin "36") (pinfunction "A8_36") (pintype "unspecified"))
      (node (ref "U13D") (pin "3") (pinfunction "A7_3") (pintype "unspecified"))
      (node (ref "U14D") (pin "3") (pinfunction "A7_3") (pintype "unspecified"))
      (node (ref "U15C") (pin "2") (pinfunction "1A1_2") (pintype "unspecified"))
    )
    (net (code "245") (name "UA9") (class "Default")
      (node (ref "U13A") (pin "37") (pinfunction "A9_37") (pintype "unspecified"))
      (node (ref "U13D") (pin "25") (pinfunction "A8_25") (pintype "unspecified"))
      (node (ref "U14D") (pin "25") (pinfunction "A8_25") (pintype "unspecified"))
      (node (ref "U8B") (pin "6") (pinfunction "B1_6") (pintype "unspecified"))
    )
    (net (code "246") (name "UA10") (class "Default")
      (node (ref "U13A") (pin "38") (pinfunction "A10_38") (pintype "unspecified"))
      (node (ref "U13D") (pin "24") (pinfunction "A9_24") (pintype "unspecified"))
      (node (ref "U14D") (pin "24") (pinfunction "A9_24") (pintype "unspecified"))
      (node (ref "U8B") (pin "2") (pinfunction "B2_2") (pintype "unspecified"))
    )
    (net (code "247") (name "UA11") (class "Default")
      (node (ref "U13A") (pin "39") (pinfunction "A11_39") (pintype "unspecified"))
      (node (ref "U13D") (pin "21") (pinfunction "A10_21") (pintype "unspecified"))
      (node (ref "U14D") (pin "21") (pinfunction "A10_21") (pintype "unspecified"))
      (node (ref "U8B") (pin "15") (pinfunction "B3_15") (pintype "unspecified"))
    )
    (net (code "248") (name "UA12") (class "Default")
      (node (ref "J1") (pin "2") (pinfunction "2_2") (pintype "unspecified"))
      (node (ref "U13A") (pin "40") (pinfunction "A12_40") (pintype "unspecified"))
      (node (ref "U13D") (pin "23") (pinfunction "A11_23") (pintype "unspecified"))
      (node (ref "U14D") (pin "23") (pinfunction "A11_23") (pintype "unspecified"))
      (node (ref "U8B") (pin "11") (pinfunction "B4_11") (pintype "unspecified"))
    )
    (net (code "249") (name "UA13") (class "Default")
      (node (ref "U13A") (pin "41") (pinfunction "A13_41") (pintype "unspecified"))
      (node (ref "U13D") (pin "2") (pinfunction "A12_2") (pintype "unspecified"))
      (node (ref "U14D") (pin "2") (pinfunction "A12_2") (pintype "unspecified"))
      (node (ref "U9B") (pin "6") (pinfunction "B1_6") (pintype "unspecified"))
    )
    (net (code "250") (name "UA14") (class "Default")
      (node (ref "U13A") (pin "42") (pinfunction "A14_42") (pintype "unspecified"))
      (node (ref "U5B") (pin "12") (pinfunction "4B_12") (pintype "unspecified"))
      (node (ref "U9B") (pin "2") (pinfunction "B2_2") (pintype "unspecified"))
    )
    (net (code "251") (name "UA15") (class "Default")
      (node (ref "U13A") (pin "43") (pinfunction "A15_43") (pintype "unspecified"))
      (node (ref "U14F") (pin "2") (pinfunction "1A_2") (pintype "unspecified"))
      (node (ref "U9B") (pin "15") (pinfunction "B3_15") (pintype "unspecified"))
    )
    (net (code "252") (name "UA16") (class "Default")
      (node (ref "U13A") (pin "44") (pinfunction "A16_44") (pintype "unspecified"))
      (node (ref "U14F") (pin "3") (pinfunction "1B_3") (pintype "unspecified"))
      (node (ref "U9B") (pin "11") (pinfunction "B4_11") (pintype "unspecified"))
    )
    (net (code "253") (name "UA17") (class "Default")
      (node (ref "U10A") (pin "17") (pinfunction "A7_17") (pintype "unspecified"))
      (node (ref "U13A") (pin "45") (pinfunction "A17_45") (pintype "unspecified"))
      (node (ref "U8A") (pin "17") (pinfunction "A7_17") (pintype "unspecified"))
      (node (ref "U9A") (pin "17") (pinfunction "A7_17") (pintype "unspecified"))
    )
    (net (code "254") (name "UA18") (class "Default")
      (node (ref "U10A") (pin "16") (pinfunction "A8_16") (pintype "unspecified"))
      (node (ref "U13A") (pin "46") (pinfunction "A18_46") (pintype "unspecified"))
      (node (ref "U8A") (pin "16") (pinfunction "A8_16") (pintype "unspecified"))
      (node (ref "U9A") (pin "16") (pinfunction "A8_16") (pintype "unspecified"))
    )
    (net (code "255") (name "UA19") (class "Default")
      (node (ref "U10A") (pin "15") (pinfunction "A9_15") (pintype "unspecified"))
      (node (ref "U13A") (pin "47") (pinfunction "A19_47") (pintype "unspecified"))
      (node (ref "U8A") (pin "15") (pinfunction "A9_15") (pintype "unspecified"))
      (node (ref "U9A") (pin "15") (pinfunction "A9_15") (pintype "unspecified"))
    )
    (net (code "256") (name "UA20") (class "Default")
      (node (ref "U10A") (pin "7") (pinfunction "A2_7") (pintype "unspecified"))
      (node (ref "U13A") (pin "48") (pinfunction "A20_48") (pintype "unspecified"))
      (node (ref "U8A") (pin "7") (pinfunction "A2_7") (pintype "unspecified"))
      (node (ref "U9A") (pin "7") (pinfunction "A2_7") (pintype "unspecified"))
    )
    (net (code "257") (name "UA21") (class "Default")
      (node (ref "U10A") (pin "1") (pinfunction "A6_1") (pintype "unspecified"))
      (node (ref "U13A") (pin "50") (pinfunction "A21_50") (pintype "unspecified"))
      (node (ref "U8A") (pin "1") (pinfunction "A6_1") (pintype "unspecified"))
      (node (ref "U9A") (pin "1") (pinfunction "A6_1") (pintype "unspecified"))
    )
    (net (code "258") (name "UA22") (class "Default")
      (node (ref "U10A") (pin "2") (pinfunction "A5_2") (pintype "unspecified"))
      (node (ref "U13A") (pin "51") (pinfunction "A22_51") (pintype "unspecified"))
      (node (ref "U8A") (pin "2") (pinfunction "A5_2") (pintype "unspecified"))
      (node (ref "U9A") (pin "2") (pinfunction "A5_2") (pintype "unspecified"))
    )
    (net (code "259") (name "UA23") (class "Default")
      (node (ref "U10A") (pin "3") (pinfunction "A4_3") (pintype "unspecified"))
      (node (ref "U13A") (pin "52") (pinfunction "A23_52") (pintype "unspecified"))
      (node (ref "U8A") (pin "3") (pinfunction "A4_3") (pintype "unspecified"))
      (node (ref "U9A") (pin "3") (pinfunction "A4_3") (pintype "unspecified"))
    )
    (net (code "260") (name "UD0") (class "Default")
      (node (ref "U11B") (pin "18") (pinfunction "B1_18") (pintype "unspecified"))
      (node (ref "U11C") (pin "7") (pinfunction "3D_7") (pintype "unspecified"))
      (node (ref "U13A") (pin "5") (pinfunction "D0_5") (pintype "unspecified"))
      (node (ref "U14D") (pin "11") (pinfunction "O0_11") (pintype "unspecified"))
      (node (ref "U15E") (pin "18") (pinfunction "B1_18") (pintype "unspecified"))
    )
    (net (code "261") (name "UD1") (class "Default")
      (node (ref "U11B") (pin "17") (pinfunction "B2_17") (pintype "unspecified"))
      (node (ref "U11C") (pin "8") (pinfunction "4D_8") (pintype "unspecified"))
      (node (ref "U13A") (pin "4") (pinfunction "D1_4") (pintype "unspecified"))
      (node (ref "U14D") (pin "12") (pinfunction "O1_12") (pintype "unspecified"))
      (node (ref "U15E") (pin "17") (pinfunction "B2_17") (pintype "unspecified"))
    )
    (net (code "262") (name "UD2") (class "Default")
      (node (ref "U11B") (pin "16") (pinfunction "B3_16") (pintype "unspecified"))
      (node (ref "U11C") (pin "13") (pinfunction "5D_13") (pintype "unspecified"))
      (node (ref "U13A") (pin "3") (pinfunction "D2_3") (pintype "unspecified"))
      (node (ref "U14D") (pin "13") (pinfunction "O2_13") (pintype "unspecified"))
      (node (ref "U15E") (pin "16") (pinfunction "B3_16") (pintype "unspecified"))
    )
    (net (code "263") (name "UD3") (class "Default")
      (node (ref "U11B") (pin "15") (pinfunction "B4_15") (pintype "unspecified"))
      (node (ref "U11C") (pin "14") (pinfunction "6D_14") (pintype "unspecified"))
      (node (ref "U13A") (pin "2") (pinfunction "D3_2") (pintype "unspecified"))
      (node (ref "U14D") (pin "15") (pinfunction "O3_15") (pintype "unspecified"))
      (node (ref "U15E") (pin "15") (pinfunction "B4_15") (pintype "unspecified"))
    )
    (net (code "264") (name "UD4") (class "Default")
      (node (ref "U11B") (pin "14") (pinfunction "B5_14") (pintype "unspecified"))
      (node (ref "U11C") (pin "17") (pinfunction "7D_17") (pintype "unspecified"))
      (node (ref "U13A") (pin "1") (pinfunction "D4_1") (pintype "unspecified"))
      (node (ref "U14D") (pin "16") (pinfunction "O4_16") (pintype "unspecified"))
      (node (ref "U15E") (pin "14") (pinfunction "B5_14") (pintype "unspecified"))
    )
    (net (code "265") (name "UD5") (class "Default")
      (node (ref "U11B") (pin "13") (pinfunction "B6_13") (pintype "unspecified"))
      (node (ref "U11C") (pin "18") (pinfunction "8D_18") (pintype "unspecified"))
      (node (ref "U13A") (pin "64") (pinfunction "D5_64") (pintype "unspecified"))
      (node (ref "U14D") (pin "17") (pinfunction "O5_17") (pintype "unspecified"))
      (node (ref "U15E") (pin "13") (pinfunction "B6_13") (pintype "unspecified"))
    )
    (net (code "266") (name "UD6") (class "Default")
      (node (ref "U11B") (pin "12") (pinfunction "B7_12") (pintype "unspecified"))
      (node (ref "U13A") (pin "63") (pinfunction "D6_63") (pintype "unspecified"))
      (node (ref "U14D") (pin "18") (pinfunction "O6_18") (pintype "unspecified"))
      (node (ref "U15E") (pin "12") (pinfunction "B7_12") (pintype "unspecified"))
    )
    (net (code "267") (name "UD7") (class "Default")
      (node (ref "U11B") (pin "11") (pinfunction "B8_11") (pintype "unspecified"))
      (node (ref "U13A") (pin "62") (pinfunction "D7_62") (pintype "unspecified"))
      (node (ref "U14D") (pin "19") (pinfunction "O7_19") (pintype "unspecified"))
      (node (ref "U15E") (pin "11") (pinfunction "B8_11") (pintype "unspecified"))
    )
    (net (code "268") (name "UD8") (class "Default")
      (node (ref "U11A") (pin "18") (pinfunction "B1_18") (pintype "unspecified"))
      (node (ref "U13A") (pin "61") (pinfunction "D8_61") (pintype "unspecified"))
      (node (ref "U13D") (pin "11") (pinfunction "O0_11") (pintype "unspecified"))
      (node (ref "U14E") (pin "18") (pinfunction "B1_18") (pintype "unspecified"))
    )
    (net (code "269") (name "UD9") (class "Default")
      (node (ref "U11A") (pin "17") (pinfunction "B2_17") (pintype "unspecified"))
      (node (ref "U13A") (pin "60") (pinfunction "D9_60") (pintype "unspecified"))
      (node (ref "U13D") (pin "12") (pinfunction "O1_12") (pintype "unspecified"))
      (node (ref "U14E") (pin "17") (pinfunction "B2_17") (pintype "unspecified"))
    )
    (net (code "270") (name "UD10") (class "Default")
      (node (ref "U11A") (pin "16") (pinfunction "B3_16") (pintype "unspecified"))
      (node (ref "U13A") (pin "59") (pinfunction "D10_59") (pintype "unspecified"))
      (node (ref "U13D") (pin "13") (pinfunction "O2_13") (pintype "unspecified"))
      (node (ref "U14E") (pin "16") (pinfunction "B3_16") (pintype "unspecified"))
    )
    (net (code "271") (name "UD11") (class "Default")
      (node (ref "U11A") (pin "15") (pinfunction "B4_15") (pintype "unspecified"))
      (node (ref "U13A") (pin "58") (pinfunction "D11_58") (pintype "unspecified"))
      (node (ref "U13D") (pin "15") (pinfunction "O3_15") (pintype "unspecified"))
      (node (ref "U14E") (pin "15") (pinfunction "B4_15") (pintype "unspecified"))
    )
    (net (code "272") (name "UD12") (class "Default")
      (node (ref "U13A") (pin "57") (pinfunction "D12_57") (pintype "unspecified"))
      (node (ref "U13D") (pin "16") (pinfunction "O4_16") (pintype "unspecified"))
      (node (ref "U14E") (pin "14") (pinfunction "B5_14") (pintype "unspecified"))
    )
    (net (code "273") (name "UD13") (class "Default")
      (node (ref "U13A") (pin "56") (pinfunction "D13_56") (pintype "unspecified"))
      (node (ref "U13D") (pin "17") (pinfunction "O5_17") (pintype "unspecified"))
      (node (ref "U14E") (pin "13") (pinfunction "B6_13") (pintype "unspecified"))
    )
    (net (code "274") (name "UD14") (class "Default")
      (node (ref "U11A") (pin "12") (pinfunction "B7_12") (pintype "unspecified"))
      (node (ref "U13A") (pin "55") (pinfunction "D14_55") (pintype "unspecified"))
      (node (ref "U13D") (pin "18") (pinfunction "O6_18") (pintype "unspecified"))
      (node (ref "U14E") (pin "12") (pinfunction "B7_12") (pintype "unspecified"))
    )
    (net (code "275") (name "UD15") (class "Default")
      (node (ref "U11A") (pin "11") (pinfunction "B8_11") (pintype "unspecified"))
      (node (ref "U13A") (pin "54") (pinfunction "D15_54") (pintype "unspecified"))
      (node (ref "U13D") (pin "19") (pinfunction "O7_19") (pintype "unspecified"))
      (node (ref "U14E") (pin "11") (pinfunction "B8_11") (pintype "unspecified"))
    )
    (net (code "276") (name "VA1") (class "Default")
      (node (ref "U6F") (pin "3") (pinfunction "1QA_3") (pintype "unspecified"))
      (node (ref "U7E") (pin "5") (pinfunction "1C1_5") (pintype "unspecified"))
    )
    (net (code "277") (name "VA2") (class "Default")
      (node (ref "U6F") (pin "4") (pinfunction "1QB_4") (pintype "unspecified"))
      (node (ref "U7E") (pin "11") (pinfunction "2C1_11") (pintype "unspecified"))
    )
    (net (code "278") (name "VA3") (class "Default")
      (node (ref "U6E") (pin "5") (pinfunction "1C1_5") (pintype "unspecified"))
      (node (ref "U6F") (pin "5") (pinfunction "1QC_5") (pintype "unspecified"))
    )
    (net (code "279") (name "VA4") (class "Default")
      (node (ref "U6E") (pin "11") (pinfunction "2C1_11") (pintype "unspecified"))
      (node (ref "U6F") (pin "13") (pinfunction "2ACLK_13") (pintype "unspecified"))
      (node (ref "U6F") (pin "6") (pinfunction "1QD_6") (pintype "unspecified"))
    )
    (net (code "280") (name "VA5") (class "Default")
      (node (ref "U5F") (pin "5") (pinfunction "1C1_5") (pintype "unspecified"))
      (node (ref "U6F") (pin "11") (pinfunction "2QA_11") (pintype "unspecified"))
    )
    (net (code "281") (name "VA6") (class "Default")
      (node (ref "U5F") (pin "11") (pinfunction "2C1_11") (pintype "unspecified"))
      (node (ref "U6F") (pin "10") (pinfunction "2QB_10") (pintype "unspecified"))
    )
    (net (code "282") (name "VA7") (class "Default")
      (node (ref "U6F") (pin "9") (pinfunction "2QC_9") (pintype "unspecified"))
      (node (ref "U8E") (pin "5") (pinfunction "1C1_5") (pintype "unspecified"))
    )
    (net (code "283") (name "VA8") (class "Default")
      (node (ref "U4A") (pin "1") (pinfunction "1A_1") (pintype "unspecified"))
      (node (ref "U4D") (pin "4") (pinfunction "2A_4") (pintype "unspecified"))
      (node (ref "U5E") (pin "1") (pinfunction "1ACLK_1") (pintype "unspecified"))
      (node (ref "U6F") (pin "8") (pinfunction "2QD_8") (pintype "unspecified"))
      (node (ref "U8E") (pin "11") (pinfunction "2C1_11") (pintype "unspecified"))
    )
    (net (code "284") (name "VA9B") (class "Default")
      (node (ref "CN1") (pin "70") (pinfunction "VA9B_70") (pintype "unspecified"))
      (node (ref "U8C") (pin "18") (pinfunction "1Y1_18") (pintype "unspecified"))
    )
    (net (code "285") (name "VA10B") (class "Default")
      (node (ref "CN1") (pin "69") (pinfunction "VA10B_69") (pintype "unspecified"))
      (node (ref "U8C") (pin "16") (pinfunction "1Y2_16") (pintype "unspecified"))
    )
    (net (code "286") (name "VA11") (class "Default")
      (node (ref "U4D") (pin "5") (pinfunction "2B_5") (pintype "unspecified"))
      (node (ref "U5E") (pin "5") (pinfunction "1QC_5") (pintype "unspecified"))
      (node (ref "U6E") (pin "3") (pinfunction "1C3_3") (pintype "unspecified"))
    )
    (net (code "287") (name "VA12") (class "Default")
      (node (ref "U5E") (pin "13") (pinfunction "2ACLK_13") (pintype "unspecified"))
      (node (ref "U5E") (pin "6") (pinfunction "1QD_6") (pintype "unspecified"))
      (node (ref "U6E") (pin "13") (pinfunction "2C3_13") (pintype "unspecified"))
    )
    (net (code "288") (name "VA13") (class "Default")
      (node (ref "U5E") (pin "11") (pinfunction "2QA_11") (pintype "unspecified"))
      (node (ref "U5F") (pin "3") (pinfunction "1C3_3") (pintype "unspecified"))
    )
    (net (code "289") (name "VA14") (class "Default")
      (node (ref "U5E") (pin "10") (pinfunction "2QB_10") (pintype "unspecified"))
      (node (ref "U5F") (pin "13") (pinfunction "2C3_13") (pintype "unspecified"))
    )
    (net (code "290") (name "VID") (class "Default")
      (node (ref "CN1") (pin "115") (pinfunction "VID_115") (pintype "unspecified"))
      (node (ref "U4D") (pin "8") (pinfunction "3Y_8") (pintype "unspecified"))
      (node (ref "U9E") (pin "11") (pinfunction "2A1_11") (pintype "unspecified"))
    )
    (net (code "291") (name "unconnected-(U2A-Pad1)") (class "Default")
      (node (ref "U2A") (pin "1") (pinfunction "1_1") (pintype "unspecified+no_connect"))
    )
    (net (code "292") (name "unconnected-(U2A-Pad2)") (class "Default")
      (node (ref "U2A") (pin "2") (pinfunction "2_2") (pintype "unspecified+no_connect"))
    )
    (net (code "293") (name "unconnected-(U2A-Pad3)") (class "Default")
      (node (ref "U2A") (pin "3") (pinfunction "3_3") (pintype "unspecified+no_connect"))
    )
    (net (code "294") (name "unconnected-(U2A-Pad4)") (class "Default")
      (node (ref "U2A") (pin "4") (pinfunction "4_4") (pintype "unspecified+no_connect"))
    )
    (net (code "295") (name "unconnected-(U2A-Pad5)") (class "Default")
      (node (ref "U2A") (pin "5") (pinfunction "5_5") (pintype "unspecified+no_connect"))
    )
    (net (code "296") (name "unconnected-(U2A-Pad6)") (class "Default")
      (node (ref "U2A") (pin "6") (pinfunction "6_6") (pintype "unspecified+no_connect"))
    )
    (net (code "297") (name "unconnected-(U2A-Pad7)") (class "Default")
      (node (ref "U2A") (pin "7") (pinfunction "7_7") (pintype "unspecified+no_connect"))
    )
    (net (code "298") (name "unconnected-(U2A-Pad8)") (class "Default")
      (node (ref "U2A") (pin "8") (pinfunction "8_8") (pintype "unspecified+no_connect"))
    )
    (net (code "299") (name "unconnected-(U2A-Pad9)") (class "Default")
      (node (ref "U2A") (pin "9") (pinfunction "9_9") (pintype "unspecified+no_connect"))
    )
    (net (code "300") (name "unconnected-(U2A-Pad10)") (class "Default")
      (node (ref "U2A") (pin "10") (pinfunction "10_10") (pintype "unspecified+no_connect"))
    )
    (net (code "301") (name "unconnected-(U2A-Pad11)") (class "Default")
      (node (ref "U2A") (pin "11") (pinfunction "11_11") (pintype "unspecified+no_connect"))
    )
    (net (code "302") (name "unconnected-(U2A-Pad12)") (class "Default")
      (node (ref "U2A") (pin "12") (pinfunction "12_12") (pintype "unspecified+no_connect"))
    )
    (net (code "303") (name "unconnected-(U2A-Pad13)") (class "Default")
      (node (ref "U2A") (pin "13") (pinfunction "13_13") (pintype "unspecified+no_connect"))
    )
    (net (code "304") (name "unconnected-(U2A-Pad14)") (class "Default")
      (node (ref "U2A") (pin "14") (pinfunction "14_14") (pintype "unspecified+no_connect"))
    )
    (net (code "305") (name "unconnected-(U2A-Pad15)") (class "Default")
      (node (ref "U2A") (pin "15") (pinfunction "15_15") (pintype "unspecified+no_connect"))
    )
    (net (code "306") (name "unconnected-(U2A-Pad16)") (class "Default")
      (node (ref "U2A") (pin "16") (pinfunction "16_16") (pintype "unspecified+no_connect"))
    )
    (net (code "307") (name "unconnected-(U3A-{slash}2Q-Pad9)") (class "Default")
      (node (ref "U3A") (pin "9") (pinfunction "/2Q_9") (pintype "unspecified+no_connect"))
    )
    (net (code "308") (name "unconnected-(U3E-{slash}1Q-Pad7)") (class "Default")
      (node (ref "U3E") (pin "7") (pinfunction "/1Q_7") (pintype "unspecified+no_connect"))
    )
    (net (code "309") (name "unconnected-(U3E-{slash}2Q-Pad9)") (class "Default")
      (node (ref "U3E") (pin "9") (pinfunction "/2Q_9") (pintype "unspecified+no_connect"))
    )
    (net (code "310") (name "unconnected-(U3F-Pad1)") (class "Default")
      (node (ref "U3F") (pin "1") (pinfunction "1_1") (pintype "unspecified+no_connect"))
    )
    (net (code "311") (name "unconnected-(U3F-Pad2)") (class "Default")
      (node (ref "U3F") (pin "2") (pinfunction "2_2") (pintype "unspecified+no_connect"))
    )
    (net (code "312") (name "unconnected-(U3F-Pad3)") (class "Default")
      (node (ref "U3F") (pin "3") (pinfunction "3_3") (pintype "unspecified+no_connect"))
    )
    (net (code "313") (name "unconnected-(U3F-Pad4)") (class "Default")
      (node (ref "U3F") (pin "4") (pinfunction "4_4") (pintype "unspecified+no_connect"))
    )
    (net (code "314") (name "unconnected-(U3F-Pad5)") (class "Default")
      (node (ref "U3F") (pin "5") (pinfunction "5_5") (pintype "unspecified+no_connect"))
    )
    (net (code "315") (name "unconnected-(U3F-Pad6)") (class "Default")
      (node (ref "U3F") (pin "6") (pinfunction "6_6") (pintype "unspecified+no_connect"))
    )
    (net (code "316") (name "unconnected-(U3F-Pad7)") (class "Default")
      (node (ref "U3F") (pin "7") (pinfunction "7_7") (pintype "unspecified+no_connect"))
    )
    (net (code "317") (name "unconnected-(U3F-Pad8)") (class "Default")
      (node (ref "U3F") (pin "8") (pinfunction "8_8") (pintype "unspecified+no_connect"))
    )
    (net (code "318") (name "unconnected-(U3F-Pad9)") (class "Default")
      (node (ref "U3F") (pin "9") (pinfunction "9_9") (pintype "unspecified+no_connect"))
    )
    (net (code "319") (name "unconnected-(U3F-Pad10)") (class "Default")
      (node (ref "U3F") (pin "10") (pinfunction "10_10") (pintype "unspecified+no_connect"))
    )
    (net (code "320") (name "unconnected-(U3F-Pad11)") (class "Default")
      (node (ref "U3F") (pin "11") (pinfunction "11_11") (pintype "unspecified+no_connect"))
    )
    (net (code "321") (name "unconnected-(U3F-Pad12)") (class "Default")
      (node (ref "U3F") (pin "12") (pinfunction "12_12") (pintype "unspecified+no_connect"))
    )
    (net (code "322") (name "unconnected-(U3F-Pad13)") (class "Default")
      (node (ref "U3F") (pin "13") (pinfunction "13_13") (pintype "unspecified+no_connect"))
    )
    (net (code "323") (name "unconnected-(U3F-Pad14)") (class "Default")
      (node (ref "U3F") (pin "14") (pinfunction "14_14") (pintype "unspecified+no_connect"))
    )
    (net (code "324") (name "unconnected-(U3F-Pad15)") (class "Default")
      (node (ref "U3F") (pin "15") (pinfunction "15_15") (pintype "unspecified+no_connect"))
    )
    (net (code "325") (name "unconnected-(U3F-Pad16)") (class "Default")
      (node (ref "U3F") (pin "16") (pinfunction "16_16") (pintype "unspecified+no_connect"))
    )
    (net (code "326") (name "unconnected-(U3F-Pad17)") (class "Default")
      (node (ref "U3F") (pin "17") (pinfunction "17_17") (pintype "unspecified+no_connect"))
    )
    (net (code "327") (name "unconnected-(U3F-Pad18)") (class "Default")
      (node (ref "U3F") (pin "18") (pinfunction "18_18") (pintype "unspecified+no_connect"))
    )
    (net (code "328") (name "unconnected-(U3F-Pad19)") (class "Default")
      (node (ref "U3F") (pin "19") (pinfunction "19_19") (pintype "unspecified+no_connect"))
    )
    (net (code "329") (name "unconnected-(U3F-Pad20)") (class "Default")
      (node (ref "U3F") (pin "20") (pinfunction "20_20") (pintype "unspecified+no_connect"))
    )
    (net (code "330") (name "unconnected-(U4A-3Y-Pad8)") (class "Default")
      (node (ref "U4A") (pin "8") (pinfunction "3Y_8") (pintype "unspecified+no_connect"))
    )
    (net (code "331") (name "unconnected-(U5D-{slash}1Q-Pad7)") (class "Default")
      (node (ref "U5D") (pin "7") (pinfunction "/1Q_7") (pintype "unspecified+no_connect"))
    )
    (net (code "332") (name "unconnected-(U5D-{slash}2Q-Pad9)") (class "Default")
      (node (ref "U5D") (pin "9") (pinfunction "/2Q_9") (pintype "unspecified+no_connect"))
    )
    (net (code "333") (name "unconnected-(U5E-2QD-Pad8)") (class "Default")
      (node (ref "U5E") (pin "8") (pinfunction "2QD_8") (pintype "unspecified+no_connect"))
    )
    (net (code "334") (name "unconnected-(U6B-8Q-Pad19)") (class "Default")
      (node (ref "U6B") (pin "19") (pinfunction "8Q_19") (pintype "unspecified+no_connect"))
    )
    (net (code "335") (name "unconnected-(U7A-2A-Pad4)") (class "Default")
      (node (ref "U7A") (pin "4") (pinfunction "2A_4") (pintype "unspecified"))
    )
    (net (code "336") (name "unconnected-(U7A-2B-Pad5)") (class "Default")
      (node (ref "U7A") (pin "5") (pinfunction "2B_5") (pintype "unspecified"))
    )
    (net (code "337") (name "unconnected-(U7A-2Y-Pad6)") (class "Default")
      (node (ref "U7A") (pin "6") (pinfunction "2Y_6") (pintype "unspecified"))
    )
    (net (code "338") (name "unconnected-(U7B-2QC-Pad9)") (class "Default")
      (node (ref "U7B") (pin "9") (pinfunction "2QC_9") (pintype "unspecified+no_connect"))
    )
    (net (code "339") (name "unconnected-(U7B-2QD-Pad8)") (class "Default")
      (node (ref "U7B") (pin "8") (pinfunction "2QD_8") (pintype "unspecified+no_connect"))
    )
    (net (code "340") (name "unconnected-(U10B-C4-Pad9)") (class "Default")
      (node (ref "U10B") (pin "9") (pinfunction "C4_9") (pintype "unspecified+no_connect"))
    )
    (net (code "341") (name "unconnected-(U11A-A5-Pad6)") (class "Default")
      (node (ref "U11A") (pin "6") (pinfunction "A5_6") (pintype "unspecified+no_connect"))
    )
    (net (code "342") (name "unconnected-(U11A-A6-Pad7)") (class "Default")
      (node (ref "U11A") (pin "7") (pinfunction "A6_7") (pintype "unspecified+no_connect"))
    )
    (net (code "343") (name "unconnected-(U11A-A7-Pad8)") (class "Default")
      (node (ref "U11A") (pin "8") (pinfunction "A7_8") (pintype "unspecified+no_connect"))
    )
    (net (code "344") (name "unconnected-(U11A-B5-Pad14)") (class "Default")
      (node (ref "U11A") (pin "14") (pinfunction "B5_14") (pintype "unspecified+no_connect"))
    )
    (net (code "345") (name "unconnected-(U11A-B6-Pad13)") (class "Default")
      (node (ref "U11A") (pin "13") (pinfunction "B6_13") (pintype "unspecified+no_connect"))
    )
    (net (code "346") (name "unconnected-(U11C-1Q-Pad2)") (class "Default")
      (node (ref "U11C") (pin "2") (pinfunction "1Q_2") (pintype "unspecified+no_connect"))
    )
    (net (code "347") (name "unconnected-(U11C-2Q-Pad5)") (class "Default")
      (node (ref "U11C") (pin "5") (pinfunction "2Q_5") (pintype "unspecified+no_connect"))
    )
    (net (code "348") (name "unconnected-(U14F-1Y2-Pad6)") (class "Default")
      (node (ref "U14F") (pin "6") (pinfunction "1Y2_6") (pintype "unspecified+no_connect"))
    )
    (net (code "349") (name "unconnected-(U14F-1Y3-Pad7)") (class "Default")
      (node (ref "U14F") (pin "7") (pinfunction "1Y3_7") (pintype "unspecified+no_connect"))
    )
    (net (code "350") (name "unconnected-(U15B-C1-Pad3)") (class "Default")
      (node (ref "U15B") (pin "3") (pinfunction "C1_3") (pintype "unspecified+no_connect"))
    )
    (net (code "351") (name "unconnected-(U15B-C2-Pad11)") (class "Default")
      (node (ref "U15B") (pin "11") (pinfunction "C2_11") (pintype "unspecified+no_connect"))
    )
    (net (code "352") (name "unconnected-(U15B-D1-Pad1)") (class "Default")
      (node (ref "U15B") (pin "1") (pinfunction "D1_1") (pintype "unspecified+no_connect"))
    )
    (net (code "353") (name "unconnected-(U15B-D2-Pad13)") (class "Default")
      (node (ref "U15B") (pin "13") (pinfunction "D2_13") (pintype "unspecified+no_connect"))
    )
    (net (code "354") (name "{slash}BERR") (class "Default")
      (node (ref "U13A") (pin "22") (pinfunction "BERR_22") (pintype "unspecified"))
      (node (ref "U3B") (pin "9") (pinfunction "/2Q_9") (pintype "unspecified"))
    )
    (net (code "355") (name "{slash}BG") (class "Default")
      (node (ref "CN1") (pin "26") (pinfunction "/BG_26") (pintype "unspecified"))
      (node (ref "U13A") (pin "11") (pinfunction "BG_11") (pintype "unspecified"))
    )
    (net (code "356") (name "{slash}BR") (class "Default")
      (node (ref "CN1") (pin "25") (pinfunction "/BR_25") (pintype "unspecified"))
      (node (ref "RP2") (pin "12") (pinfunction "+5V_12") (pintype "unspecified"))
      (node (ref "U13A") (pin "13") (pinfunction "BR_13") (pintype "unspecified"))
    )
    (net (code "357") (name "{slash}BUST") (class "Default")
      (node (ref "U15B") (pin "9") (pinfunction "Q2_9") (pintype "unspecified"))
      (node (ref "U3B") (pin "11") (pinfunction "2PR_11") (pintype "unspecified"))
      (node (ref "U5C") (pin "14") (pinfunction "4R_14") (pintype "unspecified"))
    )
    (net (code "358") (name "{slash}CAS") (class "Default")
      (node (ref "CN1") (pin "108") (pinfunction "/CAS_108") (pintype "unspecified"))
      (node (ref "U3C") (pin "10") (pinfunction "2Q_10") (pintype "unspecified"))
    )
    (net (code "359") (name "{slash}CDACK") (class "Default")
      (node (ref "U13A") (pin "10") (pinfunction "DTACK_10") (pintype "unspecified"))
      (node (ref "U6A") (pin "10") (pinfunction "3Y_10") (pintype "unspecified"))
    )
    (net (code "360") (name "{slash}CMUX") (class "Default")
      (node (ref "U15F") (pin "1") (pinfunction "1A_1") (pintype "unspecified"))
      (node (ref "U4B") (pin "9") (pinfunction "/2Q_9") (pintype "unspecified"))
      (node (ref "U5F") (pin "14") (pinfunction "A_14") (pintype "unspecified"))
      (node (ref "U6E") (pin "14") (pinfunction "A_14") (pintype "unspecified"))
      (node (ref "U7E") (pin "14") (pinfunction "A_14") (pintype "unspecified"))
      (node (ref "U8E") (pin "14") (pinfunction "A_14") (pintype "unspecified"))
    )
    (net (code "361") (name "{slash}CSYNC") (class "Default")
      (node (ref "CN1") (pin "67") (pinfunction "/CSYNC_67") (pintype "unspecified"))
      (node (ref "U6B") (pin "12") (pinfunction "5Q_12") (pintype "unspecified"))
      (node (ref "U9E") (pin "13") (pinfunction "2A2_13") (pintype "unspecified"))
    )
    (net (code "362") (name "{slash}DBON") (class "Default")
      (node (ref "U14E") (pin "19") (pinfunction "G_19") (pintype "unspecified"))
      (node (ref "U15E") (pin "19") (pinfunction "G_19") (pintype "unspecified"))
      (node (ref "U15F") (pin "6") (pinfunction "/2Y_6") (pintype "unspecified"))
    )
    (net (code "363") (name "{slash}HDER") (class "Default")
      (node (ref "CN1") (pin "112") (pinfunction "/HDER_112") (pintype "unspecified"))
      (node (ref "R7") (pin "1") (pinfunction "1_1") (pintype "unspecified"))
      (node (ref "U7A") (pin "11") (pinfunction "4Y_11") (pintype "unspecified"))
    )
    (net (code "364") (name "{slash}HDMSK") (class "Default")
      (node (ref "C43") (pin "2") (pinfunction "2_2") (pintype "unspecified"))
      (node (ref "U4E") (pin "12") (pinfunction "Q7_12") (pintype "unspecified"))
      (node (ref "U5C") (pin "11") (pinfunction "3S1_11") (pintype "unspecified"))
      (node (ref "U5C") (pin "12") (pinfunction "3S2_12") (pintype "unspecified"))
    )
    (net (code "365") (name "{slash}HPIR") (class "Default")
      (node (ref "U10C") (pin "12") (pinfunction "1Y_12") (pintype "unspecified"))
      (node (ref "U12F") (pin "4") (pinfunction "7_4") (pintype "unspecified"))
    )
    (net (code "366") (name "{slash}HSYNC") (class "Default")
      (node (ref "CN1") (pin "111") (pinfunction "/HSYNC_111") (pintype "unspecified"))
      (node (ref "U6B") (pin "16") (pinfunction "7Q_16") (pintype "unspecified"))
    )
    (net (code "367") (name "{slash}IAK0") (class "Default")
      (node (ref "CN1") (pin "8") (pinfunction "/IAK0_8") (pintype "unspecified"))
      (node (ref "U4F") (pin "6") (pinfunction "1Y1_6") (pintype "unspecified"))
    )
    (net (code "368") (name "{slash}IAK1") (class "Default")
      (node (ref "CN1") (pin "10") (pinfunction "/IAK1_10") (pintype "unspecified"))
      (node (ref "U4F") (pin "7") (pinfunction "1Y0_7") (pintype "unspecified"))
    )
    (net (code "369") (name "{slash}IAK2") (class "Default")
      (node (ref "CN1") (pin "12") (pinfunction "/IAK2_12") (pintype "unspecified"))
      (node (ref "U4F") (pin "12") (pinfunction "2Y3_12") (pintype "unspecified"))
    )
    (net (code "370") (name "{slash}INITIO") (class "Default")
      (node (ref "CN1") (pin "68") (pinfunction "/INITIO_68") (pintype "unspecified"))
      (node (ref "U13F") (pin "9") (pinfunction "Y6_9") (pintype "unspecified"))
    )
    (net (code "371") (name "{slash}INT0") (class "Default")
      (node (ref "CN1") (pin "7") (pinfunction "/INT0_7") (pintype "unspecified"))
      (node (ref "RP2") (pin "7") (pinfunction "+5V_7") (pintype "unspecified"))
      (node (ref "U12F") (pin "2") (pinfunction "5_2") (pintype "unspecified"))
    )
    (net (code "372") (name "{slash}INT1") (class "Default")
      (node (ref "CN1") (pin "9") (pinfunction "/INT1_9") (pintype "unspecified"))
      (node (ref "RP2") (pin "8") (pinfunction "+5V_8") (pintype "unspecified"))
      (node (ref "U12F") (pin "1") (pinfunction "4_1") (pintype "unspecified"))
    )
    (net (code "373") (name "{slash}INT2") (class "Default")
      (node (ref "CN1") (pin "11") (pinfunction "/INT2_11") (pintype "unspecified"))
      (node (ref "RP2") (pin "9") (pinfunction "+5V_9") (pintype "unspecified"))
      (node (ref "U12F") (pin "13") (pinfunction "3_13") (pintype "unspecified"))
    )
    (net (code "374") (name "{slash}IO") (class "Default")
      (node (ref "RP1") (pin "1") (pinfunction "+5V_1") (pintype "unspecified"))
      (node (ref "U10A") (pin "12") (pinfunction "VO3_12") (pintype "unspecified"))
      (node (ref "U10B") (pin "14") (pinfunction "A3_14") (pintype "unspecified"))
      (node (ref "U11A") (pin "4") (pinfunction "A3_4") (pintype "unspecified"))
      (node (ref "U3D") (pin "2") (pinfunction "1B_2") (pintype "unspecified"))
    )
    (net (code "375") (name "{slash}IOCY") (class "Default")
      (node (ref "U4B") (pin "7") (pinfunction "/1Q_7") (pintype "unspecified"))
      (node (ref "U5A") (pin "10") (pinfunction "3B_10") (pintype "unspecified"))
    )
    (net (code "376") (name "{slash}IOIR") (class "Default")
      (node (ref "CN1") (pin "15") (pinfunction "/IOIR_15") (pintype "unspecified"))
      (node (ref "RP2") (pin "10") (pinfunction "+5V_10") (pintype "unspecified"))
      (node (ref "U12F") (pin "10") (pinfunction "0_10") (pintype "unspecified"))
      (node (ref "U12F") (pin "11") (pinfunction "1_11") (pintype "unspecified"))
      (node (ref "U2E") (pin "10") (pinfunction "5Y_10") (pintype "unspecified"))
    )
    (net (code "377") (name "{slash}KBIR") (class "Default")
      (node (ref "CN1") (pin "14") (pinfunction "/KBIR_14") (pintype "unspecified"))
      (node (ref "RP2") (pin "14") (pinfunction "+5V_14") (pintype "unspecified"))
      (node (ref "U12F") (pin "12") (pinfunction "2_12") (pintype "unspecified"))
    )
    (net (code "378") (name "{slash}LDMA") (class "Default")
      (node (ref "CN1") (pin "23") (pinfunction "/LDMA_23") (pintype "unspecified"))
      (node (ref "R11") (pin "2") (pinfunction "2_2") (pintype "unspecified"))
      (node (ref "U7D") (pin "11") (pinfunction "G_11") (pintype "unspecified"))
    )
    (net (code "379") (name "{slash}MALE") (class "Default")
      (node (ref "U11D") (pin "11") (pinfunction "G_11") (pintype "unspecified"))
      (node (ref "U2B") (pin "10") (pinfunction "2Q_10") (pintype "unspecified"))
      (node (ref "U6D") (pin "9") (pinfunction "3A_9") (pintype "unspecified"))
    )
    (net (code "380") (name "{slash}MDEN") (class "Default")
      (node (ref "U11F") (pin "19") (pinfunction "G_19") (pintype "unspecified"))
      (node (ref "U5A") (pin "8") (pinfunction "3Y_8") (pintype "unspecified"))
      (node (ref "U9F") (pin "19") (pinfunction "G_19") (pintype "unspecified"))
    )
    (net (code "381") (name "{slash}MEM") (class "Default")
      (node (ref "RP1") (pin "15") (pinfunction "+5V_15") (pintype "unspecified"))
      (node (ref "U10A") (pin "11") (pinfunction "VO4_11") (pintype "unspecified"))
      (node (ref "U10B") (pin "12") (pinfunction "A4_12") (pintype "unspecified"))
      (node (ref "U11A") (pin "5") (pinfunction "A4_5") (pintype "unspecified"))
      (node (ref "U5B") (pin "2") (pinfunction "1A_2") (pintype "unspecified"))
    )
    (net (code "382") (name "{slash}RAS") (class "Default")
      (node (ref "CN1") (pin "109") (pinfunction "/RAS_109") (pintype "unspecified"))
      (node (ref "U3C") (pin "6") (pinfunction "1Q_6") (pintype "unspecified"))
    )
    (net (code "383") (name "{slash}RBES") (class "Default")
      (node (ref "U14F") (pin "9") (pinfunction "2Y3_9") (pintype "unspecified"))
      (node (ref "U9E") (pin "1") (pinfunction "1G_1") (pintype "unspecified"))
      (node (ref "U9E") (pin "19") (pinfunction "2G_19") (pintype "unspecified"))
    )
    (net (code "384") (name "{slash}RESET") (class "Default")
      (node (ref "CN1") (pin "21") (pinfunction "/RESET_21") (pintype "unspecified"))
      (node (ref "R12") (pin "1") (pinfunction "1_1") (pintype "unspecified"))
      (node (ref "U2E") (pin "4") (pinfunction "2Y_4") (pintype "unspecified"))
    )
    (net (code "385") (name "{slash}RMEA") (class "Default")
      (node (ref "U11E") (pin "1") (pinfunction "/OE_1") (pintype "unspecified"))
      (node (ref "U13E") (pin "1") (pinfunction "/OE_1") (pintype "unspecified"))
      (node (ref "U14F") (pin "10") (pinfunction "2Y2_10") (pintype "unspecified"))
      (node (ref "U5C") (pin "15") (pinfunction "4S_15") (pintype "unspecified"))
    )
    (net (code "386") (name "{slash}RO") (class "Default")
      (node (ref "RP1") (pin "14") (pinfunction "+5V_14") (pintype "unspecified"))
      (node (ref "U10A") (pin "13") (pinfunction "VO2_13") (pintype "unspecified"))
      (node (ref "U10B") (pin "3") (pinfunction "A2_3") (pintype "unspecified"))
      (node (ref "U11A") (pin "3") (pinfunction "A2_3") (pintype "unspecified"))
      (node (ref "U1B") (pin "11") (pinfunction "5A_11") (pintype "unspecified"))
      (node (ref "U2D") (pin "2") (pinfunction "B1_2") (pintype "unspecified"))
    )
    (net (code "387") (name "{slash}ROM") (class "Default")
      (node (ref "U13D") (pin "22") (pinfunction "OE_22") (pintype "unspecified"))
      (node (ref "U14D") (pin "22") (pinfunction "OE_22") (pintype "unspecified"))
      (node (ref "U14F") (pin "4") (pinfunction "1Y0_4") (pintype "unspecified"))
    )
    (net (code "388") (name "{slash}RSIR") (class "Default")
      (node (ref "CN1") (pin "13") (pinfunction "/RSIR_13") (pintype "unspecified"))
      (node (ref "RP2") (pin "13") (pinfunction "+5V_13") (pintype "unspecified"))
      (node (ref "U12F") (pin "3") (pinfunction "6_3") (pintype "unspecified"))
    )
    (net (code "389") (name "{slash}RSTSW") (class "Default")
      (node (ref "C8") (pin "1") (pinfunction "1_1") (pintype "unspecified"))
      (node (ref "CN1") (pin "101") (pinfunction "/RSTSW_101") (pintype "unspecified"))
      (node (ref "CR1") (pin "1") (pinfunction "1_1") (pintype "unspecified"))
      (node (ref "R2") (pin "1") (pinfunction "1_1") (pintype "unspecified"))
      (node (ref "U15B") (pin "2") (pinfunction "TH1_2") (pintype "unspecified"))
      (node (ref "U15B") (pin "6") (pinfunction "TR1_6") (pintype "unspecified"))
    )
    (net (code "390") (name "{slash}SFER") (class "Default")
      (node (ref "CN1") (pin "114") (pinfunction "/SFER_114") (pintype "unspecified"))
      (node (ref "R4") (pin "1") (pinfunction "1_1") (pintype "unspecified"))
      (node (ref "U7A") (pin "8") (pinfunction "3Y_8") (pintype "unspecified"))
    )
    (net (code "391") (name "{slash}SFMSK") (class "Default")
      (node (ref "U4E") (pin "10") (pinfunction "Q5_10") (pintype "unspecified"))
      (node (ref "U5C") (pin "2") (pinfunction "1S1_2") (pintype "unspecified"))
      (node (ref "U5C") (pin "3") (pinfunction "1S2_3") (pintype "unspecified"))
    )
    (net (code "392") (name "{slash}SH0") (class "Default")
      (node (ref "CN1") (pin "2") (pinfunction "/SL0_2") (pintype "unspecified"))
      (node (ref "U13F") (pin "14") (pinfunction "Y1_14") (pintype "unspecified"))
    )
    (net (code "393") (name "{slash}SH1") (class "Default")
      (node (ref "CN1") (pin "4") (pinfunction "/SH1_4") (pintype "unspecified"))
      (node (ref "U13F") (pin "12") (pinfunction "Y3_12") (pintype "unspecified"))
    )
    (net (code "394") (name "{slash}SH2") (class "Default")
      (node (ref "CN1") (pin "6") (pinfunction "/SH2_6") (pintype "unspecified"))
      (node (ref "U13F") (pin "10") (pinfunction "Y5_10") (pintype "unspecified"))
    )
    (net (code "395") (name "{slash}SL0") (class "Default")
      (node (ref "CN1") (pin "1") (pinfunction "/SH0_1") (pintype "unspecified"))
      (node (ref "U13F") (pin "15") (pinfunction "Y0_15") (pintype "unspecified"))
    )
    (net (code "396") (name "{slash}SL1") (class "Default")
      (node (ref "CN1") (pin "3") (pinfunction "/SL1_3") (pintype "unspecified"))
      (node (ref "U13F") (pin "13") (pinfunction "Y2_13") (pintype "unspecified"))
    )
    (net (code "397") (name "{slash}SL2") (class "Default")
      (node (ref "CN1") (pin "5") (pinfunction "/SL2_5") (pintype "unspecified"))
      (node (ref "U13F") (pin "11") (pinfunction "Y4_11") (pintype "unspecified"))
    )
    (net (code "398") (name "{slash}START") (class "Default")
      (node (ref "U1A") (pin "5") (pinfunction "B2_5") (pintype "unspecified"))
      (node (ref "U4E") (pin "9") (pinfunction "Q4_9") (pintype "unspecified"))
    )
    (net (code "399") (name "{slash}STK") (class "Default")
      (node (ref "RP1") (pin "9") (pinfunction "+5V_9") (pintype "unspecified"))
      (node (ref "U10A") (pin "14") (pinfunction "VO1_14") (pintype "unspecified"))
      (node (ref "U10B") (pin "5") (pinfunction "A1_5") (pintype "unspecified"))
      (node (ref "U11A") (pin "2") (pinfunction "A1_2") (pintype "unspecified"))
      (node (ref "U4D") (pin "2") (pinfunction "1B_2") (pintype "unspecified"))
      (node (ref "U5B") (pin "9") (pinfunction "3B_9") (pintype "unspecified"))
    )
    (net (code "400") (name "{slash}T0") (class "Default")
      (node (ref "U1D") (pin "15") (pinfunction "Y0_15") (pintype "unspecified"))
      (node (ref "U3C") (pin "3") (pinfunction "1K_3") (pintype "unspecified"))
    )
    (net (code "401") (name "{slash}T1") (class "Default")
      (node (ref "U1D") (pin "14") (pinfunction "Y1_14") (pintype "unspecified"))
    )
    (net (code "402") (name "{slash}T2") (class "Default")
      (node (ref "U1D") (pin "13") (pinfunction "Y2_13") (pintype "unspecified"))
      (node (ref "U3C") (pin "13") (pinfunction "2K_13") (pintype "unspecified"))
      (node (ref "U3D") (pin "10") (pinfunction "2D_10") (pintype "unspecified"))
      (node (ref "U3D") (pin "12") (pinfunction "1D_12") (pintype "unspecified"))
    )
    (net (code "403") (name "{slash}T3") (class "Default")
      (node (ref "U1D") (pin "12") (pinfunction "Y3_12") (pintype "unspecified"))
      (node (ref "U2C") (pin "12") (pinfunction "1D_12") (pintype "unspecified"))
    )
    (net (code "404") (name "{slash}T4") (class "Default")
      (node (ref "U1D") (pin "11") (pinfunction "Y4_11") (pintype "unspecified"))
      (node (ref "U2D") (pin "4") (pinfunction "A2_4") (pintype "unspecified"))
      (node (ref "U5D") (pin "3") (pinfunction "1K_3") (pintype "unspecified"))
    )
    (net (code "405") (name "{slash}T7") (class "Default")
      (node (ref "U1D") (pin "7") (pinfunction "Y7_7") (pintype "unspecified"))
    )
    (net (code "406") (name "{slash}VAL") (class "Default")
      (node (ref "U14F") (pin "11") (pinfunction "2Y1_11") (pintype "unspecified"))
      (node (ref "U15F") (pin "12") (pinfunction "4A_12") (pintype "unspecified"))
      (node (ref "U15F") (pin "13") (pinfunction "4B_13") (pintype "unspecified"))
    )
    (net (code "407") (name "{slash}VMA") (class "Default")
      (node (ref "CN1") (pin "59") (pinfunction "/VMA_59") (pintype "unspecified"))
      (node (ref "U8C") (pin "12") (pinfunction "1Y4_12") (pintype "unspecified"))
    )
    (net (code "408") (name "{slash}VPA") (class "Default")
      (node (ref "CN1") (pin "60") (pinfunction "/VPA_60") (pintype "unspecified"))
      (node (ref "RP1") (pin "13") (pinfunction "+5V_13") (pintype "unspecified"))
      (node (ref "U13A") (pin "21") (pinfunction "VPA_21") (pintype "unspecified"))
      (node (ref "U4F") (pin "10") (pinfunction "2Y1_10") (pintype "unspecified"))
      (node (ref "U4F") (pin "11") (pinfunction "2Y2_11") (pintype "unspecified"))
      (node (ref "U4F") (pin "4") (pinfunction "1Y3_4") (pintype "unspecified"))
      (node (ref "U4F") (pin "5") (pinfunction "1Y2_5") (pintype "unspecified"))
      (node (ref "U4F") (pin "9") (pinfunction "2Y0_9") (pintype "unspecified"))
    )
    (net (code "409") (name "{slash}VSIR") (class "Default")
      (node (ref "U5C") (pin "5") (pinfunction "2R_5") (pintype "unspecified"))
      (node (ref "U6D") (pin "3") (pinfunction "/1Y_3") (pintype "unspecified"))
    )
    (net (code "410") (name "{slash}VSYNC") (class "Default")
      (node (ref "CN1") (pin "113") (pinfunction "/VSYNC_113") (pintype "unspecified"))
      (node (ref "U6B") (pin "5") (pinfunction "2Q_5") (pintype "unspecified"))
    )
    (net (code "411") (name "{slash}VTIR") (class "Default")
      (node (ref "U2E") (pin "11") (pinfunction "5A_11") (pintype "unspecified"))
      (node (ref "U5C") (pin "7") (pinfunction "2Q_7") (pintype "unspecified"))
      (node (ref "U9E") (pin "6") (pinfunction "1A3_6") (pintype "unspecified"))
    )
    (net (code "412") (name "{slash}VTMSK") (class "Default")
      (node (ref "U4E") (pin "11") (pinfunction "Q6_11") (pintype "unspecified"))
      (node (ref "U5C") (pin "6") (pinfunction "2S_6") (pintype "unspecified"))
    )
  )
)
